# ME461_F28379D.net
KiCad netlist of a schematic drawn in EAGLE
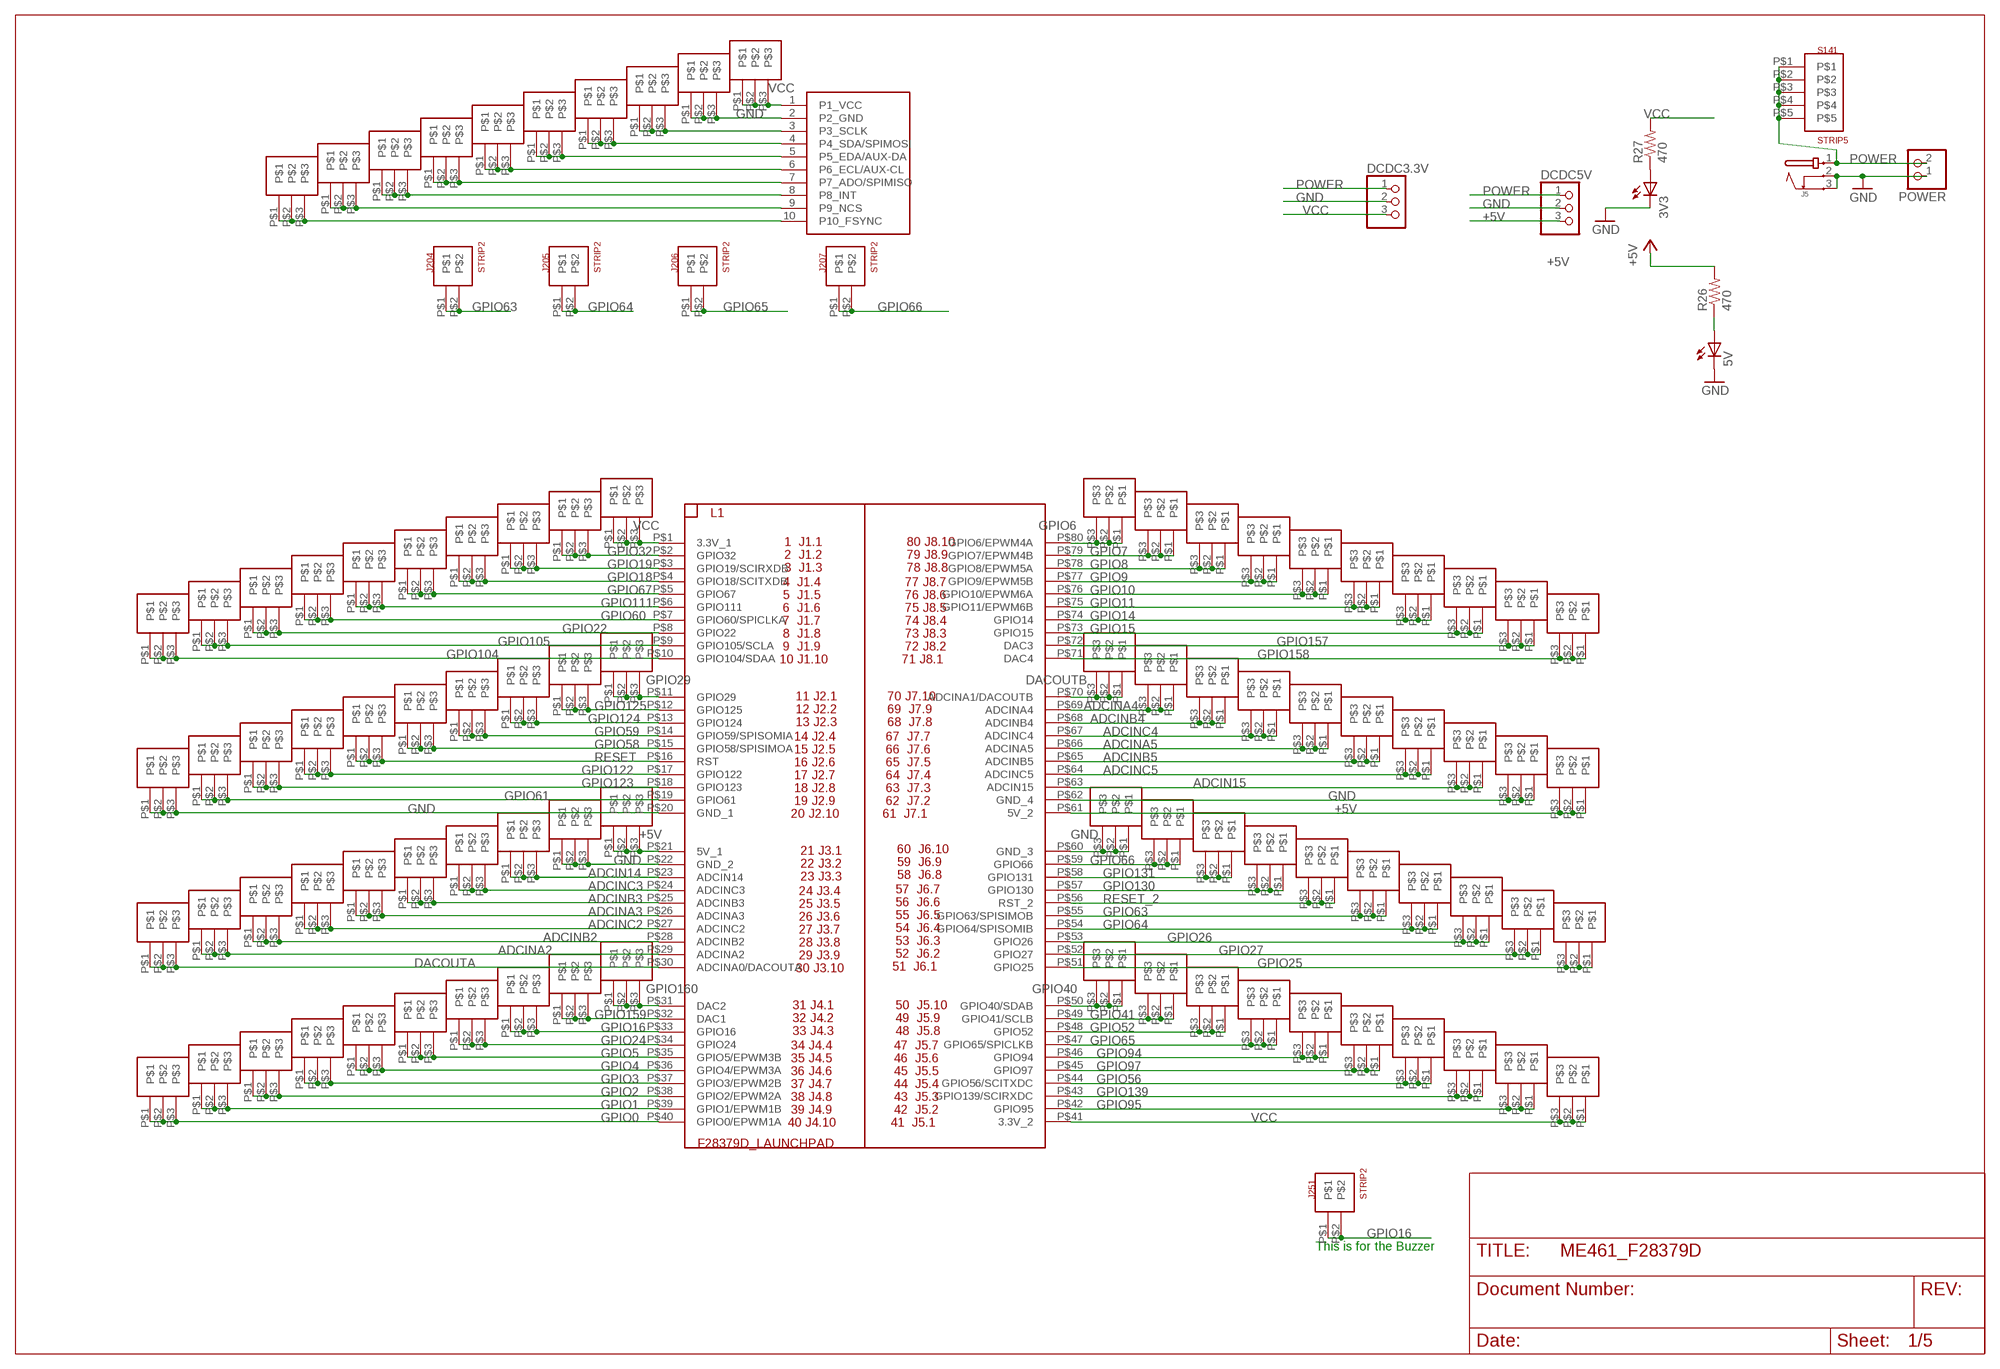
[diagram p0: schematic, sheet 1]
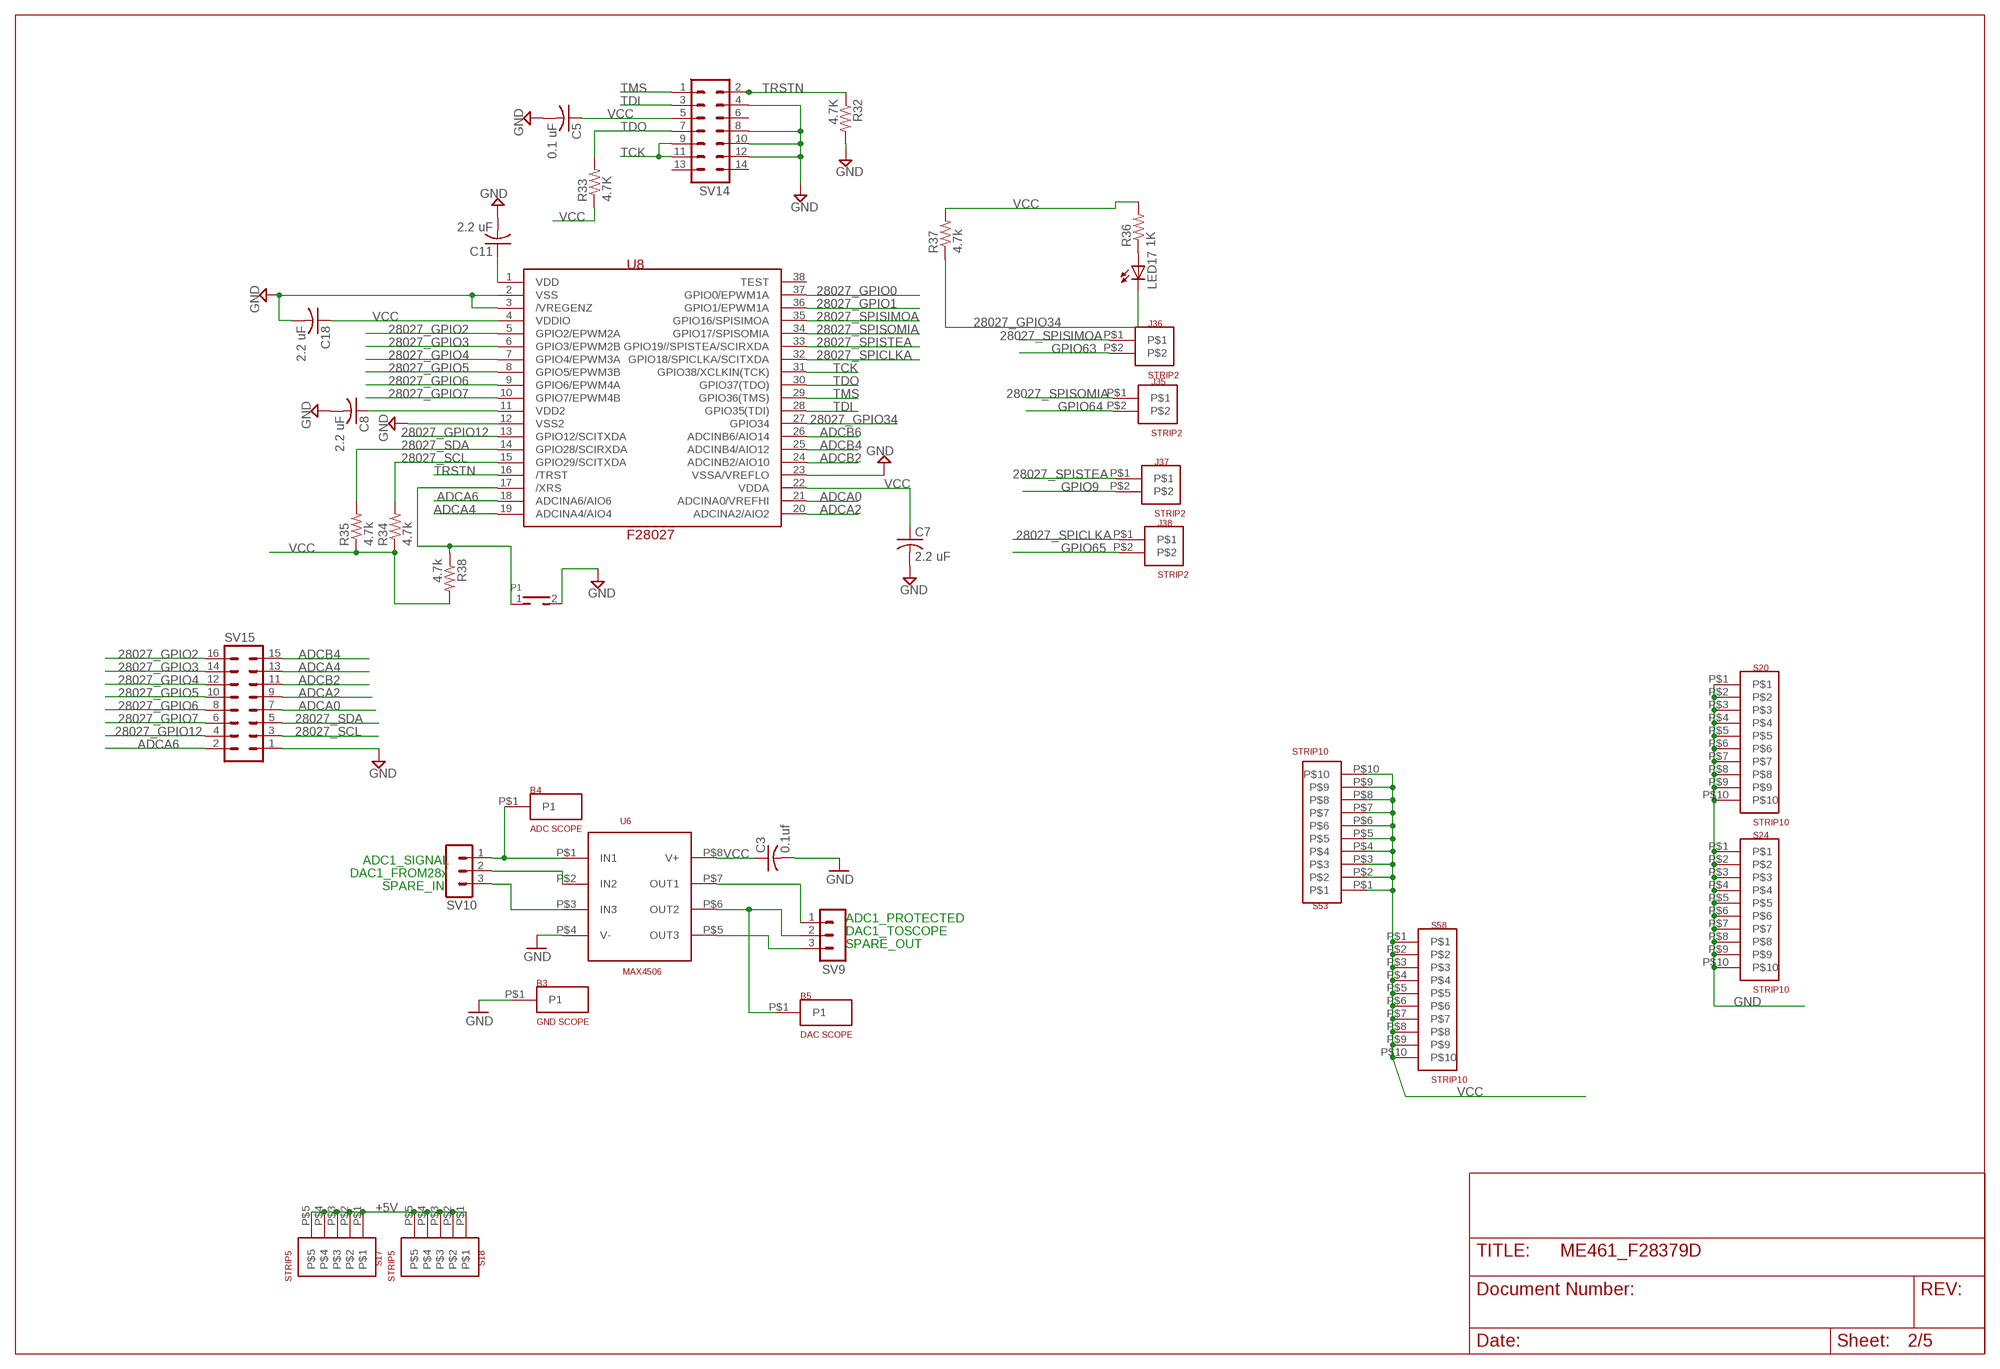
[diagram p1: schematic, sheet 2]
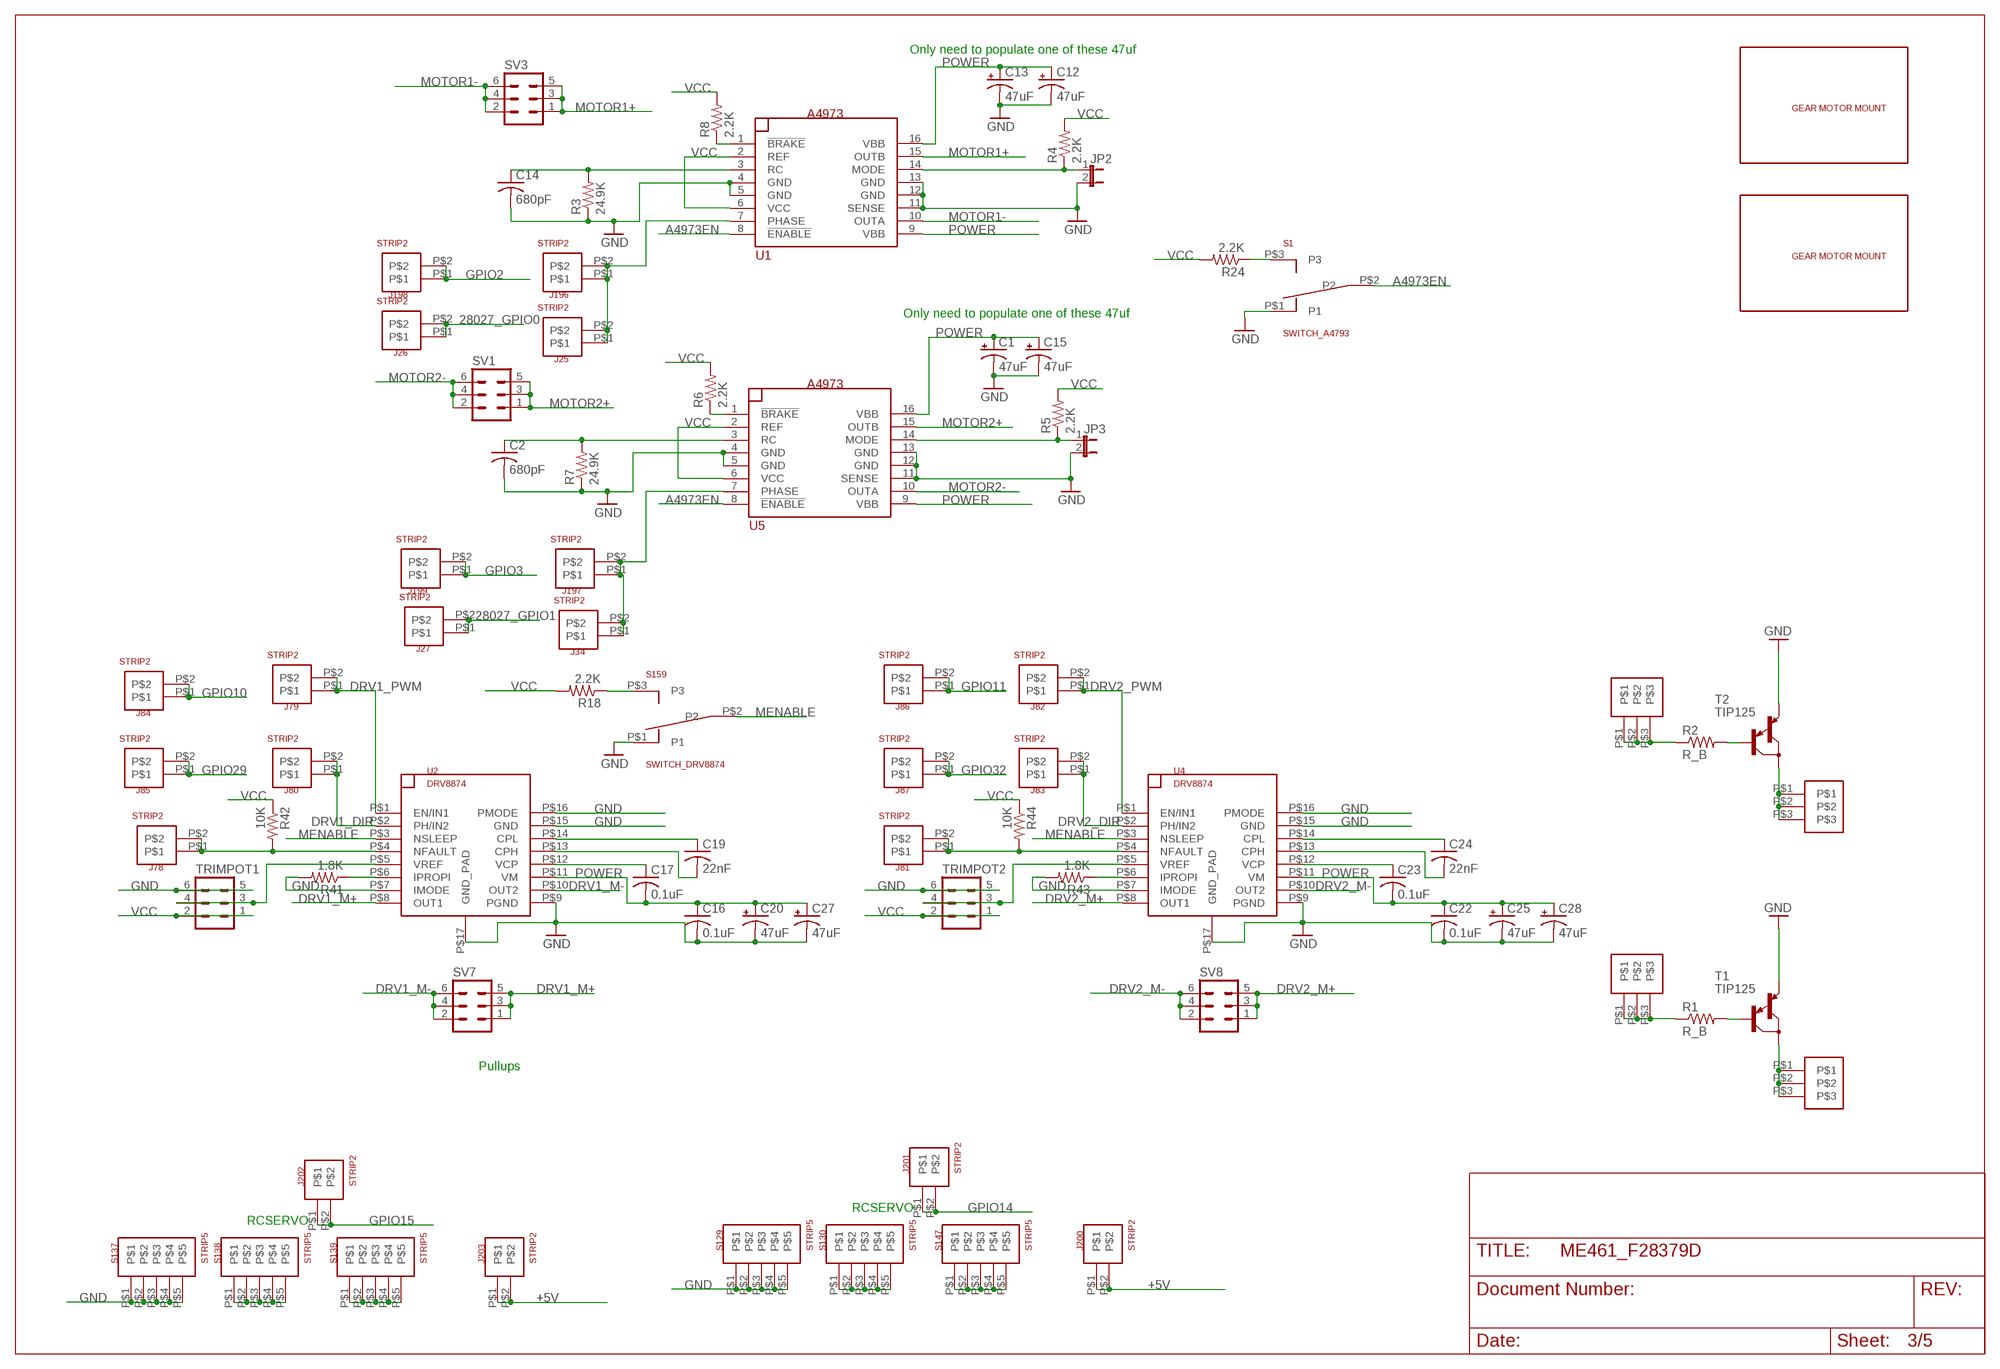
[diagram p2: schematic, sheet 3]
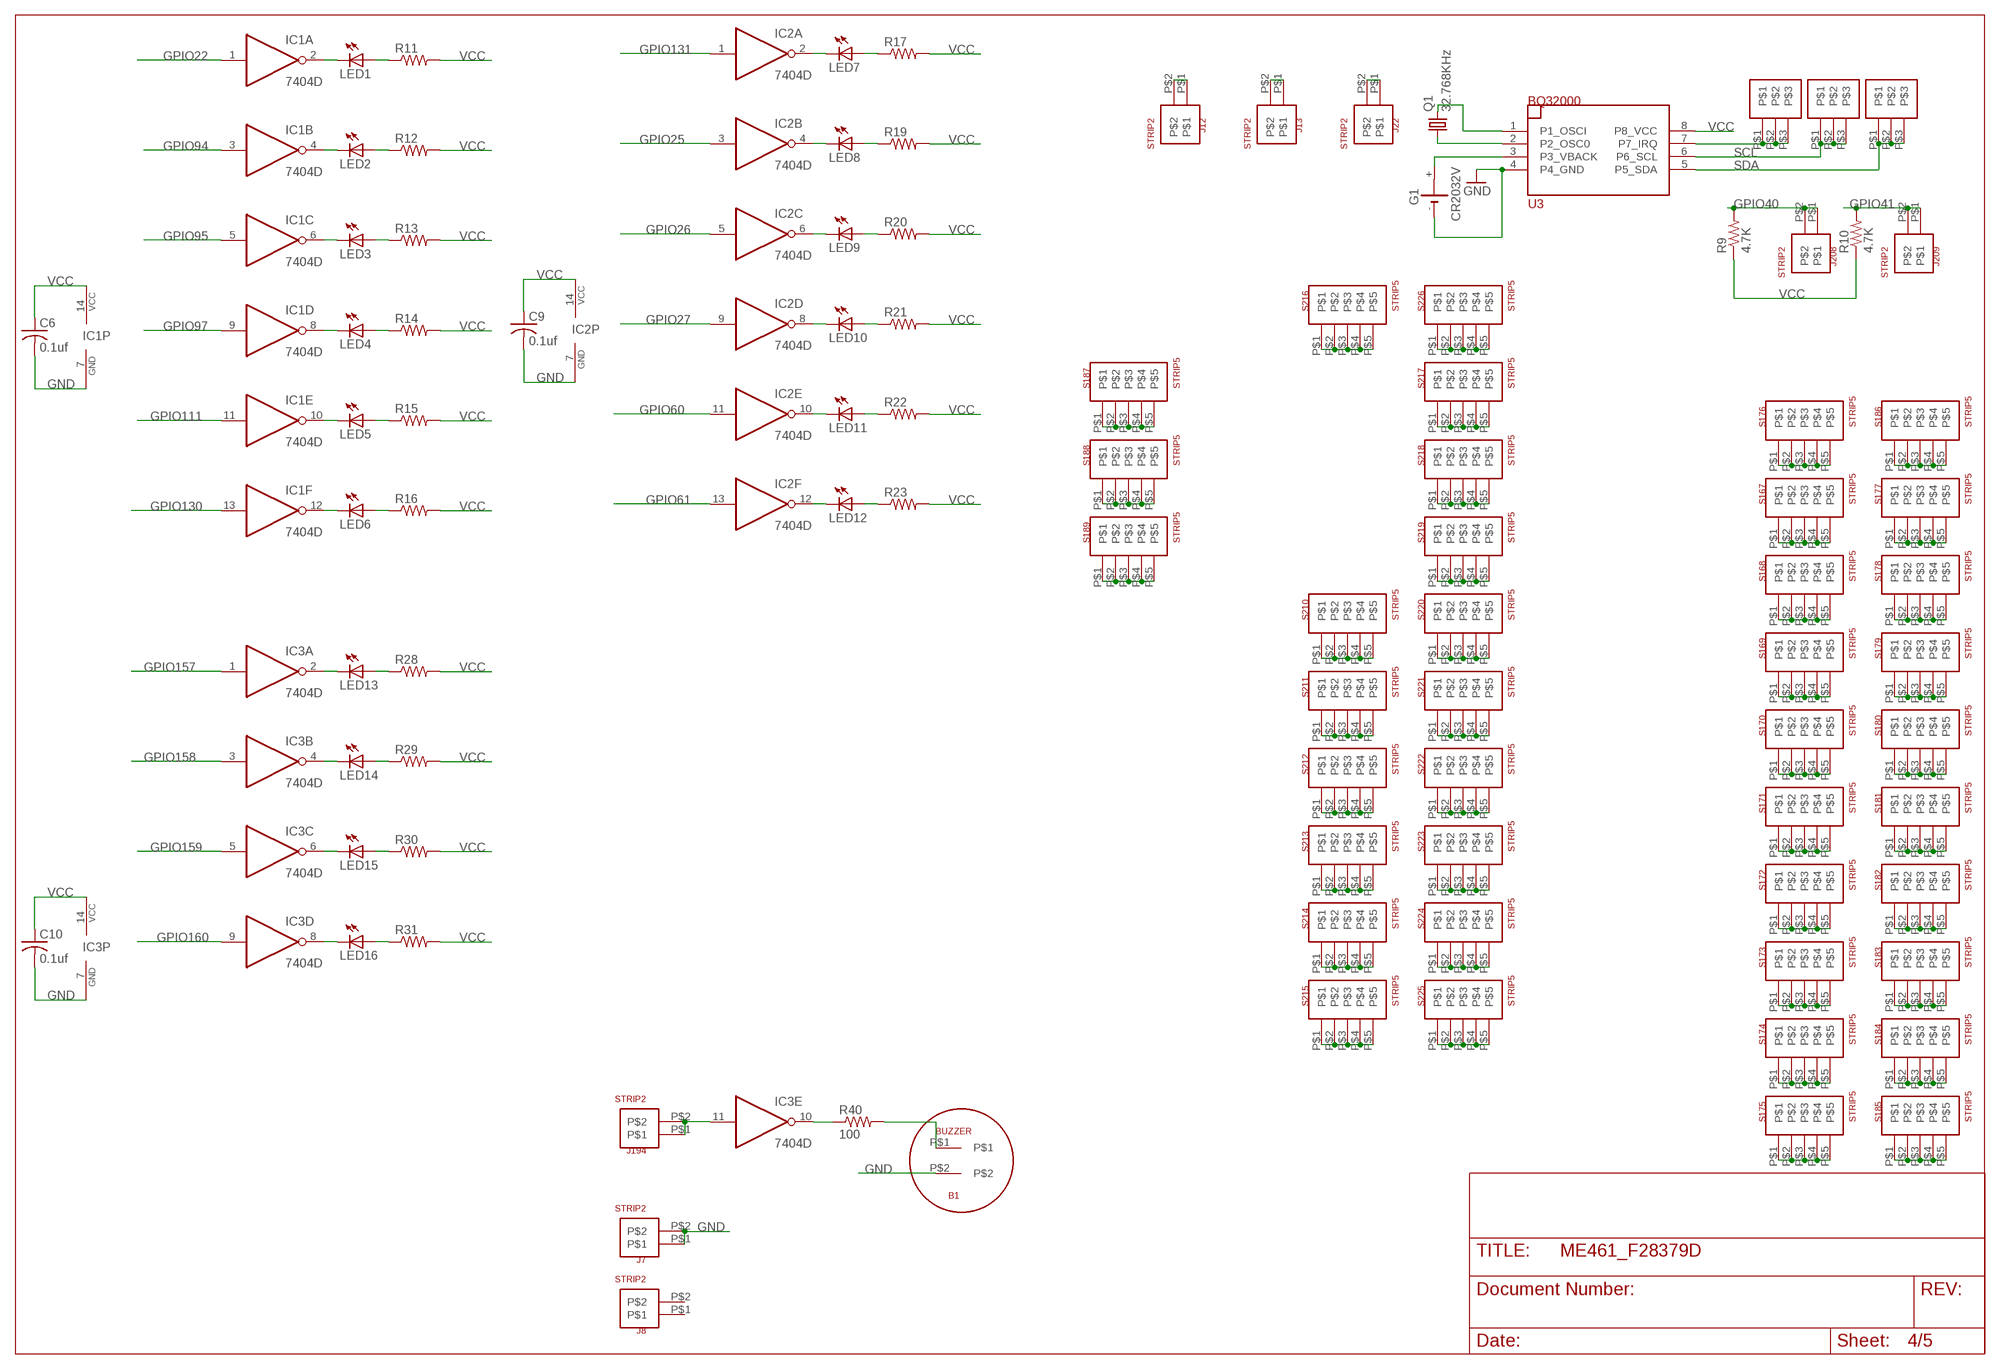
[diagram p3: schematic, sheet 4]
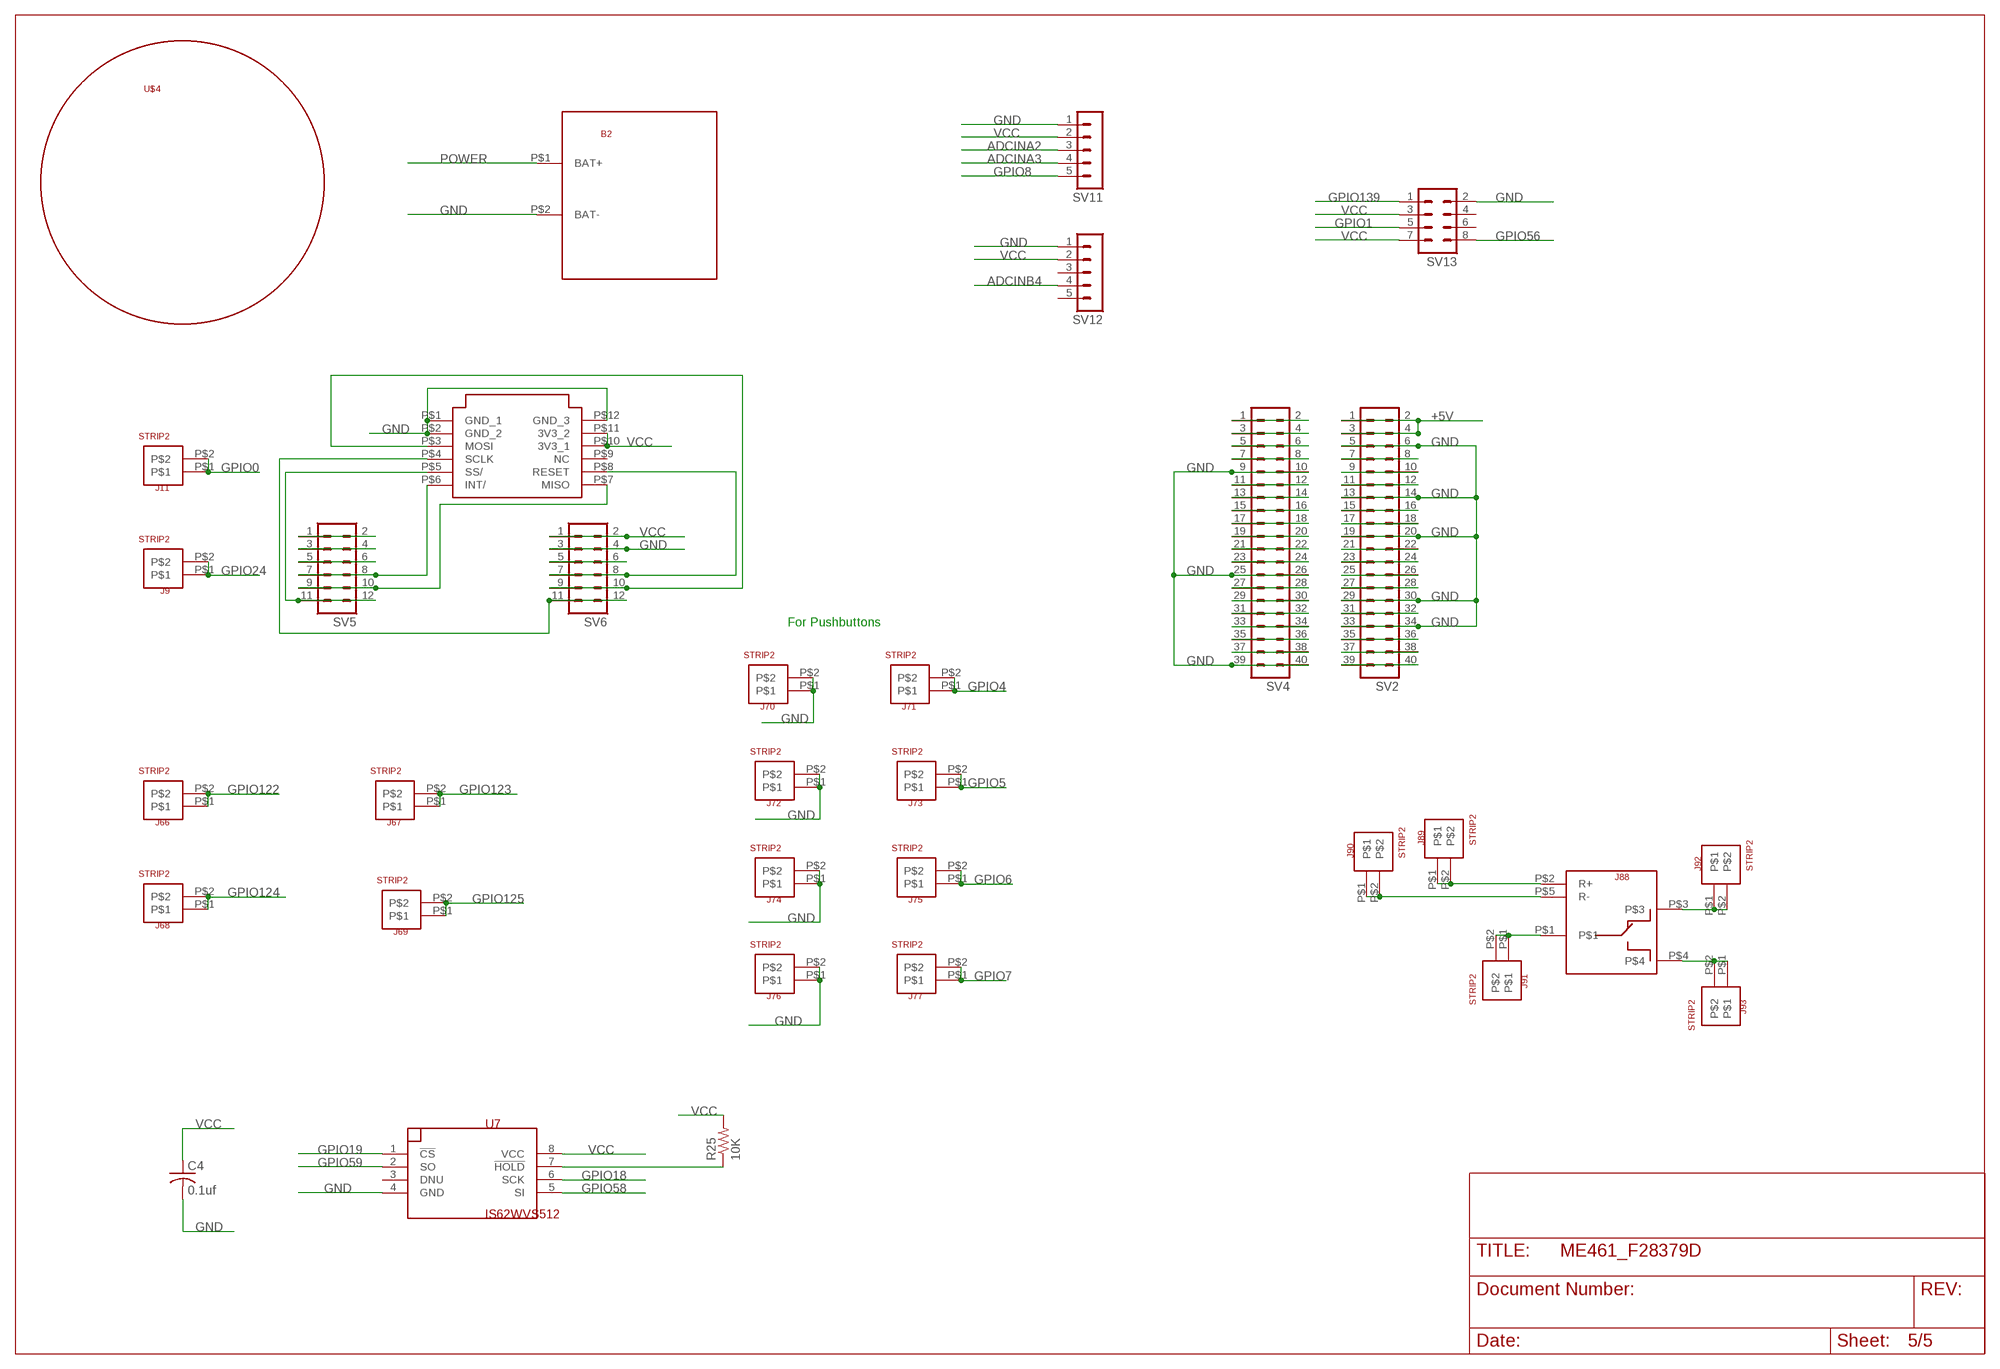
[diagram p4: schematic, sheet 5]

(export (version "E")
  (design (tool "Eeschema 10.0.6"))
  (components
    (comp (ref "B2")
      (value "BATTERY_4AA_HOLDER")
      (footprint "eagle-import:BATTERY_4AA_HOLDER")
      (libsource (lib "eagle-import") (part "BATTERY_4AA_HOLDER"))
    )
    (comp (ref "C4")
      (value "0.1uf")
      (footprint "eagle-import:C1206")
      (libsource (lib "eagle-import") (part "C-USC1206"))
    )
    (comp (ref "ETH1")
      (value "USR_ES1_W5500")
      (footprint "eagle-import:USR_ES1_W5500")
      (libsource (lib "eagle-import") (part "USR_ES1_W5500"))
    )
    (comp (ref "J9")
      (value "STRIP2")
      (footprint "eagle-import:STRIP2")
      (libsource (lib "eagle-import") (part "STRIP2"))
    )
    (comp (ref "J11")
      (value "STRIP2")
      (footprint "eagle-import:STRIP2")
      (libsource (lib "eagle-import") (part "STRIP2"))
    )
    (comp (ref "J66")
      (value "STRIP2")
      (footprint "eagle-import:STRIP2")
      (libsource (lib "eagle-import") (part "STRIP2"))
    )
    (comp (ref "J67")
      (value "STRIP2")
      (footprint "eagle-import:STRIP2")
      (libsource (lib "eagle-import") (part "STRIP2"))
    )
    (comp (ref "J68")
      (value "STRIP2")
      (footprint "eagle-import:STRIP2")
      (libsource (lib "eagle-import") (part "STRIP2"))
    )
    (comp (ref "J69")
      (value "STRIP2")
      (footprint "eagle-import:STRIP2")
      (libsource (lib "eagle-import") (part "STRIP2"))
    )
    (comp (ref "J70")
      (value "STRIP2")
      (footprint "eagle-import:STRIP2")
      (libsource (lib "eagle-import") (part "STRIP2"))
    )
    (comp (ref "J71")
      (value "STRIP2")
      (footprint "eagle-import:STRIP2")
      (libsource (lib "eagle-import") (part "STRIP2"))
    )
    (comp (ref "J72")
      (value "STRIP2")
      (footprint "eagle-import:STRIP2")
      (libsource (lib "eagle-import") (part "STRIP2"))
    )
    (comp (ref "J73")
      (value "STRIP2")
      (footprint "eagle-import:STRIP2")
      (libsource (lib "eagle-import") (part "STRIP2"))
    )
    (comp (ref "J74")
      (value "STRIP2")
      (footprint "eagle-import:STRIP2")
      (libsource (lib "eagle-import") (part "STRIP2"))
    )
    (comp (ref "J75")
      (value "STRIP2")
      (footprint "eagle-import:STRIP2")
      (libsource (lib "eagle-import") (part "STRIP2"))
    )
    (comp (ref "J76")
      (value "STRIP2")
      (footprint "eagle-import:STRIP2")
      (libsource (lib "eagle-import") (part "STRIP2"))
    )
    (comp (ref "J77")
      (value "STRIP2")
      (footprint "eagle-import:STRIP2")
      (libsource (lib "eagle-import") (part "STRIP2"))
    )
    (comp (ref "J88")
      (value "RELAY_JQC-3F_5V")
      (footprint "eagle-import:RELAY_JQC-3F_5V")
      (libsource (lib "eagle-import") (part "RELAY_JQC-3F_5V"))
    )
    (comp (ref "J89")
      (value "STRIP2")
      (footprint "eagle-import:STRIP2")
      (libsource (lib "eagle-import") (part "STRIP2"))
    )
    (comp (ref "J90")
      (value "STRIP2")
      (footprint "eagle-import:STRIP2")
      (libsource (lib "eagle-import") (part "STRIP2"))
    )
    (comp (ref "J91")
      (value "STRIP2")
      (footprint "eagle-import:STRIP2")
      (libsource (lib "eagle-import") (part "STRIP2"))
    )
    (comp (ref "J92")
      (value "STRIP2")
      (footprint "eagle-import:STRIP2")
      (libsource (lib "eagle-import") (part "STRIP2"))
    )
    (comp (ref "J93")
      (value "STRIP2")
      (footprint "eagle-import:STRIP2")
      (libsource (lib "eagle-import") (part "STRIP2"))
    )
    (comp (ref "R25")
      (value "10K")
      (footprint "eagle-import:M1206")
      (libsource (lib "eagle-import") (part "R-US_M1206"))
    )
    (comp (ref "SV2")
      (value "MA20-2")
      (footprint "eagle-import:MA20-2")
      (libsource (lib "eagle-import") (part "MA20-2"))
    )
    (comp (ref "SV4")
      (value "MA20-2")
      (footprint "eagle-import:MA20-2")
      (libsource (lib "eagle-import") (part "MA20-2"))
    )
    (comp (ref "SV5")
      (value "MA06-2")
      (footprint "eagle-import:MA06-2")
      (libsource (lib "eagle-import") (part "MA06-2"))
    )
    (comp (ref "SV6")
      (value "MA06-2")
      (footprint "eagle-import:MA06-2")
      (libsource (lib "eagle-import") (part "MA06-2"))
    )
    (comp (ref "SV11")
      (value "MA05-1")
      (footprint "eagle-import:MA05-1")
      (libsource (lib "eagle-import") (part "MA05-1"))
    )
    (comp (ref "SV12")
      (value "MA05-1")
      (footprint "eagle-import:MA05-1")
      (libsource (lib "eagle-import") (part "MA05-1"))
    )
    (comp (ref "SV13")
      (value "MA04-2")
      (footprint "eagle-import:MA04-2")
      (libsource (lib "eagle-import") (part "MA04-2"))
    )
    (comp (ref "U$4")
      (value "CASTERWHEEL")
      (footprint "eagle-import:CASTERWHEEL")
      (libsource (lib "eagle-import") (part "CASTERWHEEL"))
    )
    (comp (ref "U7")
      (value "IS62WVS512")
      (footprint "eagle-import:SO08")
      (libsource (lib "eagle-import") (part "IS62WVS512"))
    )
    (comp (ref "B1")
      (value "BUZZER")
      (footprint "eagle-import:BUZZER")
      (libsource (lib "eagle-import") (part "BUZZER"))
    )
    (comp (ref "C6")
      (value "0.1uf")
      (footprint "eagle-import:C1206")
      (libsource (lib "eagle-import") (part "C-USC1206"))
    )
    (comp (ref "C9")
      (value "0.1uf")
      (footprint "eagle-import:C1206")
      (libsource (lib "eagle-import") (part "C-USC1206"))
    )
    (comp (ref "C10")
      (value "0.1uf")
      (footprint "eagle-import:C1206")
      (libsource (lib "eagle-import") (part "C-USC1206"))
    )
    (comp (ref "G1")
      (value "CR2032V")
      (footprint "eagle-import:CR2032V")
      (libsource (lib "eagle-import") (part "CR2032V"))
    )
    (comp (ref "IC1")
      (value "7404D")
      (footprint "eagle-import:SO14")
      (libsource (lib "eagle-import") (part "7404D"))
    )
    (comp (ref "IC2")
      (value "7404D")
      (footprint "eagle-import:SO14")
      (libsource (lib "eagle-import") (part "7404D"))
    )
    (comp (ref "IC3")
      (value "7404D")
      (footprint "eagle-import:SO14")
      (libsource (lib "eagle-import") (part "7404D"))
    )
    (comp (ref "J1")
      (value "STRIP3")
      (footprint "eagle-import:STRIP3")
      (libsource (lib "eagle-import") (part "STRIP3"))
    )
    (comp (ref "J2")
      (value "STRIP3")
      (footprint "eagle-import:STRIP3")
      (libsource (lib "eagle-import") (part "STRIP3"))
    )
    (comp (ref "J3")
      (value "STRIP3")
      (footprint "eagle-import:STRIP3")
      (libsource (lib "eagle-import") (part "STRIP3"))
    )
    (comp (ref "J7")
      (value "STRIP2")
      (footprint "eagle-import:STRIP2")
      (libsource (lib "eagle-import") (part "STRIP2"))
    )
    (comp (ref "J8")
      (value "STRIP2")
      (footprint "eagle-import:STRIP2")
      (libsource (lib "eagle-import") (part "STRIP2"))
    )
    (comp (ref "J12")
      (value "STRIP2")
      (footprint "eagle-import:STRIP2")
      (libsource (lib "eagle-import") (part "STRIP2"))
    )
    (comp (ref "J13")
      (value "STRIP2")
      (footprint "eagle-import:STRIP2")
      (libsource (lib "eagle-import") (part "STRIP2"))
    )
    (comp (ref "J22")
      (value "STRIP2")
      (footprint "eagle-import:STRIP2")
      (libsource (lib "eagle-import") (part "STRIP2"))
    )
    (comp (ref "J194")
      (value "STRIP2")
      (footprint "eagle-import:STRIP2")
      (libsource (lib "eagle-import") (part "STRIP2"))
    )
    (comp (ref "J208")
      (value "STRIP2")
      (footprint "eagle-import:STRIP2")
      (libsource (lib "eagle-import") (part "STRIP2"))
    )
    (comp (ref "J209")
      (value "STRIP2")
      (footprint "eagle-import:STRIP2")
      (libsource (lib "eagle-import") (part "STRIP2"))
    )
    (comp (ref "LED1")
      (value "LEDCHIPLED_1206")
      (footprint "eagle-import:CHIPLED_1206")
      (libsource (lib "eagle-import") (part "LEDCHIPLED_1206"))
    )
    (comp (ref "LED2")
      (value "LEDCHIPLED_1206")
      (footprint "eagle-import:CHIPLED_1206")
      (libsource (lib "eagle-import") (part "LEDCHIPLED_1206"))
    )
    (comp (ref "LED3")
      (value "LEDCHIPLED_1206")
      (footprint "eagle-import:CHIPLED_1206")
      (libsource (lib "eagle-import") (part "LEDCHIPLED_1206"))
    )
    (comp (ref "LED4")
      (value "LEDCHIPLED_1206")
      (footprint "eagle-import:CHIPLED_1206")
      (libsource (lib "eagle-import") (part "LEDCHIPLED_1206"))
    )
    (comp (ref "LED5")
      (value "LEDCHIPLED_1206")
      (footprint "eagle-import:CHIPLED_1206")
      (libsource (lib "eagle-import") (part "LEDCHIPLED_1206"))
    )
    (comp (ref "LED6")
      (value "LEDCHIPLED_1206")
      (footprint "eagle-import:CHIPLED_1206")
      (libsource (lib "eagle-import") (part "LEDCHIPLED_1206"))
    )
    (comp (ref "LED7")
      (value "LEDCHIPLED_1206")
      (footprint "eagle-import:CHIPLED_1206")
      (libsource (lib "eagle-import") (part "LEDCHIPLED_1206"))
    )
    (comp (ref "LED8")
      (value "LEDCHIPLED_1206")
      (footprint "eagle-import:CHIPLED_1206")
      (libsource (lib "eagle-import") (part "LEDCHIPLED_1206"))
    )
    (comp (ref "LED9")
      (value "LEDCHIPLED_1206")
      (footprint "eagle-import:CHIPLED_1206")
      (libsource (lib "eagle-import") (part "LEDCHIPLED_1206"))
    )
    (comp (ref "LED10")
      (value "LEDCHIPLED_1206")
      (footprint "eagle-import:CHIPLED_1206")
      (libsource (lib "eagle-import") (part "LEDCHIPLED_1206"))
    )
    (comp (ref "LED11")
      (value "LEDCHIPLED_1206")
      (footprint "eagle-import:CHIPLED_1206")
      (libsource (lib "eagle-import") (part "LEDCHIPLED_1206"))
    )
    (comp (ref "LED12")
      (value "LEDCHIPLED_1206")
      (footprint "eagle-import:CHIPLED_1206")
      (libsource (lib "eagle-import") (part "LEDCHIPLED_1206"))
    )
    (comp (ref "LED13")
      (value "LEDCHIPLED_1206")
      (footprint "eagle-import:CHIPLED_1206")
      (libsource (lib "eagle-import") (part "LEDCHIPLED_1206"))
    )
    (comp (ref "LED14")
      (value "LEDCHIPLED_1206")
      (footprint "eagle-import:CHIPLED_1206")
      (libsource (lib "eagle-import") (part "LEDCHIPLED_1206"))
    )
    (comp (ref "LED15")
      (value "LEDCHIPLED_1206")
      (footprint "eagle-import:CHIPLED_1206")
      (libsource (lib "eagle-import") (part "LEDCHIPLED_1206"))
    )
    (comp (ref "LED16")
      (value "LEDCHIPLED_1206")
      (footprint "eagle-import:CHIPLED_1206")
      (libsource (lib "eagle-import") (part "LEDCHIPLED_1206"))
    )
    (comp (ref "Q1")
      (value "32.768KHz")
      (footprint "eagle-import:TC26H")
      (libsource (lib "eagle-import") (part "CRYTALTC26H"))
    )
    (comp (ref "R9")
      (value "4.7K")
      (footprint "eagle-import:R1206")
      (libsource (lib "eagle-import") (part "R-US_R1206"))
    )
    (comp (ref "R10")
      (value "4.7K")
      (footprint "eagle-import:R1206")
      (libsource (lib "eagle-import") (part "R-US_R1206"))
    )
    (comp (ref "R11")
      (value "R-US_R1206")
      (footprint "eagle-import:R1206")
      (libsource (lib "eagle-import") (part "R-US_R1206"))
    )
    (comp (ref "R12")
      (value "R-US_R1206")
      (footprint "eagle-import:R1206")
      (libsource (lib "eagle-import") (part "R-US_R1206"))
    )
    (comp (ref "R13")
      (value "R-US_R1206")
      (footprint "eagle-import:R1206")
      (libsource (lib "eagle-import") (part "R-US_R1206"))
    )
    (comp (ref "R14")
      (value "R-US_R1206")
      (footprint "eagle-import:R1206")
      (libsource (lib "eagle-import") (part "R-US_R1206"))
    )
    (comp (ref "R15")
      (value "R-US_R1206")
      (footprint "eagle-import:R1206")
      (libsource (lib "eagle-import") (part "R-US_R1206"))
    )
    (comp (ref "R16")
      (value "R-US_R1206")
      (footprint "eagle-import:R1206")
      (libsource (lib "eagle-import") (part "R-US_R1206"))
    )
    (comp (ref "R17")
      (value "R-US_R1206")
      (footprint "eagle-import:R1206")
      (libsource (lib "eagle-import") (part "R-US_R1206"))
    )
    (comp (ref "R19")
      (value "R-US_R1206")
      (footprint "eagle-import:R1206")
      (libsource (lib "eagle-import") (part "R-US_R1206"))
    )
    (comp (ref "R20")
      (value "R-US_R1206")
      (footprint "eagle-import:R1206")
      (libsource (lib "eagle-import") (part "R-US_R1206"))
    )
    (comp (ref "R21")
      (value "R-US_R1206")
      (footprint "eagle-import:R1206")
      (libsource (lib "eagle-import") (part "R-US_R1206"))
    )
    (comp (ref "R22")
      (value "R-US_R1206")
      (footprint "eagle-import:R1206")
      (libsource (lib "eagle-import") (part "R-US_R1206"))
    )
    (comp (ref "R23")
      (value "R-US_R1206")
      (footprint "eagle-import:R1206")
      (libsource (lib "eagle-import") (part "R-US_R1206"))
    )
    (comp (ref "R28")
      (value "R-US_R1206")
      (footprint "eagle-import:R1206")
      (libsource (lib "eagle-import") (part "R-US_R1206"))
    )
    (comp (ref "R29")
      (value "R-US_R1206")
      (footprint "eagle-import:R1206")
      (libsource (lib "eagle-import") (part "R-US_R1206"))
    )
    (comp (ref "R30")
      (value "R-US_R1206")
      (footprint "eagle-import:R1206")
      (libsource (lib "eagle-import") (part "R-US_R1206"))
    )
    (comp (ref "R31")
      (value "R-US_R1206")
      (footprint "eagle-import:R1206")
      (libsource (lib "eagle-import") (part "R-US_R1206"))
    )
    (comp (ref "R40")
      (value "100")
      (footprint "eagle-import:R1206")
      (libsource (lib "eagle-import") (part "R-US_R1206"))
    )
    (comp (ref "S167")
      (value "STRIP5")
      (footprint "eagle-import:STRIP5")
      (libsource (lib "eagle-import") (part "STRIP5"))
    )
    (comp (ref "S168")
      (value "STRIP5")
      (footprint "eagle-import:STRIP5")
      (libsource (lib "eagle-import") (part "STRIP5"))
    )
    (comp (ref "S169")
      (value "STRIP5")
      (footprint "eagle-import:STRIP5")
      (libsource (lib "eagle-import") (part "STRIP5"))
    )
    (comp (ref "S170")
      (value "STRIP5")
      (footprint "eagle-import:STRIP5")
      (libsource (lib "eagle-import") (part "STRIP5"))
    )
    (comp (ref "S171")
      (value "STRIP5")
      (footprint "eagle-import:STRIP5")
      (libsource (lib "eagle-import") (part "STRIP5"))
    )
    (comp (ref "S172")
      (value "STRIP5")
      (footprint "eagle-import:STRIP5")
      (libsource (lib "eagle-import") (part "STRIP5"))
    )
    (comp (ref "S173")
      (value "STRIP5")
      (footprint "eagle-import:STRIP5")
      (libsource (lib "eagle-import") (part "STRIP5"))
    )
    (comp (ref "S174")
      (value "STRIP5")
      (footprint "eagle-import:STRIP5")
      (libsource (lib "eagle-import") (part "STRIP5"))
    )
    (comp (ref "S175")
      (value "STRIP5")
      (footprint "eagle-import:STRIP5")
      (libsource (lib "eagle-import") (part "STRIP5"))
    )
    (comp (ref "S176")
      (value "STRIP5")
      (footprint "eagle-import:STRIP5")
      (libsource (lib "eagle-import") (part "STRIP5"))
    )
    (comp (ref "S177")
      (value "STRIP5")
      (footprint "eagle-import:STRIP5")
      (libsource (lib "eagle-import") (part "STRIP5"))
    )
    (comp (ref "S178")
      (value "STRIP5")
      (footprint "eagle-import:STRIP5")
      (libsource (lib "eagle-import") (part "STRIP5"))
    )
    (comp (ref "S179")
      (value "STRIP5")
      (footprint "eagle-import:STRIP5")
      (libsource (lib "eagle-import") (part "STRIP5"))
    )
    (comp (ref "S180")
      (value "STRIP5")
      (footprint "eagle-import:STRIP5")
      (libsource (lib "eagle-import") (part "STRIP5"))
    )
    (comp (ref "S181")
      (value "STRIP5")
      (footprint "eagle-import:STRIP5")
      (libsource (lib "eagle-import") (part "STRIP5"))
    )
    (comp (ref "S182")
      (value "STRIP5")
      (footprint "eagle-import:STRIP5")
      (libsource (lib "eagle-import") (part "STRIP5"))
    )
    (comp (ref "S183")
      (value "STRIP5")
      (footprint "eagle-import:STRIP5")
      (libsource (lib "eagle-import") (part "STRIP5"))
    )
    (comp (ref "S184")
      (value "STRIP5")
      (footprint "eagle-import:STRIP5")
      (libsource (lib "eagle-import") (part "STRIP5"))
    )
    (comp (ref "S185")
      (value "STRIP5")
      (footprint "eagle-import:STRIP5")
      (libsource (lib "eagle-import") (part "STRIP5"))
    )
    (comp (ref "S186")
      (value "STRIP5")
      (footprint "eagle-import:STRIP5")
      (libsource (lib "eagle-import") (part "STRIP5"))
    )
    (comp (ref "S187")
      (value "STRIP5")
      (footprint "eagle-import:STRIP5")
      (libsource (lib "eagle-import") (part "STRIP5"))
    )
    (comp (ref "S188")
      (value "STRIP5")
      (footprint "eagle-import:STRIP5")
      (libsource (lib "eagle-import") (part "STRIP5"))
    )
    (comp (ref "S189")
      (value "STRIP5")
      (footprint "eagle-import:STRIP5")
      (libsource (lib "eagle-import") (part "STRIP5"))
    )
    (comp (ref "S210")
      (value "STRIP5")
      (footprint "eagle-import:STRIP5")
      (libsource (lib "eagle-import") (part "STRIP5"))
    )
    (comp (ref "S211")
      (value "STRIP5")
      (footprint "eagle-import:STRIP5")
      (libsource (lib "eagle-import") (part "STRIP5"))
    )
    (comp (ref "S212")
      (value "STRIP5")
      (footprint "eagle-import:STRIP5")
      (libsource (lib "eagle-import") (part "STRIP5"))
    )
    (comp (ref "S213")
      (value "STRIP5")
      (footprint "eagle-import:STRIP5")
      (libsource (lib "eagle-import") (part "STRIP5"))
    )
    (comp (ref "S214")
      (value "STRIP5")
      (footprint "eagle-import:STRIP5")
      (libsource (lib "eagle-import") (part "STRIP5"))
    )
    (comp (ref "S215")
      (value "STRIP5")
      (footprint "eagle-import:STRIP5")
      (libsource (lib "eagle-import") (part "STRIP5"))
    )
    (comp (ref "S216")
      (value "STRIP5")
      (footprint "eagle-import:STRIP5")
      (libsource (lib "eagle-import") (part "STRIP5"))
    )
    (comp (ref "S217")
      (value "STRIP5")
      (footprint "eagle-import:STRIP5")
      (libsource (lib "eagle-import") (part "STRIP5"))
    )
    (comp (ref "S218")
      (value "STRIP5")
      (footprint "eagle-import:STRIP5")
      (libsource (lib "eagle-import") (part "STRIP5"))
    )
    (comp (ref "S219")
      (value "STRIP5")
      (footprint "eagle-import:STRIP5")
      (libsource (lib "eagle-import") (part "STRIP5"))
    )
    (comp (ref "S220")
      (value "STRIP5")
      (footprint "eagle-import:STRIP5")
      (libsource (lib "eagle-import") (part "STRIP5"))
    )
    (comp (ref "S221")
      (value "STRIP5")
      (footprint "eagle-import:STRIP5")
      (libsource (lib "eagle-import") (part "STRIP5"))
    )
    (comp (ref "S222")
      (value "STRIP5")
      (footprint "eagle-import:STRIP5")
      (libsource (lib "eagle-import") (part "STRIP5"))
    )
    (comp (ref "S223")
      (value "STRIP5")
      (footprint "eagle-import:STRIP5")
      (libsource (lib "eagle-import") (part "STRIP5"))
    )
    (comp (ref "S224")
      (value "STRIP5")
      (footprint "eagle-import:STRIP5")
      (libsource (lib "eagle-import") (part "STRIP5"))
    )
    (comp (ref "S225")
      (value "STRIP5")
      (footprint "eagle-import:STRIP5")
      (libsource (lib "eagle-import") (part "STRIP5"))
    )
    (comp (ref "S226")
      (value "STRIP5")
      (footprint "eagle-import:STRIP5")
      (libsource (lib "eagle-import") (part "STRIP5"))
    )
    (comp (ref "U3")
      (value "BQ32000")
      (footprint "eagle-import:SO08")
      (libsource (lib "eagle-import") (part "BQ32000"))
    )
    (comp (ref "3V3")
      (value "LEDCHIPLED_1206")
      (footprint "eagle-import:CHIPLED_1206")
      (libsource (lib "eagle-import") (part "LEDCHIPLED_1206"))
    )
    (comp (ref "5V")
      (value "LEDCHIPLED_1206")
      (footprint "eagle-import:CHIPLED_1206")
      (libsource (lib "eagle-import") (part "LEDCHIPLED_1206"))
    )
    (comp (ref "DCDC3.3V")
      (value "PINHD-1X3")
      (footprint "eagle-import:1X03")
      (libsource (lib "eagle-import") (part "PINHD-1X3"))
    )
    (comp (ref "DCDC5V")
      (value "PINHD-1X3")
      (footprint "eagle-import:1X03")
      (libsource (lib "eagle-import") (part "PINHD-1X3"))
    )
    (comp (ref "J5")
      (value "JACK-PMS")
      (footprint "eagle-import:JACK-PMS")
      (libsource (lib "eagle-import") (part "JACK-PMS"))
    )
    (comp (ref "J10")
      (value "STRIP3")
      (footprint "eagle-import:STRIP3")
      (libsource (lib "eagle-import") (part "STRIP3"))
    )
    (comp (ref "J14")
      (value "STRIP3")
      (footprint "eagle-import:STRIP3")
      (libsource (lib "eagle-import") (part "STRIP3"))
    )
    (comp (ref "J15")
      (value "STRIP3")
      (footprint "eagle-import:STRIP3")
      (libsource (lib "eagle-import") (part "STRIP3"))
    )
    (comp (ref "J16")
      (value "STRIP3")
      (footprint "eagle-import:STRIP3")
      (libsource (lib "eagle-import") (part "STRIP3"))
    )
    (comp (ref "J17")
      (value "STRIP3")
      (footprint "eagle-import:STRIP3")
      (libsource (lib "eagle-import") (part "STRIP3"))
    )
    (comp (ref "J18")
      (value "STRIP3")
      (footprint "eagle-import:STRIP3")
      (libsource (lib "eagle-import") (part "STRIP3"))
    )
    (comp (ref "J19")
      (value "STRIP3")
      (footprint "eagle-import:STRIP3")
      (libsource (lib "eagle-import") (part "STRIP3"))
    )
    (comp (ref "J20")
      (value "STRIP3")
      (footprint "eagle-import:STRIP3")
      (libsource (lib "eagle-import") (part "STRIP3"))
    )
    (comp (ref "J21")
      (value "STRIP3")
      (footprint "eagle-import:STRIP3")
      (libsource (lib "eagle-import") (part "STRIP3"))
    )
    (comp (ref "J28")
      (value "STRIP3")
      (footprint "eagle-import:STRIP3")
      (libsource (lib "eagle-import") (part "STRIP3"))
    )
    (comp (ref "J29")
      (value "STRIP3")
      (footprint "eagle-import:STRIP3")
      (libsource (lib "eagle-import") (part "STRIP3"))
    )
    (comp (ref "J30")
      (value "STRIP3")
      (footprint "eagle-import:STRIP3")
      (libsource (lib "eagle-import") (part "STRIP3"))
    )
    (comp (ref "J31")
      (value "STRIP3")
      (footprint "eagle-import:STRIP3")
      (libsource (lib "eagle-import") (part "STRIP3"))
    )
    (comp (ref "J32")
      (value "STRIP3")
      (footprint "eagle-import:STRIP3")
      (libsource (lib "eagle-import") (part "STRIP3"))
    )
    (comp (ref "J33")
      (value "STRIP3")
      (footprint "eagle-import:STRIP3")
      (libsource (lib "eagle-import") (part "STRIP3"))
    )
    (comp (ref "J98")
      (value "STRIP3")
      (footprint "eagle-import:STRIP3")
      (libsource (lib "eagle-import") (part "STRIP3"))
    )
    (comp (ref "J99")
      (value "STRIP3")
      (footprint "eagle-import:STRIP3")
      (libsource (lib "eagle-import") (part "STRIP3"))
    )
    (comp (ref "J100")
      (value "STRIP3")
      (footprint "eagle-import:STRIP3")
      (libsource (lib "eagle-import") (part "STRIP3"))
    )
    (comp (ref "J101")
      (value "STRIP3")
      (footprint "eagle-import:STRIP3")
      (libsource (lib "eagle-import") (part "STRIP3"))
    )
    (comp (ref "J102")
      (value "STRIP3")
      (footprint "eagle-import:STRIP3")
      (libsource (lib "eagle-import") (part "STRIP3"))
    )
    (comp (ref "J103")
      (value "STRIP3")
      (footprint "eagle-import:STRIP3")
      (libsource (lib "eagle-import") (part "STRIP3"))
    )
    (comp (ref "J104")
      (value "STRIP3")
      (footprint "eagle-import:STRIP3")
      (libsource (lib "eagle-import") (part "STRIP3"))
    )
    (comp (ref "J105")
      (value "STRIP3")
      (footprint "eagle-import:STRIP3")
      (libsource (lib "eagle-import") (part "STRIP3"))
    )
    (comp (ref "J106")
      (value "STRIP3")
      (footprint "eagle-import:STRIP3")
      (libsource (lib "eagle-import") (part "STRIP3"))
    )
    (comp (ref "J107")
      (value "STRIP3")
      (footprint "eagle-import:STRIP3")
      (libsource (lib "eagle-import") (part "STRIP3"))
    )
    (comp (ref "J108")
      (value "STRIP3")
      (footprint "eagle-import:STRIP3")
      (libsource (lib "eagle-import") (part "STRIP3"))
    )
    (comp (ref "J109")
      (value "STRIP3")
      (footprint "eagle-import:STRIP3")
      (libsource (lib "eagle-import") (part "STRIP3"))
    )
    (comp (ref "J110")
      (value "STRIP3")
      (footprint "eagle-import:STRIP3")
      (libsource (lib "eagle-import") (part "STRIP3"))
    )
    (comp (ref "J111")
      (value "STRIP3")
      (footprint "eagle-import:STRIP3")
      (libsource (lib "eagle-import") (part "STRIP3"))
    )
    (comp (ref "J112")
      (value "STRIP3")
      (footprint "eagle-import:STRIP3")
      (libsource (lib "eagle-import") (part "STRIP3"))
    )
    (comp (ref "J113")
      (value "STRIP3")
      (footprint "eagle-import:STRIP3")
      (libsource (lib "eagle-import") (part "STRIP3"))
    )
    (comp (ref "J114")
      (value "STRIP3")
      (footprint "eagle-import:STRIP3")
      (libsource (lib "eagle-import") (part "STRIP3"))
    )
    (comp (ref "J115")
      (value "STRIP3")
      (footprint "eagle-import:STRIP3")
      (libsource (lib "eagle-import") (part "STRIP3"))
    )
    (comp (ref "J116")
      (value "STRIP3")
      (footprint "eagle-import:STRIP3")
      (libsource (lib "eagle-import") (part "STRIP3"))
    )
    (comp (ref "J117")
      (value "STRIP3")
      (footprint "eagle-import:STRIP3")
      (libsource (lib "eagle-import") (part "STRIP3"))
    )
    (comp (ref "J118")
      (value "STRIP3")
      (footprint "eagle-import:STRIP3")
      (libsource (lib "eagle-import") (part "STRIP3"))
    )
    (comp (ref "J119")
      (value "STRIP3")
      (footprint "eagle-import:STRIP3")
      (libsource (lib "eagle-import") (part "STRIP3"))
    )
    (comp (ref "J120")
      (value "STRIP3")
      (footprint "eagle-import:STRIP3")
      (libsource (lib "eagle-import") (part "STRIP3"))
    )
    (comp (ref "J121")
      (value "STRIP3")
      (footprint "eagle-import:STRIP3")
      (libsource (lib "eagle-import") (part "STRIP3"))
    )
    (comp (ref "J122")
      (value "STRIP3")
      (footprint "eagle-import:STRIP3")
      (libsource (lib "eagle-import") (part "STRIP3"))
    )
    (comp (ref "J123")
      (value "STRIP3")
      (footprint "eagle-import:STRIP3")
      (libsource (lib "eagle-import") (part "STRIP3"))
    )
    (comp (ref "J124")
      (value "STRIP3")
      (footprint "eagle-import:STRIP3")
      (libsource (lib "eagle-import") (part "STRIP3"))
    )
    (comp (ref "J125")
      (value "STRIP3")
      (footprint "eagle-import:STRIP3")
      (libsource (lib "eagle-import") (part "STRIP3"))
    )
    (comp (ref "J126")
      (value "STRIP3")
      (footprint "eagle-import:STRIP3")
      (libsource (lib "eagle-import") (part "STRIP3"))
    )
    (comp (ref "J127")
      (value "STRIP3")
      (footprint "eagle-import:STRIP3")
      (libsource (lib "eagle-import") (part "STRIP3"))
    )
    (comp (ref "J128")
      (value "STRIP3")
      (footprint "eagle-import:STRIP3")
      (libsource (lib "eagle-import") (part "STRIP3"))
    )
    (comp (ref "J129")
      (value "STRIP3")
      (footprint "eagle-import:STRIP3")
      (libsource (lib "eagle-import") (part "STRIP3"))
    )
    (comp (ref "J130")
      (value "STRIP3")
      (footprint "eagle-import:STRIP3")
      (libsource (lib "eagle-import") (part "STRIP3"))
    )
    (comp (ref "J131")
      (value "STRIP3")
      (footprint "eagle-import:STRIP3")
      (libsource (lib "eagle-import") (part "STRIP3"))
    )
    (comp (ref "J132")
      (value "STRIP3")
      (footprint "eagle-import:STRIP3")
      (libsource (lib "eagle-import") (part "STRIP3"))
    )
    (comp (ref "J133")
      (value "STRIP3")
      (footprint "eagle-import:STRIP3")
      (libsource (lib "eagle-import") (part "STRIP3"))
    )
    (comp (ref "J134")
      (value "STRIP3")
      (footprint "eagle-import:STRIP3")
      (libsource (lib "eagle-import") (part "STRIP3"))
    )
    (comp (ref "J135")
      (value "STRIP3")
      (footprint "eagle-import:STRIP3")
      (libsource (lib "eagle-import") (part "STRIP3"))
    )
    (comp (ref "J136")
      (value "STRIP3")
      (footprint "eagle-import:STRIP3")
      (libsource (lib "eagle-import") (part "STRIP3"))
    )
    (comp (ref "J137")
      (value "STRIP3")
      (footprint "eagle-import:STRIP3")
      (libsource (lib "eagle-import") (part "STRIP3"))
    )
    (comp (ref "J138")
      (value "STRIP3")
      (footprint "eagle-import:STRIP3")
      (libsource (lib "eagle-import") (part "STRIP3"))
    )
    (comp (ref "J139")
      (value "STRIP3")
      (footprint "eagle-import:STRIP3")
      (libsource (lib "eagle-import") (part "STRIP3"))
    )
    (comp (ref "J140")
      (value "STRIP3")
      (footprint "eagle-import:STRIP3")
      (libsource (lib "eagle-import") (part "STRIP3"))
    )
    (comp (ref "J141")
      (value "STRIP3")
      (footprint "eagle-import:STRIP3")
      (libsource (lib "eagle-import") (part "STRIP3"))
    )
    (comp (ref "J142")
      (value "STRIP3")
      (footprint "eagle-import:STRIP3")
      (libsource (lib "eagle-import") (part "STRIP3"))
    )
    (comp (ref "J143")
      (value "STRIP3")
      (footprint "eagle-import:STRIP3")
      (libsource (lib "eagle-import") (part "STRIP3"))
    )
    (comp (ref "J144")
      (value "STRIP3")
      (footprint "eagle-import:STRIP3")
      (libsource (lib "eagle-import") (part "STRIP3"))
    )
    (comp (ref "J145")
      (value "STRIP3")
      (footprint "eagle-import:STRIP3")
      (libsource (lib "eagle-import") (part "STRIP3"))
    )
    (comp (ref "J146")
      (value "STRIP3")
      (footprint "eagle-import:STRIP3")
      (libsource (lib "eagle-import") (part "STRIP3"))
    )
    (comp (ref "J147")
      (value "STRIP3")
      (footprint "eagle-import:STRIP3")
      (libsource (lib "eagle-import") (part "STRIP3"))
    )
    (comp (ref "J148")
      (value "STRIP3")
      (footprint "eagle-import:STRIP3")
      (libsource (lib "eagle-import") (part "STRIP3"))
    )
    (comp (ref "J149")
      (value "STRIP3")
      (footprint "eagle-import:STRIP3")
      (libsource (lib "eagle-import") (part "STRIP3"))
    )
    (comp (ref "J150")
      (value "STRIP3")
      (footprint "eagle-import:STRIP3")
      (libsource (lib "eagle-import") (part "STRIP3"))
    )
    (comp (ref "J151")
      (value "STRIP3")
      (footprint "eagle-import:STRIP3")
      (libsource (lib "eagle-import") (part "STRIP3"))
    )
    (comp (ref "J152")
      (value "STRIP3")
      (footprint "eagle-import:STRIP3")
      (libsource (lib "eagle-import") (part "STRIP3"))
    )
    (comp (ref "J153")
      (value "STRIP3")
      (footprint "eagle-import:STRIP3")
      (libsource (lib "eagle-import") (part "STRIP3"))
    )
    (comp (ref "J154")
      (value "STRIP3")
      (footprint "eagle-import:STRIP3")
      (libsource (lib "eagle-import") (part "STRIP3"))
    )
    (comp (ref "J155")
      (value "STRIP3")
      (footprint "eagle-import:STRIP3")
      (libsource (lib "eagle-import") (part "STRIP3"))
    )
    (comp (ref "J156")
      (value "STRIP3")
      (footprint "eagle-import:STRIP3")
      (libsource (lib "eagle-import") (part "STRIP3"))
    )
    (comp (ref "J157")
      (value "STRIP3")
      (footprint "eagle-import:STRIP3")
      (libsource (lib "eagle-import") (part "STRIP3"))
    )
    (comp (ref "J158")
      (value "STRIP3")
      (footprint "eagle-import:STRIP3")
      (libsource (lib "eagle-import") (part "STRIP3"))
    )
    (comp (ref "J159")
      (value "STRIP3")
      (footprint "eagle-import:STRIP3")
      (libsource (lib "eagle-import") (part "STRIP3"))
    )
    (comp (ref "J160")
      (value "STRIP3")
      (footprint "eagle-import:STRIP3")
      (libsource (lib "eagle-import") (part "STRIP3"))
    )
    (comp (ref "J161")
      (value "STRIP3")
      (footprint "eagle-import:STRIP3")
      (libsource (lib "eagle-import") (part "STRIP3"))
    )
    (comp (ref "J162")
      (value "STRIP3")
      (footprint "eagle-import:STRIP3")
      (libsource (lib "eagle-import") (part "STRIP3"))
    )
    (comp (ref "J163")
      (value "STRIP3")
      (footprint "eagle-import:STRIP3")
      (libsource (lib "eagle-import") (part "STRIP3"))
    )
    (comp (ref "J164")
      (value "STRIP3")
      (footprint "eagle-import:STRIP3")
      (libsource (lib "eagle-import") (part "STRIP3"))
    )
    (comp (ref "J165")
      (value "STRIP3")
      (footprint "eagle-import:STRIP3")
      (libsource (lib "eagle-import") (part "STRIP3"))
    )
    (comp (ref "J166")
      (value "STRIP3")
      (footprint "eagle-import:STRIP3")
      (libsource (lib "eagle-import") (part "STRIP3"))
    )
    (comp (ref "J167")
      (value "STRIP3")
      (footprint "eagle-import:STRIP3")
      (libsource (lib "eagle-import") (part "STRIP3"))
    )
    (comp (ref "J168")
      (value "STRIP3")
      (footprint "eagle-import:STRIP3")
      (libsource (lib "eagle-import") (part "STRIP3"))
    )
    (comp (ref "J169")
      (value "STRIP3")
      (footprint "eagle-import:STRIP3")
      (libsource (lib "eagle-import") (part "STRIP3"))
    )
    (comp (ref "J170")
      (value "STRIP3")
      (footprint "eagle-import:STRIP3")
      (libsource (lib "eagle-import") (part "STRIP3"))
    )
    (comp (ref "J176")
      (value "STRIP3")
      (footprint "eagle-import:STRIP3")
      (libsource (lib "eagle-import") (part "STRIP3"))
    )
    (comp (ref "J177")
      (value "STRIP3")
      (footprint "eagle-import:STRIP3")
      (libsource (lib "eagle-import") (part "STRIP3"))
    )
    (comp (ref "J204")
      (value "STRIP2")
      (footprint "eagle-import:STRIP2")
      (libsource (lib "eagle-import") (part "STRIP2"))
    )
    (comp (ref "J205")
      (value "STRIP2")
      (footprint "eagle-import:STRIP2")
      (libsource (lib "eagle-import") (part "STRIP2"))
    )
    (comp (ref "J206")
      (value "STRIP2")
      (footprint "eagle-import:STRIP2")
      (libsource (lib "eagle-import") (part "STRIP2"))
    )
    (comp (ref "J207")
      (value "STRIP2")
      (footprint "eagle-import:STRIP2")
      (libsource (lib "eagle-import") (part "STRIP2"))
    )
    (comp (ref "J251")
      (value "STRIP2")
      (footprint "eagle-import:STRIP2")
      (libsource (lib "eagle-import") (part "STRIP2"))
    )
    (comp (ref "L1")
      (value "F28379D_LAUNCHPAD")
      (footprint "eagle-import:F28379D_LAUNCHPAD")
      (libsource (lib "eagle-import") (part "F28379D_LAUNCHPAD"))
    )
    (comp (ref "POWER")
      (value "PINHD-1X2")
      (footprint "eagle-import:1X02")
      (libsource (lib "eagle-import") (part "PINHD-1X2"))
    )
    (comp (ref "R26")
      (value "470")
      (footprint "eagle-import:M1206")
      (libsource (lib "eagle-import") (part "R-US_M1206"))
    )
    (comp (ref "R27")
      (value "470")
      (footprint "eagle-import:M1206")
      (libsource (lib "eagle-import") (part "R-US_M1206"))
    )
    (comp (ref "S141")
      (value "STRIP5")
      (footprint "eagle-import:STRIP5")
      (libsource (lib "eagle-import") (part "STRIP5"))
    )
    (comp (ref "U$1")
      (value "MPU-9250-BB")
      (footprint "eagle-import:MPU-9250-BB")
      (libsource (lib "eagle-import") (part "MPU-9250-BB"))
    )
    (comp (ref "C1")
      (value "47uF")
      (footprint "eagle-import:153CLV-0810")
      (libsource (lib "eagle-import") (part "CPOL-US153CLV-0810"))
    )
    (comp (ref "C2")
      (value "680pF")
      (footprint "eagle-import:C1206")
      (libsource (lib "eagle-import") (part "C-USC1206"))
    )
    (comp (ref "C12")
      (value "47uF")
      (footprint "eagle-import:153CLV-0810")
      (libsource (lib "eagle-import") (part "CPOL-US153CLV-0810"))
    )
    (comp (ref "C13")
      (value "47uF")
      (footprint "eagle-import:153CLV-0810")
      (libsource (lib "eagle-import") (part "CPOL-US153CLV-0810"))
    )
    (comp (ref "C14")
      (value "680pF")
      (footprint "eagle-import:C1206")
      (libsource (lib "eagle-import") (part "C-USC1206"))
    )
    (comp (ref "C15")
      (value "47uF")
      (footprint "eagle-import:153CLV-0810")
      (libsource (lib "eagle-import") (part "CPOL-US153CLV-0810"))
    )
    (comp (ref "C16")
      (value "0.1uF")
      (footprint "eagle-import:C1206")
      (libsource (lib "eagle-import") (part "C-USC1206"))
    )
    (comp (ref "C17")
      (value "0.1uF")
      (footprint "eagle-import:C1206")
      (libsource (lib "eagle-import") (part "C-USC1206"))
    )
    (comp (ref "C19")
      (value "22nF")
      (footprint "eagle-import:C1206")
      (libsource (lib "eagle-import") (part "C-USC1206"))
    )
    (comp (ref "C20")
      (value "47uF")
      (footprint "eagle-import:153CLV-0810")
      (libsource (lib "eagle-import") (part "CPOL-US153CLV-0810"))
    )
    (comp (ref "C22")
      (value "0.1uF")
      (footprint "eagle-import:C1206")
      (libsource (lib "eagle-import") (part "C-USC1206"))
    )
    (comp (ref "C23")
      (value "0.1uF")
      (footprint "eagle-import:C1206")
      (libsource (lib "eagle-import") (part "C-USC1206"))
    )
    (comp (ref "C24")
      (value "22nF")
      (footprint "eagle-import:C1206")
      (libsource (lib "eagle-import") (part "C-USC1206"))
    )
    (comp (ref "C25")
      (value "47uF")
      (footprint "eagle-import:153CLV-0810")
      (libsource (lib "eagle-import") (part "CPOL-US153CLV-0810"))
    )
    (comp (ref "C27")
      (value "47uF")
      (footprint "eagle-import:153CLV-0810")
      (libsource (lib "eagle-import") (part "CPOL-US153CLV-0810"))
    )
    (comp (ref "C28")
      (value "47uF")
      (footprint "eagle-import:153CLV-0810")
      (libsource (lib "eagle-import") (part "CPOL-US153CLV-0810"))
    )
    (comp (ref "J4")
      (value "STRIP3")
      (footprint "eagle-import:STRIP3")
      (libsource (lib "eagle-import") (part "STRIP3"))
    )
    (comp (ref "J6")
      (value "STRIP3")
      (footprint "eagle-import:STRIP3")
      (libsource (lib "eagle-import") (part "STRIP3"))
    )
    (comp (ref "J23")
      (value "STRIP3")
      (footprint "eagle-import:STRIP3")
      (libsource (lib "eagle-import") (part "STRIP3"))
    )
    (comp (ref "J24")
      (value "STRIP3")
      (footprint "eagle-import:STRIP3")
      (libsource (lib "eagle-import") (part "STRIP3"))
    )
    (comp (ref "J25")
      (value "STRIP2")
      (footprint "eagle-import:STRIP2")
      (libsource (lib "eagle-import") (part "STRIP2"))
    )
    (comp (ref "J26")
      (value "STRIP2")
      (footprint "eagle-import:STRIP2")
      (libsource (lib "eagle-import") (part "STRIP2"))
    )
    (comp (ref "J27")
      (value "STRIP2")
      (footprint "eagle-import:STRIP2")
      (libsource (lib "eagle-import") (part "STRIP2"))
    )
    (comp (ref "J34")
      (value "STRIP2")
      (footprint "eagle-import:STRIP2")
      (libsource (lib "eagle-import") (part "STRIP2"))
    )
    (comp (ref "J78")
      (value "STRIP2")
      (footprint "eagle-import:STRIP2")
      (libsource (lib "eagle-import") (part "STRIP2"))
    )
    (comp (ref "J79")
      (value "STRIP2")
      (footprint "eagle-import:STRIP2")
      (libsource (lib "eagle-import") (part "STRIP2"))
    )
    (comp (ref "J80")
      (value "STRIP2")
      (footprint "eagle-import:STRIP2")
      (libsource (lib "eagle-import") (part "STRIP2"))
    )
    (comp (ref "J81")
      (value "STRIP2")
      (footprint "eagle-import:STRIP2")
      (libsource (lib "eagle-import") (part "STRIP2"))
    )
    (comp (ref "J82")
      (value "STRIP2")
      (footprint "eagle-import:STRIP2")
      (libsource (lib "eagle-import") (part "STRIP2"))
    )
    (comp (ref "J83")
      (value "STRIP2")
      (footprint "eagle-import:STRIP2")
      (libsource (lib "eagle-import") (part "STRIP2"))
    )
    (comp (ref "J84")
      (value "STRIP2")
      (footprint "eagle-import:STRIP2")
      (libsource (lib "eagle-import") (part "STRIP2"))
    )
    (comp (ref "J85")
      (value "STRIP2")
      (footprint "eagle-import:STRIP2")
      (libsource (lib "eagle-import") (part "STRIP2"))
    )
    (comp (ref "J86")
      (value "STRIP2")
      (footprint "eagle-import:STRIP2")
      (libsource (lib "eagle-import") (part "STRIP2"))
    )
    (comp (ref "J87")
      (value "STRIP2")
      (footprint "eagle-import:STRIP2")
      (libsource (lib "eagle-import") (part "STRIP2"))
    )
    (comp (ref "J196")
      (value "STRIP2")
      (footprint "eagle-import:STRIP2")
      (libsource (lib "eagle-import") (part "STRIP2"))
    )
    (comp (ref "J197")
      (value "STRIP2")
      (footprint "eagle-import:STRIP2")
      (libsource (lib "eagle-import") (part "STRIP2"))
    )
    (comp (ref "J198")
      (value "STRIP2")
      (footprint "eagle-import:STRIP2")
      (libsource (lib "eagle-import") (part "STRIP2"))
    )
    (comp (ref "J199")
      (value "STRIP2")
      (footprint "eagle-import:STRIP2")
      (libsource (lib "eagle-import") (part "STRIP2"))
    )
    (comp (ref "J200")
      (value "STRIP2")
      (footprint "eagle-import:STRIP2")
      (libsource (lib "eagle-import") (part "STRIP2"))
    )
    (comp (ref "J201")
      (value "STRIP2")
      (footprint "eagle-import:STRIP2")
      (libsource (lib "eagle-import") (part "STRIP2"))
    )
    (comp (ref "J202")
      (value "STRIP2")
      (footprint "eagle-import:STRIP2")
      (libsource (lib "eagle-import") (part "STRIP2"))
    )
    (comp (ref "J203")
      (value "STRIP2")
      (footprint "eagle-import:STRIP2")
      (libsource (lib "eagle-import") (part "STRIP2"))
    )
    (comp (ref "JP2")
      (value "JP1E")
      (footprint "eagle-import:JP1")
      (libsource (lib "eagle-import") (part "JP1E"))
    )
    (comp (ref "JP3")
      (value "JP1E")
      (footprint "eagle-import:JP1")
      (libsource (lib "eagle-import") (part "JP1E"))
    )
    (comp (ref "R1")
      (value "R_B")
      (footprint "eagle-import:0207_10")
      (libsource (lib "eagle-import") (part "R-US_0207/10"))
    )
    (comp (ref "R2")
      (value "R_B")
      (footprint "eagle-import:0207_10")
      (libsource (lib "eagle-import") (part "R-US_0207/10"))
    )
    (comp (ref "R3")
      (value "24.9K")
      (footprint "eagle-import:M1206")
      (libsource (lib "eagle-import") (part "R-US_M1206"))
    )
    (comp (ref "R4")
      (value "2.2K")
      (footprint "eagle-import:M1206")
      (libsource (lib "eagle-import") (part "R-US_M1206"))
    )
    (comp (ref "R5")
      (value "2.2K")
      (footprint "eagle-import:M1206")
      (libsource (lib "eagle-import") (part "R-US_M1206"))
    )
    (comp (ref "R6")
      (value "2.2K")
      (footprint "eagle-import:M1206")
      (libsource (lib "eagle-import") (part "R-US_M1206"))
    )
    (comp (ref "R7")
      (value "24.9K")
      (footprint "eagle-import:M1206")
      (libsource (lib "eagle-import") (part "R-US_M1206"))
    )
    (comp (ref "R8")
      (value "2.2K")
      (footprint "eagle-import:M1206")
      (libsource (lib "eagle-import") (part "R-US_M1206"))
    )
    (comp (ref "R18")
      (value "2.2K")
      (footprint "eagle-import:M1206")
      (libsource (lib "eagle-import") (part "R-US_M1206"))
    )
    (comp (ref "R24")
      (value "2.2K")
      (footprint "eagle-import:M1206")
      (libsource (lib "eagle-import") (part "R-US_M1206"))
    )
    (comp (ref "R41")
      (value "1.8K")
      (footprint "eagle-import:M1206")
      (libsource (lib "eagle-import") (part "R-US_M1206"))
    )
    (comp (ref "R42")
      (value "10K")
      (footprint "eagle-import:M1206")
      (libsource (lib "eagle-import") (part "R-US_M1206"))
    )
    (comp (ref "R43")
      (value "1.8K")
      (footprint "eagle-import:M1206")
      (libsource (lib "eagle-import") (part "R-US_M1206"))
    )
    (comp (ref "R44")
      (value "10K")
      (footprint "eagle-import:M1206")
      (libsource (lib "eagle-import") (part "R-US_M1206"))
    )
    (comp (ref "S1")
      (value "SWITCH_A4793")
      (footprint "eagle-import:SWITCH_SLIDE")
      (libsource (lib "eagle-import") (part "SWITCH_SLIDE"))
    )
    (comp (ref "S129")
      (value "STRIP5")
      (footprint "eagle-import:STRIP5")
      (libsource (lib "eagle-import") (part "STRIP5"))
    )
    (comp (ref "S130")
      (value "STRIP5")
      (footprint "eagle-import:STRIP5")
      (libsource (lib "eagle-import") (part "STRIP5"))
    )
    (comp (ref "S137")
      (value "STRIP5")
      (footprint "eagle-import:STRIP5")
      (libsource (lib "eagle-import") (part "STRIP5"))
    )
    (comp (ref "S138")
      (value "STRIP5")
      (footprint "eagle-import:STRIP5")
      (libsource (lib "eagle-import") (part "STRIP5"))
    )
    (comp (ref "S139")
      (value "STRIP5")
      (footprint "eagle-import:STRIP5")
      (libsource (lib "eagle-import") (part "STRIP5"))
    )
    (comp (ref "S147")
      (value "STRIP5")
      (footprint "eagle-import:STRIP5")
      (libsource (lib "eagle-import") (part "STRIP5"))
    )
    (comp (ref "S159")
      (value "SWITCH_DRV8874")
      (footprint "eagle-import:SWITCH_SLIDE")
      (libsource (lib "eagle-import") (part "SWITCH_SLIDE"))
    )
    (comp (ref "SV1")
      (value "MA03-2")
      (footprint "eagle-import:MA03-2")
      (libsource (lib "eagle-import") (part "MA03-2"))
    )
    (comp (ref "SV3")
      (value "MA03-2")
      (footprint "eagle-import:MA03-2")
      (libsource (lib "eagle-import") (part "MA03-2"))
    )
    (comp (ref "SV7")
      (value "MA03-2")
      (footprint "eagle-import:MA03-2")
      (libsource (lib "eagle-import") (part "MA03-2"))
    )
    (comp (ref "SV8")
      (value "MA03-2")
      (footprint "eagle-import:MA03-2")
      (libsource (lib "eagle-import") (part "MA03-2"))
    )
    (comp (ref "T1")
      (value "TIP125")
      (footprint "eagle-import:TO220")
      (libsource (lib "eagle-import") (part "TIP125"))
    )
    (comp (ref "T2")
      (value "TIP125")
      (footprint "eagle-import:TO220")
      (libsource (lib "eagle-import") (part "TIP125"))
    )
    (comp (ref "TRIMPOT1")
      (value "MA03-2")
      (footprint "eagle-import:MA03-2")
      (libsource (lib "eagle-import") (part "MA03-2"))
    )
    (comp (ref "TRIMPOT2")
      (value "MA03-2")
      (footprint "eagle-import:MA03-2")
      (libsource (lib "eagle-import") (part "MA03-2"))
    )
    (comp (ref "U$2")
      (value "GEARMOTOR_MOUNT")
      (footprint "eagle-import:GEARMOTOR_MOUNT")
      (libsource (lib "eagle-import") (part "GEARMOTOR_MOUNT"))
    )
    (comp (ref "U$3")
      (value "GEARMOTOR_MOUNT")
      (footprint "eagle-import:GEARMOTOR_MOUNT")
      (libsource (lib "eagle-import") (part "GEARMOTOR_MOUNT"))
    )
    (comp (ref "U1")
      (value "A4973")
      (footprint "eagle-import:SO16W")
      (libsource (lib "eagle-import") (part "A3953"))
    )
    (comp (ref "U2")
      (value "DRV8874")
      (footprint "eagle-import:HTSSOP16")
      (libsource (lib "eagle-import") (part "DRV8874"))
    )
    (comp (ref "U4")
      (value "DRV8874")
      (footprint "eagle-import:HTSSOP16")
      (libsource (lib "eagle-import") (part "DRV8874"))
    )
    (comp (ref "U5")
      (value "A4973")
      (footprint "eagle-import:SO16W")
      (libsource (lib "eagle-import") (part "A3953"))
    )
    (comp (ref "B3")
      (value "GND SCOPE")
      (footprint "eagle-import:BANANA_MALE")
      (libsource (lib "eagle-import") (part "BANANA_MALE"))
    )
    (comp (ref "B4")
      (value "ADC SCOPE")
      (footprint "eagle-import:BANANA_MALE")
      (libsource (lib "eagle-import") (part "BANANA_MALE"))
    )
    (comp (ref "B5")
      (value "DAC SCOPE")
      (footprint "eagle-import:BANANA_MALE")
      (libsource (lib "eagle-import") (part "BANANA_MALE"))
    )
    (comp (ref "C3")
      (value "0.1uf")
      (footprint "eagle-import:C1206")
      (libsource (lib "eagle-import") (part "C-USC1206"))
    )
    (comp (ref "C5")
      (value "0.1 uF")
      (footprint "eagle-import:C1206")
      (libsource (lib "eagle-import") (part "C-USC1206"))
    )
    (comp (ref "C7")
      (value "2.2 uF")
      (footprint "eagle-import:C1206")
      (libsource (lib "eagle-import") (part "C-USC1206"))
    )
    (comp (ref "C8")
      (value "2.2 uF")
      (footprint "eagle-import:C1206")
      (libsource (lib "eagle-import") (part "C-USC1206"))
    )
    (comp (ref "C11")
      (value "2.2 uF")
      (footprint "eagle-import:C1206")
      (libsource (lib "eagle-import") (part "C-USC1206"))
    )
    (comp (ref "C18")
      (value "2.2 uF")
      (footprint "eagle-import:C1206")
      (libsource (lib "eagle-import") (part "C-USC1206"))
    )
    (comp (ref "J35")
      (value "STRIP2")
      (footprint "eagle-import:STRIP2")
      (libsource (lib "eagle-import") (part "STRIP2"))
    )
    (comp (ref "J36")
      (value "STRIP2")
      (footprint "eagle-import:STRIP2")
      (libsource (lib "eagle-import") (part "STRIP2"))
    )
    (comp (ref "J37")
      (value "STRIP2")
      (footprint "eagle-import:STRIP2")
      (libsource (lib "eagle-import") (part "STRIP2"))
    )
    (comp (ref "J38")
      (value "STRIP2")
      (footprint "eagle-import:STRIP2")
      (libsource (lib "eagle-import") (part "STRIP2"))
    )
    (comp (ref "LED17")
      (value "LEDCHIPLED_1206")
      (footprint "eagle-import:CHIPLED_1206")
      (libsource (lib "eagle-import") (part "LEDCHIPLED_1206"))
    )
    (comp (ref "P1")
      (value "TH_PUSHBOTTON")
      (footprint "eagle-import:TH_PUSHBUTTON")
      (libsource (lib "eagle-import") (part "TH_PUSHBOTTON"))
    )
    (comp (ref "R32")
      (value "4.7K")
      (footprint "eagle-import:M1206")
      (libsource (lib "eagle-import") (part "R-US_M1206"))
    )
    (comp (ref "R33")
      (value "4.7K")
      (footprint "eagle-import:M1206")
      (libsource (lib "eagle-import") (part "R-US_M1206"))
    )
    (comp (ref "R34")
      (value "4.7k")
      (footprint "eagle-import:M1206")
      (libsource (lib "eagle-import") (part "R-US_M1206"))
    )
    (comp (ref "R35")
      (value "4.7k")
      (footprint "eagle-import:M1206")
      (libsource (lib "eagle-import") (part "R-US_M1206"))
    )
    (comp (ref "R36")
      (value "1K")
      (footprint "eagle-import:M1206")
      (libsource (lib "eagle-import") (part "R-US_M1206"))
    )
    (comp (ref "R37")
      (value "4.7k")
      (footprint "eagle-import:M1206")
      (libsource (lib "eagle-import") (part "R-US_M1206"))
    )
    (comp (ref "R38")
      (value "4.7k")
      (footprint "eagle-import:M1206")
      (libsource (lib "eagle-import") (part "R-US_M1206"))
    )
    (comp (ref "S17")
      (value "STRIP5")
      (footprint "eagle-import:STRIP5")
      (libsource (lib "eagle-import") (part "STRIP5"))
    )
    (comp (ref "S18")
      (value "STRIP5")
      (footprint "eagle-import:STRIP5")
      (libsource (lib "eagle-import") (part "STRIP5"))
    )
    (comp (ref "S20")
      (value "STRIP10")
      (footprint "eagle-import:STRIP10")
      (libsource (lib "eagle-import") (part "STRIP10"))
    )
    (comp (ref "S24")
      (value "STRIP10")
      (footprint "eagle-import:STRIP10")
      (libsource (lib "eagle-import") (part "STRIP10"))
    )
    (comp (ref "S53")
      (value "STRIP10")
      (footprint "eagle-import:STRIP10")
      (libsource (lib "eagle-import") (part "STRIP10"))
    )
    (comp (ref "S58")
      (value "STRIP10")
      (footprint "eagle-import:STRIP10")
      (libsource (lib "eagle-import") (part "STRIP10"))
    )
    (comp (ref "SV9")
      (value "MA03-1")
      (footprint "eagle-import:MA03-1")
      (libsource (lib "eagle-import") (part "MA03-1"))
    )
    (comp (ref "SV10")
      (value "MA03-1")
      (footprint "eagle-import:MA03-1")
      (libsource (lib "eagle-import") (part "MA03-1"))
    )
    (comp (ref "SV14")
      (value "MA07-2")
      (footprint "eagle-import:MA07-2")
      (libsource (lib "eagle-import") (part "MA07-2"))
    )
    (comp (ref "SV15")
      (value "MA08-2")
      (footprint "eagle-import:MA08-2")
      (libsource (lib "eagle-import") (part "MA08-2"))
    )
    (comp (ref "U6")
      (value "MAX4506")
      (footprint "eagle-import:SOIC-8")
      (libsource (lib "eagle-import") (part "MAX4506-SOIC8"))
    )
    (comp (ref "U8")
      (value "F28027")
      (footprint "eagle-import:DA38")
      (libsource (lib "eagle-import") (part "TMS320F28027DAS"))
    )
  )
  (nets
    (net (code "1") (name "+5V") (class "Default")
      (node (ref "DCDC5V") (pin "3") (pinfunction "3_3") (pintype "passive"))
      (node (ref "J103") (pin "P$1") (pinfunction "P$1_P$1") (pintype "bidirectional"))
      (node (ref "J103") (pin "P$2") (pinfunction "P$2_P$2") (pintype "bidirectional"))
      (node (ref "J103") (pin "P$3") (pinfunction "P$3_P$3") (pintype "bidirectional"))
      (node (ref "J152") (pin "P$1") (pinfunction "P$1_P$1") (pintype "bidirectional"))
      (node (ref "J152") (pin "P$2") (pinfunction "P$2_P$2") (pintype "bidirectional"))
      (node (ref "J152") (pin "P$3") (pinfunction "P$3_P$3") (pintype "bidirectional"))
      (node (ref "J200") (pin "P$1") (pinfunction "P$1_P$1") (pintype "bidirectional"))
      (node (ref "J200") (pin "P$2") (pinfunction "P$2_P$2") (pintype "bidirectional"))
      (node (ref "J203") (pin "P$1") (pinfunction "P$1_P$1") (pintype "bidirectional"))
      (node (ref "J203") (pin "P$2") (pinfunction "P$2_P$2") (pintype "bidirectional"))
      (node (ref "L1") (pin "P$21") (pinfunction "5V_1_P$21") (pintype "bidirectional"))
      (node (ref "L1") (pin "P$61") (pinfunction "5V_2_P$61") (pintype "bidirectional"))
      (node (ref "R26") (pin "2") (pinfunction "2_2") (pintype "passive"))
      (node (ref "S17") (pin "P$1") (pinfunction "P$1_P$1") (pintype "bidirectional"))
      (node (ref "S17") (pin "P$2") (pinfunction "P$2_P$2") (pintype "bidirectional"))
      (node (ref "S17") (pin "P$3") (pinfunction "P$3_P$3") (pintype "bidirectional"))
      (node (ref "S17") (pin "P$4") (pinfunction "P$4_P$4") (pintype "bidirectional"))
      (node (ref "S17") (pin "P$5") (pinfunction "P$5_P$5") (pintype "bidirectional"))
      (node (ref "S18") (pin "P$1") (pinfunction "P$1_P$1") (pintype "bidirectional"))
      (node (ref "S18") (pin "P$2") (pinfunction "P$2_P$2") (pintype "bidirectional"))
      (node (ref "S18") (pin "P$3") (pinfunction "P$3_P$3") (pintype "bidirectional"))
      (node (ref "S18") (pin "P$4") (pinfunction "P$4_P$4") (pintype "bidirectional"))
      (node (ref "S18") (pin "P$5") (pinfunction "P$5_P$5") (pintype "bidirectional"))
      (node (ref "SV2") (pin "1") (pinfunction "1_1") (pintype "passive"))
      (node (ref "SV2") (pin "2") (pinfunction "2_2") (pintype "passive"))
      (node (ref "SV2") (pin "3") (pinfunction "3_3") (pintype "passive"))
      (node (ref "SV2") (pin "4") (pinfunction "4_4") (pintype "passive"))
    )
    (net (code "2") (name "28027_GPIO0") (class "Default")
      (node (ref "J26") (pin "P$1") (pinfunction "P$1_P$1") (pintype "bidirectional"))
      (node (ref "J26") (pin "P$2") (pinfunction "P$2_P$2") (pintype "bidirectional"))
      (node (ref "U8") (pin "37") (pinfunction "GPIO0/EPWM1A_37") (pintype "bidirectional"))
    )
    (net (code "3") (name "28027_GPIO1") (class "Default")
      (node (ref "J27") (pin "P$1") (pinfunction "P$1_P$1") (pintype "bidirectional"))
      (node (ref "J27") (pin "P$2") (pinfunction "P$2_P$2") (pintype "bidirectional"))
      (node (ref "U8") (pin "36") (pinfunction "GPIO1/EPWM1A_36") (pintype "bidirectional"))
    )
    (net (code "4") (name "28027_GPIO2") (class "Default")
      (node (ref "SV15") (pin "16") (pinfunction "16_16") (pintype "passive"))
      (node (ref "U8") (pin "5") (pinfunction "GPIO2/EPWM2A_5") (pintype "bidirectional"))
    )
    (net (code "5") (name "28027_GPIO3") (class "Default")
      (node (ref "SV15") (pin "14") (pinfunction "14_14") (pintype "passive"))
      (node (ref "U8") (pin "6") (pinfunction "GPIO3/EPWM2B_6") (pintype "bidirectional"))
    )
    (net (code "6") (name "28027_GPIO4") (class "Default")
      (node (ref "SV15") (pin "12") (pinfunction "12_12") (pintype "passive"))
      (node (ref "U8") (pin "7") (pinfunction "GPIO4/EPWM3A_7") (pintype "bidirectional"))
    )
    (net (code "7") (name "28027_GPIO5") (class "Default")
      (node (ref "SV15") (pin "10") (pinfunction "10_10") (pintype "passive"))
      (node (ref "U8") (pin "8") (pinfunction "GPIO5/EPWM3B_8") (pintype "bidirectional"))
    )
    (net (code "8") (name "28027_GPIO6") (class "Default")
      (node (ref "SV15") (pin "8") (pinfunction "8_8") (pintype "passive"))
      (node (ref "U8") (pin "9") (pinfunction "GPIO6/EPWM4A_9") (pintype "bidirectional"))
    )
    (net (code "9") (name "28027_GPIO7") (class "Default")
      (node (ref "SV15") (pin "6") (pinfunction "6_6") (pintype "passive"))
      (node (ref "U8") (pin "10") (pinfunction "GPIO7/EPWM4B_10") (pintype "bidirectional"))
    )
    (net (code "10") (name "28027_GPIO12") (class "Default")
      (node (ref "SV15") (pin "4") (pinfunction "4_4") (pintype "passive"))
      (node (ref "U8") (pin "13") (pinfunction "GPIO12/SCITXDA_13") (pintype "bidirectional"))
    )
    (net (code "11") (name "28027_GPIO34") (class "Default")
      (node (ref "LED17") (pin "C") (pinfunction "C_C") (pintype "passive"))
      (node (ref "R37") (pin "1") (pinfunction "1_1") (pintype "passive"))
      (node (ref "U8") (pin "27") (pinfunction "GPIO34_27") (pintype "bidirectional"))
    )
    (net (code "12") (name "28027_SCL") (class "Default")
      (node (ref "R34") (pin "2") (pinfunction "2_2") (pintype "passive"))
      (node (ref "SV15") (pin "3") (pinfunction "3_3") (pintype "passive"))
      (node (ref "U8") (pin "15") (pinfunction "GPIO29/SCITXDA_15") (pintype "bidirectional"))
    )
    (net (code "13") (name "28027_SDA") (class "Default")
      (node (ref "R35") (pin "2") (pinfunction "2_2") (pintype "passive"))
      (node (ref "SV15") (pin "5") (pinfunction "5_5") (pintype "passive"))
      (node (ref "U8") (pin "14") (pinfunction "GPIO28/SCIRXDA_14") (pintype "bidirectional"))
    )
    (net (code "14") (name "28027_SPICLKA") (class "Default")
      (node (ref "J38") (pin "P$1") (pinfunction "P$1_P$1") (pintype "bidirectional"))
      (node (ref "U8") (pin "32") (pinfunction "GPIO18/SPICLKA/SCITXDA_32") (pintype "bidirectional"))
    )
    (net (code "15") (name "28027_SPISIMOA") (class "Default")
      (node (ref "J36") (pin "P$1") (pinfunction "P$1_P$1") (pintype "bidirectional"))
      (node (ref "U8") (pin "35") (pinfunction "GPIO16/SPISIMOA_35") (pintype "bidirectional"))
    )
    (net (code "16") (name "28027_SPISOMIA") (class "Default")
      (node (ref "J35") (pin "P$1") (pinfunction "P$1_P$1") (pintype "bidirectional"))
      (node (ref "U8") (pin "34") (pinfunction "GPIO17/SPISOMIA_34") (pintype "bidirectional"))
    )
    (net (code "17") (name "28027_SPISTEA") (class "Default")
      (node (ref "J37") (pin "P$1") (pinfunction "P$1_P$1") (pintype "bidirectional"))
      (node (ref "U8") (pin "33") (pinfunction "GPIO19//SPISTEA/SCIRXDA_33") (pintype "bidirectional"))
    )
    (net (code "18") (name "A4973EN") (class "Default")
      (node (ref "S1") (pin "P$2") (pinfunction "P2_P$2") (pintype "bidirectional"))
      (node (ref "U1") (pin "8") (pinfunction "~{ENABLE}_8") (pintype "bidirectional"))
      (node (ref "U5") (pin "8") (pinfunction "~{ENABLE}_8") (pintype "bidirectional"))
    )
    (net (code "19") (name "ADCA0") (class "Default")
      (node (ref "SV15") (pin "7") (pinfunction "7_7") (pintype "passive"))
      (node (ref "U8") (pin "21") (pinfunction "ADCINA0/VREFHI_21") (pintype "bidirectional"))
    )
    (net (code "20") (name "ADCA2") (class "Default")
      (node (ref "SV15") (pin "9") (pinfunction "9_9") (pintype "passive"))
      (node (ref "U8") (pin "20") (pinfunction "ADCINA2/AIO2_20") (pintype "bidirectional"))
    )
    (net (code "21") (name "ADCA4") (class "Default")
      (node (ref "SV15") (pin "13") (pinfunction "13_13") (pintype "passive"))
      (node (ref "U8") (pin "19") (pinfunction "ADCINA4/AIO4_19") (pintype "bidirectional"))
    )
    (net (code "22") (name "ADCA6") (class "Default")
      (node (ref "SV15") (pin "2") (pinfunction "2_2") (pintype "passive"))
      (node (ref "U8") (pin "18") (pinfunction "ADCINA6/AIO6_18") (pintype "bidirectional"))
    )
    (net (code "23") (name "ADCB2") (class "Default")
      (node (ref "SV15") (pin "11") (pinfunction "11_11") (pintype "passive"))
      (node (ref "U8") (pin "24") (pinfunction "ADCINB2/AIO10_24") (pintype "bidirectional"))
    )
    (net (code "24") (name "ADCB4") (class "Default")
      (node (ref "SV15") (pin "15") (pinfunction "15_15") (pintype "passive"))
      (node (ref "U8") (pin "25") (pinfunction "ADCINB4/AIO12_25") (pintype "bidirectional"))
    )
    (net (code "25") (name "ADCB6") (class "Default")
      (node (ref "U8") (pin "26") (pinfunction "ADCINB6/AIO14_26") (pintype "bidirectional"))
    )
    (net (code "26") (name "ADCIN14") (class "Default")
      (node (ref "J105") (pin "P$1") (pinfunction "P$1_P$1") (pintype "bidirectional"))
      (node (ref "J105") (pin "P$2") (pinfunction "P$2_P$2") (pintype "bidirectional"))
      (node (ref "J105") (pin "P$3") (pinfunction "P$3_P$3") (pintype "bidirectional"))
      (node (ref "L1") (pin "P$23") (pinfunction "ADCIN14_P$23") (pintype "bidirectional"))
    )
    (net (code "27") (name "ADCIN15") (class "Default")
      (node (ref "J150") (pin "P$1") (pinfunction "P$1_P$1") (pintype "bidirectional"))
      (node (ref "J150") (pin "P$2") (pinfunction "P$2_P$2") (pintype "bidirectional"))
      (node (ref "J150") (pin "P$3") (pinfunction "P$3_P$3") (pintype "bidirectional"))
      (node (ref "L1") (pin "P$63") (pinfunction "ADCIN15_P$63") (pintype "bidirectional"))
    )
    (net (code "28") (name "ADCINA2") (class "Default")
      (node (ref "J111") (pin "P$1") (pinfunction "P$1_P$1") (pintype "bidirectional"))
      (node (ref "J111") (pin "P$2") (pinfunction "P$2_P$2") (pintype "bidirectional"))
      (node (ref "J111") (pin "P$3") (pinfunction "P$3_P$3") (pintype "bidirectional"))
      (node (ref "L1") (pin "P$29") (pinfunction "ADCINA2_P$29") (pintype "bidirectional"))
      (node (ref "SV11") (pin "3") (pinfunction "3_3") (pintype "passive"))
    )
    (net (code "29") (name "ADCINA3") (class "Default")
      (node (ref "J108") (pin "P$1") (pinfunction "P$1_P$1") (pintype "bidirectional"))
      (node (ref "J108") (pin "P$2") (pinfunction "P$2_P$2") (pintype "bidirectional"))
      (node (ref "J108") (pin "P$3") (pinfunction "P$3_P$3") (pintype "bidirectional"))
      (node (ref "L1") (pin "P$26") (pinfunction "ADCINA3_P$26") (pintype "bidirectional"))
      (node (ref "SV11") (pin "4") (pinfunction "4_4") (pintype "passive"))
    )
    (net (code "30") (name "ADCINA4") (class "Default")
      (node (ref "J144") (pin "P$1") (pinfunction "P$1_P$1") (pintype "bidirectional"))
      (node (ref "J144") (pin "P$2") (pinfunction "P$2_P$2") (pintype "bidirectional"))
      (node (ref "J144") (pin "P$3") (pinfunction "P$3_P$3") (pintype "bidirectional"))
      (node (ref "L1") (pin "P$69") (pinfunction "ADCINA4_P$69") (pintype "bidirectional"))
    )
    (net (code "31") (name "ADCINA5") (class "Default")
      (node (ref "J147") (pin "P$1") (pinfunction "P$1_P$1") (pintype "bidirectional"))
      (node (ref "J147") (pin "P$2") (pinfunction "P$2_P$2") (pintype "bidirectional"))
      (node (ref "J147") (pin "P$3") (pinfunction "P$3_P$3") (pintype "bidirectional"))
      (node (ref "L1") (pin "P$66") (pinfunction "ADCINA5_P$66") (pintype "bidirectional"))
    )
    (net (code "32") (name "ADCINB2") (class "Default")
      (node (ref "J110") (pin "P$1") (pinfunction "P$1_P$1") (pintype "bidirectional"))
      (node (ref "J110") (pin "P$2") (pinfunction "P$2_P$2") (pintype "bidirectional"))
      (node (ref "J110") (pin "P$3") (pinfunction "P$3_P$3") (pintype "bidirectional"))
      (node (ref "L1") (pin "P$28") (pinfunction "ADCINB2_P$28") (pintype "bidirectional"))
    )
    (net (code "33") (name "ADCINB3") (class "Default")
      (node (ref "J107") (pin "P$1") (pinfunction "P$1_P$1") (pintype "bidirectional"))
      (node (ref "J107") (pin "P$2") (pinfunction "P$2_P$2") (pintype "bidirectional"))
      (node (ref "J107") (pin "P$3") (pinfunction "P$3_P$3") (pintype "bidirectional"))
      (node (ref "L1") (pin "P$25") (pinfunction "ADCINB3_P$25") (pintype "bidirectional"))
    )
    (net (code "34") (name "ADCINB4") (class "Default")
      (node (ref "J145") (pin "P$1") (pinfunction "P$1_P$1") (pintype "bidirectional"))
      (node (ref "J145") (pin "P$2") (pinfunction "P$2_P$2") (pintype "bidirectional"))
      (node (ref "J145") (pin "P$3") (pinfunction "P$3_P$3") (pintype "bidirectional"))
      (node (ref "L1") (pin "P$68") (pinfunction "ADCINB4_P$68") (pintype "bidirectional"))
      (node (ref "SV12") (pin "4") (pinfunction "4_4") (pintype "passive"))
    )
    (net (code "35") (name "ADCINB5") (class "Default")
      (node (ref "J148") (pin "P$1") (pinfunction "P$1_P$1") (pintype "bidirectional"))
      (node (ref "J148") (pin "P$2") (pinfunction "P$2_P$2") (pintype "bidirectional"))
      (node (ref "J148") (pin "P$3") (pinfunction "P$3_P$3") (pintype "bidirectional"))
      (node (ref "L1") (pin "P$65") (pinfunction "ADCINB5_P$65") (pintype "bidirectional"))
    )
    (net (code "36") (name "ADCINC2") (class "Default")
      (node (ref "J109") (pin "P$1") (pinfunction "P$1_P$1") (pintype "bidirectional"))
      (node (ref "J109") (pin "P$2") (pinfunction "P$2_P$2") (pintype "bidirectional"))
      (node (ref "J109") (pin "P$3") (pinfunction "P$3_P$3") (pintype "bidirectional"))
      (node (ref "L1") (pin "P$27") (pinfunction "ADCINC2_P$27") (pintype "bidirectional"))
    )
    (net (code "37") (name "ADCINC3") (class "Default")
      (node (ref "J106") (pin "P$1") (pinfunction "P$1_P$1") (pintype "bidirectional"))
      (node (ref "J106") (pin "P$2") (pinfunction "P$2_P$2") (pintype "bidirectional"))
      (node (ref "J106") (pin "P$3") (pinfunction "P$3_P$3") (pintype "bidirectional"))
      (node (ref "L1") (pin "P$24") (pinfunction "ADCINC3_P$24") (pintype "bidirectional"))
    )
    (net (code "38") (name "ADCINC4") (class "Default")
      (node (ref "J146") (pin "P$1") (pinfunction "P$1_P$1") (pintype "bidirectional"))
      (node (ref "J146") (pin "P$2") (pinfunction "P$2_P$2") (pintype "bidirectional"))
      (node (ref "J146") (pin "P$3") (pinfunction "P$3_P$3") (pintype "bidirectional"))
      (node (ref "L1") (pin "P$67") (pinfunction "ADCINC4_P$67") (pintype "bidirectional"))
    )
    (net (code "39") (name "ADCINC5") (class "Default")
      (node (ref "J149") (pin "P$1") (pinfunction "P$1_P$1") (pintype "bidirectional"))
      (node (ref "J149") (pin "P$2") (pinfunction "P$2_P$2") (pintype "bidirectional"))
      (node (ref "J149") (pin "P$3") (pinfunction "P$3_P$3") (pintype "bidirectional"))
      (node (ref "L1") (pin "P$64") (pinfunction "ADCINC5_P$64") (pintype "bidirectional"))
    )
    (net (code "40") (name "DACOUTA") (class "Default")
      (node (ref "J112") (pin "P$1") (pinfunction "P$1_P$1") (pintype "bidirectional"))
      (node (ref "J112") (pin "P$2") (pinfunction "P$2_P$2") (pintype "bidirectional"))
      (node (ref "J112") (pin "P$3") (pinfunction "P$3_P$3") (pintype "bidirectional"))
      (node (ref "L1") (pin "P$30") (pinfunction "ADCINA0/DACOUTA_P$30") (pintype "bidirectional"))
    )
    (net (code "41") (name "DACOUTB") (class "Default")
      (node (ref "J143") (pin "P$1") (pinfunction "P$1_P$1") (pintype "bidirectional"))
      (node (ref "J143") (pin "P$2") (pinfunction "P$2_P$2") (pintype "bidirectional"))
      (node (ref "J143") (pin "P$3") (pinfunction "P$3_P$3") (pintype "bidirectional"))
      (node (ref "L1") (pin "P$70") (pinfunction "ADCINA1/DACOUTB_P$70") (pintype "bidirectional"))
    )
    (net (code "42") (name "DRV1_DIR") (class "Default")
      (node (ref "J80") (pin "P$1") (pinfunction "P$1_P$1") (pintype "bidirectional"))
      (node (ref "J80") (pin "P$2") (pinfunction "P$2_P$2") (pintype "bidirectional"))
      (node (ref "U2") (pin "P$2") (pinfunction "PH/IN2_P$2") (pintype "bidirectional"))
    )
    (net (code "43") (name "DRV1_M+") (class "Default")
      (node (ref "SV7") (pin "1") (pinfunction "1_1") (pintype "passive"))
      (node (ref "SV7") (pin "3") (pinfunction "3_3") (pintype "passive"))
      (node (ref "SV7") (pin "5") (pinfunction "5_5") (pintype "passive"))
      (node (ref "U2") (pin "P$8") (pinfunction "OUT1_P$8") (pintype "bidirectional"))
    )
    (net (code "44") (name "DRV1_M-") (class "Default")
      (node (ref "SV7") (pin "2") (pinfunction "2_2") (pintype "passive"))
      (node (ref "SV7") (pin "4") (pinfunction "4_4") (pintype "passive"))
      (node (ref "SV7") (pin "6") (pinfunction "6_6") (pintype "passive"))
      (node (ref "U2") (pin "P$10") (pinfunction "OUT2_P$10") (pintype "bidirectional"))
    )
    (net (code "45") (name "DRV1_PWM") (class "Default")
      (node (ref "J79") (pin "P$1") (pinfunction "P$1_P$1") (pintype "bidirectional"))
      (node (ref "J79") (pin "P$2") (pinfunction "P$2_P$2") (pintype "bidirectional"))
      (node (ref "U2") (pin "P$1") (pinfunction "EN/IN1_P$1") (pintype "bidirectional"))
    )
    (net (code "46") (name "DRV2_DIR") (class "Default")
      (node (ref "J83") (pin "P$1") (pinfunction "P$1_P$1") (pintype "bidirectional"))
      (node (ref "J83") (pin "P$2") (pinfunction "P$2_P$2") (pintype "bidirectional"))
      (node (ref "U4") (pin "P$2") (pinfunction "PH/IN2_P$2") (pintype "bidirectional"))
    )
    (net (code "47") (name "DRV2_M+") (class "Default")
      (node (ref "SV8") (pin "1") (pinfunction "1_1") (pintype "passive"))
      (node (ref "SV8") (pin "3") (pinfunction "3_3") (pintype "passive"))
      (node (ref "SV8") (pin "5") (pinfunction "5_5") (pintype "passive"))
      (node (ref "U4") (pin "P$8") (pinfunction "OUT1_P$8") (pintype "bidirectional"))
    )
    (net (code "48") (name "DRV2_M-") (class "Default")
      (node (ref "SV8") (pin "2") (pinfunction "2_2") (pintype "passive"))
      (node (ref "SV8") (pin "4") (pinfunction "4_4") (pintype "passive"))
      (node (ref "SV8") (pin "6") (pinfunction "6_6") (pintype "passive"))
      (node (ref "U4") (pin "P$10") (pinfunction "OUT2_P$10") (pintype "bidirectional"))
    )
    (net (code "49") (name "DRV2_PWM") (class "Default")
      (node (ref "J82") (pin "P$1") (pinfunction "P$1_P$1") (pintype "bidirectional"))
      (node (ref "J82") (pin "P$2") (pinfunction "P$2_P$2") (pintype "bidirectional"))
      (node (ref "U4") (pin "P$1") (pinfunction "EN/IN1_P$1") (pintype "bidirectional"))
    )
    (net (code "50") (name "GND") (class "Default")
      (node (ref "3V3") (pin "C") (pinfunction "C_C") (pintype "passive"))
      (node (ref "5V") (pin "C") (pinfunction "C_C") (pintype "passive"))
      (node (ref "B1") (pin "P$2") (pinfunction "P$2_P$2") (pintype "bidirectional"))
      (node (ref "B2") (pin "P$2") (pinfunction "BAT-_P$2") (pintype "bidirectional"))
      (node (ref "B3") (pin "P$1") (pinfunction "P1_P$1") (pintype "bidirectional"))
      (node (ref "C1") (pin "-") (pinfunction "-_-") (pintype "passive"))
      (node (ref "C10") (pin "2") (pinfunction "2_2") (pintype "passive"))
      (node (ref "C11") (pin "2") (pinfunction "2_2") (pintype "passive"))
      (node (ref "C12") (pin "-") (pinfunction "-_-") (pintype "passive"))
      (node (ref "C13") (pin "-") (pinfunction "-_-") (pintype "passive"))
      (node (ref "C14") (pin "2") (pinfunction "2_2") (pintype "passive"))
      (node (ref "C15") (pin "-") (pinfunction "-_-") (pintype "passive"))
      (node (ref "C16") (pin "2") (pinfunction "2_2") (pintype "passive"))
      (node (ref "C18") (pin "2") (pinfunction "2_2") (pintype "passive"))
      (node (ref "C2") (pin "2") (pinfunction "2_2") (pintype "passive"))
      (node (ref "C20") (pin "-") (pinfunction "-_-") (pintype "passive"))
      (node (ref "C22") (pin "2") (pinfunction "2_2") (pintype "passive"))
      (node (ref "C25") (pin "-") (pinfunction "-_-") (pintype "passive"))
      (node (ref "C27") (pin "-") (pinfunction "-_-") (pintype "passive"))
      (node (ref "C28") (pin "-") (pinfunction "-_-") (pintype "passive"))
      (node (ref "C3") (pin "2") (pinfunction "2_2") (pintype "passive"))
      (node (ref "C4") (pin "2") (pinfunction "2_2") (pintype "passive"))
      (node (ref "C5") (pin "2") (pinfunction "2_2") (pintype "passive"))
      (node (ref "C6") (pin "2") (pinfunction "2_2") (pintype "passive"))
      (node (ref "C7") (pin "2") (pinfunction "2_2") (pintype "passive"))
      (node (ref "C8") (pin "2") (pinfunction "2_2") (pintype "passive"))
      (node (ref "C9") (pin "2") (pinfunction "2_2") (pintype "passive"))
      (node (ref "DCDC3.3V") (pin "2") (pinfunction "2_2") (pintype "passive"))
      (node (ref "DCDC5V") (pin "2") (pinfunction "2_2") (pintype "passive"))
      (node (ref "ETH1") (pin "P$1") (pinfunction "GND_1_P$1") (pintype "bidirectional"))
      (node (ref "ETH1") (pin "P$12") (pinfunction "GND_3_P$12") (pintype "bidirectional"))
      (node (ref "ETH1") (pin "P$2") (pinfunction "GND_2_P$2") (pintype "bidirectional"))
      (node (ref "G1") (pin "-") (pinfunction "-_-") (pintype "passive"))
      (node (ref "IC1") (pin "7") (pinfunction "GND_7") (pintype "power_in"))
      (node (ref "IC2") (pin "7") (pinfunction "GND_7") (pintype "power_in"))
      (node (ref "IC3") (pin "7") (pinfunction "GND_7") (pintype "power_in"))
      (node (ref "J102") (pin "P$1") (pinfunction "P$1_P$1") (pintype "bidirectional"))
      (node (ref "J102") (pin "P$2") (pinfunction "P$2_P$2") (pintype "bidirectional"))
      (node (ref "J102") (pin "P$3") (pinfunction "P$3_P$3") (pintype "bidirectional"))
      (node (ref "J104") (pin "P$1") (pinfunction "P$1_P$1") (pintype "bidirectional"))
      (node (ref "J104") (pin "P$2") (pinfunction "P$2_P$2") (pintype "bidirectional"))
      (node (ref "J104") (pin "P$3") (pinfunction "P$3_P$3") (pintype "bidirectional"))
      (node (ref "J124") (pin "P$1") (pinfunction "P$1_P$1") (pintype "bidirectional"))
      (node (ref "J124") (pin "P$2") (pinfunction "P$2_P$2") (pintype "bidirectional"))
      (node (ref "J124") (pin "P$3") (pinfunction "P$3_P$3") (pintype "bidirectional"))
      (node (ref "J151") (pin "P$1") (pinfunction "P$1_P$1") (pintype "bidirectional"))
      (node (ref "J151") (pin "P$2") (pinfunction "P$2_P$2") (pintype "bidirectional"))
      (node (ref "J151") (pin "P$3") (pinfunction "P$3_P$3") (pintype "bidirectional"))
      (node (ref "J153") (pin "P$1") (pinfunction "P$1_P$1") (pintype "bidirectional"))
      (node (ref "J153") (pin "P$2") (pinfunction "P$2_P$2") (pintype "bidirectional"))
      (node (ref "J153") (pin "P$3") (pinfunction "P$3_P$3") (pintype "bidirectional"))
      (node (ref "J5") (pin "2") (pinfunction "2_2") (pintype "passive"))
      (node (ref "J5") (pin "3") (pinfunction "3_3") (pintype "passive"))
      (node (ref "J7") (pin "P$1") (pinfunction "P$1_P$1") (pintype "bidirectional"))
      (node (ref "J7") (pin "P$2") (pinfunction "P$2_P$2") (pintype "bidirectional"))
      (node (ref "J70") (pin "P$1") (pinfunction "P$1_P$1") (pintype "bidirectional"))
      (node (ref "J70") (pin "P$2") (pinfunction "P$2_P$2") (pintype "bidirectional"))
      (node (ref "J72") (pin "P$1") (pinfunction "P$1_P$1") (pintype "bidirectional"))
      (node (ref "J72") (pin "P$2") (pinfunction "P$2_P$2") (pintype "bidirectional"))
      (node (ref "J74") (pin "P$1") (pinfunction "P$1_P$1") (pintype "bidirectional"))
      (node (ref "J74") (pin "P$2") (pinfunction "P$2_P$2") (pintype "bidirectional"))
      (node (ref "J76") (pin "P$1") (pinfunction "P$1_P$1") (pintype "bidirectional"))
      (node (ref "J76") (pin "P$2") (pinfunction "P$2_P$2") (pintype "bidirectional"))
      (node (ref "JP2") (pin "2") (pinfunction "2_2") (pintype "passive"))
      (node (ref "JP3") (pin "2") (pinfunction "2_2") (pintype "passive"))
      (node (ref "L1") (pin "P$20") (pinfunction "GND_1_P$20") (pintype "bidirectional"))
      (node (ref "L1") (pin "P$22") (pinfunction "GND_2_P$22") (pintype "bidirectional"))
      (node (ref "L1") (pin "P$60") (pinfunction "GND_3_P$60") (pintype "bidirectional"))
      (node (ref "L1") (pin "P$62") (pinfunction "GND_4_P$62") (pintype "bidirectional"))
      (node (ref "P1") (pin "2") (pinfunction "2_2") (pintype "bidirectional"))
      (node (ref "POWER") (pin "1") (pinfunction "1_1") (pintype "passive"))
      (node (ref "R3") (pin "1") (pinfunction "1_1") (pintype "passive"))
      (node (ref "R32") (pin "2") (pinfunction "2_2") (pintype "passive"))
      (node (ref "R41") (pin "2") (pinfunction "2_2") (pintype "passive"))
      (node (ref "R43") (pin "2") (pinfunction "2_2") (pintype "passive"))
      (node (ref "R7") (pin "1") (pinfunction "1_1") (pintype "passive"))
      (node (ref "S1") (pin "P$1") (pinfunction "P1_P$1") (pintype "bidirectional"))
      (node (ref "S129") (pin "P$1") (pinfunction "P$1_P$1") (pintype "bidirectional"))
      (node (ref "S129") (pin "P$2") (pinfunction "P$2_P$2") (pintype "bidirectional"))
      (node (ref "S129") (pin "P$3") (pinfunction "P$3_P$3") (pintype "bidirectional"))
      (node (ref "S129") (pin "P$4") (pinfunction "P$4_P$4") (pintype "bidirectional"))
      (node (ref "S129") (pin "P$5") (pinfunction "P$5_P$5") (pintype "bidirectional"))
      (node (ref "S137") (pin "P$1") (pinfunction "P$1_P$1") (pintype "bidirectional"))
      (node (ref "S137") (pin "P$2") (pinfunction "P$2_P$2") (pintype "bidirectional"))
      (node (ref "S137") (pin "P$3") (pinfunction "P$3_P$3") (pintype "bidirectional"))
      (node (ref "S137") (pin "P$4") (pinfunction "P$4_P$4") (pintype "bidirectional"))
      (node (ref "S137") (pin "P$5") (pinfunction "P$5_P$5") (pintype "bidirectional"))
      (node (ref "S159") (pin "P$1") (pinfunction "P1_P$1") (pintype "bidirectional"))
      (node (ref "S20") (pin "P$1") (pinfunction "P$1_P$1") (pintype "bidirectional"))
      (node (ref "S20") (pin "P$10") (pinfunction "P$10_P$10") (pintype "bidirectional"))
      (node (ref "S20") (pin "P$2") (pinfunction "P$2_P$2") (pintype "bidirectional"))
      (node (ref "S20") (pin "P$3") (pinfunction "P$3_P$3") (pintype "bidirectional"))
      (node (ref "S20") (pin "P$4") (pinfunction "P$4_P$4") (pintype "bidirectional"))
      (node (ref "S20") (pin "P$5") (pinfunction "P$5_P$5") (pintype "bidirectional"))
      (node (ref "S20") (pin "P$6") (pinfunction "P$6_P$6") (pintype "bidirectional"))
      (node (ref "S20") (pin "P$7") (pinfunction "P$7_P$7") (pintype "bidirectional"))
      (node (ref "S20") (pin "P$8") (pinfunction "P$8_P$8") (pintype "bidirectional"))
      (node (ref "S20") (pin "P$9") (pinfunction "P$9_P$9") (pintype "bidirectional"))
      (node (ref "S24") (pin "P$1") (pinfunction "P$1_P$1") (pintype "bidirectional"))
      (node (ref "S24") (pin "P$10") (pinfunction "P$10_P$10") (pintype "bidirectional"))
      (node (ref "S24") (pin "P$2") (pinfunction "P$2_P$2") (pintype "bidirectional"))
      (node (ref "S24") (pin "P$3") (pinfunction "P$3_P$3") (pintype "bidirectional"))
      (node (ref "S24") (pin "P$4") (pinfunction "P$4_P$4") (pintype "bidirectional"))
      (node (ref "S24") (pin "P$5") (pinfunction "P$5_P$5") (pintype "bidirectional"))
      (node (ref "S24") (pin "P$6") (pinfunction "P$6_P$6") (pintype "bidirectional"))
      (node (ref "S24") (pin "P$7") (pinfunction "P$7_P$7") (pintype "bidirectional"))
      (node (ref "S24") (pin "P$8") (pinfunction "P$8_P$8") (pintype "bidirectional"))
      (node (ref "S24") (pin "P$9") (pinfunction "P$9_P$9") (pintype "bidirectional"))
      (node (ref "SV11") (pin "1") (pinfunction "1_1") (pintype "passive"))
      (node (ref "SV12") (pin "1") (pinfunction "1_1") (pintype "passive"))
      (node (ref "SV13") (pin "2") (pinfunction "2_2") (pintype "passive"))
      (node (ref "SV14") (pin "10") (pinfunction "10_10") (pintype "passive"))
      (node (ref "SV14") (pin "12") (pinfunction "12_12") (pintype "passive"))
      (node (ref "SV14") (pin "4") (pinfunction "4_4") (pintype "passive"))
      (node (ref "SV14") (pin "8") (pinfunction "8_8") (pintype "passive"))
      (node (ref "SV15") (pin "1") (pinfunction "1_1") (pintype "passive"))
      (node (ref "SV2") (pin "13") (pinfunction "13_13") (pintype "passive"))
      (node (ref "SV2") (pin "14") (pinfunction "14_14") (pintype "passive"))
      (node (ref "SV2") (pin "19") (pinfunction "19_19") (pintype "passive"))
      (node (ref "SV2") (pin "20") (pinfunction "20_20") (pintype "passive"))
      (node (ref "SV2") (pin "29") (pinfunction "29_29") (pintype "passive"))
      (node (ref "SV2") (pin "30") (pinfunction "30_30") (pintype "passive"))
      (node (ref "SV2") (pin "33") (pinfunction "33_33") (pintype "passive"))
      (node (ref "SV2") (pin "34") (pinfunction "34_34") (pintype "passive"))
      (node (ref "SV2") (pin "5") (pinfunction "5_5") (pintype "passive"))
      (node (ref "SV2") (pin "6") (pinfunction "6_6") (pintype "passive"))
      (node (ref "SV4") (pin "10") (pinfunction "10_10") (pintype "passive"))
      (node (ref "SV4") (pin "25") (pinfunction "25_25") (pintype "passive"))
      (node (ref "SV4") (pin "26") (pinfunction "26_26") (pintype "passive"))
      (node (ref "SV4") (pin "39") (pinfunction "39_39") (pintype "passive"))
      (node (ref "SV4") (pin "40") (pinfunction "40_40") (pintype "passive"))
      (node (ref "SV4") (pin "9") (pinfunction "9_9") (pintype "passive"))
      (node (ref "SV6") (pin "3") (pinfunction "3_3") (pintype "passive"))
      (node (ref "SV6") (pin "4") (pinfunction "4_4") (pintype "passive"))
      (node (ref "T1") (pin "3") (pinfunction "E_3") (pintype "passive"))
      (node (ref "T2") (pin "3") (pinfunction "E_3") (pintype "passive"))
      (node (ref "TRIMPOT1") (pin "5") (pinfunction "5_5") (pintype "passive"))
      (node (ref "TRIMPOT1") (pin "6") (pinfunction "6_6") (pintype "passive"))
      (node (ref "TRIMPOT2") (pin "5") (pinfunction "5_5") (pintype "passive"))
      (node (ref "TRIMPOT2") (pin "6") (pinfunction "6_6") (pintype "passive"))
      (node (ref "U$1") (pin "2") (pinfunction "P2_GND_2") (pintype "bidirectional"))
      (node (ref "U1") (pin "11") (pinfunction "SENSE_11") (pintype "bidirectional"))
      (node (ref "U1") (pin "12") (pinfunction "GND_12") (pintype "bidirectional"))
      (node (ref "U1") (pin "13") (pinfunction "GND_13") (pintype "bidirectional"))
      (node (ref "U1") (pin "4") (pinfunction "GND_4") (pintype "bidirectional"))
      (node (ref "U1") (pin "5") (pinfunction "GND_5") (pintype "bidirectional"))
      (node (ref "U2") (pin "P$15") (pinfunction "GND_P$15") (pintype "bidirectional"))
      (node (ref "U2") (pin "P$16") (pinfunction "PMODE_P$16") (pintype "bidirectional"))
      (node (ref "U2") (pin "P$17") (pinfunction "GND_PAD_P$17") (pintype "bidirectional"))
      (node (ref "U2") (pin "P$7") (pinfunction "IMODE_P$7") (pintype "bidirectional"))
      (node (ref "U2") (pin "P$9") (pinfunction "PGND_P$9") (pintype "bidirectional"))
      (node (ref "U3") (pin "4") (pinfunction "P4_GND_4") (pintype "bidirectional"))
      (node (ref "U4") (pin "P$15") (pinfunction "GND_P$15") (pintype "bidirectional"))
      (node (ref "U4") (pin "P$16") (pinfunction "PMODE_P$16") (pintype "bidirectional"))
      (node (ref "U4") (pin "P$17") (pinfunction "GND_PAD_P$17") (pintype "bidirectional"))
      (node (ref "U4") (pin "P$7") (pinfunction "IMODE_P$7") (pintype "bidirectional"))
      (node (ref "U4") (pin "P$9") (pinfunction "PGND_P$9") (pintype "bidirectional"))
      (node (ref "U5") (pin "11") (pinfunction "SENSE_11") (pintype "bidirectional"))
      (node (ref "U5") (pin "12") (pinfunction "GND_12") (pintype "bidirectional"))
      (node (ref "U5") (pin "13") (pinfunction "GND_13") (pintype "bidirectional"))
      (node (ref "U5") (pin "4") (pinfunction "GND_4") (pintype "bidirectional"))
      (node (ref "U5") (pin "5") (pinfunction "GND_5") (pintype "bidirectional"))
      (node (ref "U6") (pin "P$4") (pinfunction "V-_P$4") (pintype "bidirectional"))
      (node (ref "U7") (pin "4") (pinfunction "GND_4") (pintype "bidirectional"))
      (node (ref "U8") (pin "12") (pinfunction "VSS2_12") (pintype "bidirectional"))
      (node (ref "U8") (pin "2") (pinfunction "VSS_2") (pintype "bidirectional"))
      (node (ref "U8") (pin "23") (pinfunction "VSSA/VREFLO_23") (pintype "bidirectional"))
      (node (ref "U8") (pin "3") (pinfunction "/VREGENZ_3") (pintype "bidirectional"))
    )
    (net (code "51") (name "GPIO0") (class "Default")
      (node (ref "J11") (pin "P$1") (pinfunction "P$1_P$1") (pintype "bidirectional"))
      (node (ref "J11") (pin "P$2") (pinfunction "P$2_P$2") (pintype "bidirectional"))
      (node (ref "J122") (pin "P$1") (pinfunction "P$1_P$1") (pintype "bidirectional"))
      (node (ref "J122") (pin "P$2") (pinfunction "P$2_P$2") (pintype "bidirectional"))
      (node (ref "J122") (pin "P$3") (pinfunction "P$3_P$3") (pintype "bidirectional"))
      (node (ref "L1") (pin "P$40") (pinfunction "GPIO0/EPWM1A_P$40") (pintype "bidirectional"))
    )
    (net (code "52") (name "GPIO1") (class "Default")
      (node (ref "J121") (pin "P$1") (pinfunction "P$1_P$1") (pintype "bidirectional"))
      (node (ref "J121") (pin "P$2") (pinfunction "P$2_P$2") (pintype "bidirectional"))
      (node (ref "J121") (pin "P$3") (pinfunction "P$3_P$3") (pintype "bidirectional"))
      (node (ref "L1") (pin "P$39") (pinfunction "GPIO1/EPWM1B_P$39") (pintype "bidirectional"))
      (node (ref "SV13") (pin "5") (pinfunction "5_5") (pintype "passive"))
    )
    (net (code "53") (name "GPIO2") (class "Default")
      (node (ref "J120") (pin "P$1") (pinfunction "P$1_P$1") (pintype "bidirectional"))
      (node (ref "J120") (pin "P$2") (pinfunction "P$2_P$2") (pintype "bidirectional"))
      (node (ref "J120") (pin "P$3") (pinfunction "P$3_P$3") (pintype "bidirectional"))
      (node (ref "J198") (pin "P$1") (pinfunction "P$1_P$1") (pintype "bidirectional"))
      (node (ref "J198") (pin "P$2") (pinfunction "P$2_P$2") (pintype "bidirectional"))
      (node (ref "L1") (pin "P$38") (pinfunction "GPIO2/EPWM2A_P$38") (pintype "bidirectional"))
    )
    (net (code "54") (name "GPIO3") (class "Default")
      (node (ref "J119") (pin "P$1") (pinfunction "P$1_P$1") (pintype "bidirectional"))
      (node (ref "J119") (pin "P$2") (pinfunction "P$2_P$2") (pintype "bidirectional"))
      (node (ref "J119") (pin "P$3") (pinfunction "P$3_P$3") (pintype "bidirectional"))
      (node (ref "J199") (pin "P$1") (pinfunction "P$1_P$1") (pintype "bidirectional"))
      (node (ref "J199") (pin "P$2") (pinfunction "P$2_P$2") (pintype "bidirectional"))
      (node (ref "L1") (pin "P$37") (pinfunction "GPIO3/EPWM2B_P$37") (pintype "bidirectional"))
    )
    (net (code "55") (name "GPIO4") (class "Default")
      (node (ref "J118") (pin "P$1") (pinfunction "P$1_P$1") (pintype "bidirectional"))
      (node (ref "J118") (pin "P$2") (pinfunction "P$2_P$2") (pintype "bidirectional"))
      (node (ref "J118") (pin "P$3") (pinfunction "P$3_P$3") (pintype "bidirectional"))
      (node (ref "J71") (pin "P$1") (pinfunction "P$1_P$1") (pintype "bidirectional"))
      (node (ref "J71") (pin "P$2") (pinfunction "P$2_P$2") (pintype "bidirectional"))
      (node (ref "L1") (pin "P$36") (pinfunction "GPIO4/EPWM3A_P$36") (pintype "bidirectional"))
    )
    (net (code "56") (name "GPIO5") (class "Default")
      (node (ref "J117") (pin "P$1") (pinfunction "P$1_P$1") (pintype "bidirectional"))
      (node (ref "J117") (pin "P$2") (pinfunction "P$2_P$2") (pintype "bidirectional"))
      (node (ref "J117") (pin "P$3") (pinfunction "P$3_P$3") (pintype "bidirectional"))
      (node (ref "J73") (pin "P$1") (pinfunction "P$1_P$1") (pintype "bidirectional"))
      (node (ref "J73") (pin "P$2") (pinfunction "P$2_P$2") (pintype "bidirectional"))
      (node (ref "L1") (pin "P$35") (pinfunction "GPIO5/EPWM3B_P$35") (pintype "bidirectional"))
    )
    (net (code "57") (name "GPIO6") (class "Default")
      (node (ref "J133") (pin "P$1") (pinfunction "P$1_P$1") (pintype "bidirectional"))
      (node (ref "J133") (pin "P$2") (pinfunction "P$2_P$2") (pintype "bidirectional"))
      (node (ref "J133") (pin "P$3") (pinfunction "P$3_P$3") (pintype "bidirectional"))
      (node (ref "J75") (pin "P$1") (pinfunction "P$1_P$1") (pintype "bidirectional"))
      (node (ref "J75") (pin "P$2") (pinfunction "P$2_P$2") (pintype "bidirectional"))
      (node (ref "L1") (pin "P$80") (pinfunction "GPIO6/EPWM4A_P$80") (pintype "bidirectional"))
    )
    (net (code "58") (name "GPIO7") (class "Default")
      (node (ref "J134") (pin "P$1") (pinfunction "P$1_P$1") (pintype "bidirectional"))
      (node (ref "J134") (pin "P$2") (pinfunction "P$2_P$2") (pintype "bidirectional"))
      (node (ref "J134") (pin "P$3") (pinfunction "P$3_P$3") (pintype "bidirectional"))
      (node (ref "J77") (pin "P$1") (pinfunction "P$1_P$1") (pintype "bidirectional"))
      (node (ref "J77") (pin "P$2") (pinfunction "P$2_P$2") (pintype "bidirectional"))
      (node (ref "L1") (pin "P$79") (pinfunction "GPIO7/EPWM4B_P$79") (pintype "bidirectional"))
    )
    (net (code "59") (name "GPIO8") (class "Default")
      (node (ref "J135") (pin "P$1") (pinfunction "P$1_P$1") (pintype "bidirectional"))
      (node (ref "J135") (pin "P$2") (pinfunction "P$2_P$2") (pintype "bidirectional"))
      (node (ref "J135") (pin "P$3") (pinfunction "P$3_P$3") (pintype "bidirectional"))
      (node (ref "L1") (pin "P$78") (pinfunction "GPIO8/EPWM5A_P$78") (pintype "bidirectional"))
      (node (ref "SV11") (pin "5") (pinfunction "5_5") (pintype "passive"))
    )
    (net (code "60") (name "GPIO9") (class "Default")
      (node (ref "J136") (pin "P$1") (pinfunction "P$1_P$1") (pintype "bidirectional"))
      (node (ref "J136") (pin "P$2") (pinfunction "P$2_P$2") (pintype "bidirectional"))
      (node (ref "J136") (pin "P$3") (pinfunction "P$3_P$3") (pintype "bidirectional"))
      (node (ref "J37") (pin "P$2") (pinfunction "P$2_P$2") (pintype "bidirectional"))
      (node (ref "L1") (pin "P$77") (pinfunction "GPIO9/EPWM5B_P$77") (pintype "bidirectional"))
    )
    (net (code "61") (name "GPIO10") (class "Default")
      (node (ref "J137") (pin "P$1") (pinfunction "P$1_P$1") (pintype "bidirectional"))
      (node (ref "J137") (pin "P$2") (pinfunction "P$2_P$2") (pintype "bidirectional"))
      (node (ref "J137") (pin "P$3") (pinfunction "P$3_P$3") (pintype "bidirectional"))
      (node (ref "J84") (pin "P$1") (pinfunction "P$1_P$1") (pintype "bidirectional"))
      (node (ref "J84") (pin "P$2") (pinfunction "P$2_P$2") (pintype "bidirectional"))
      (node (ref "L1") (pin "P$76") (pinfunction "GPIO10/EPWM6A_P$76") (pintype "bidirectional"))
    )
    (net (code "62") (name "GPIO11") (class "Default")
      (node (ref "J138") (pin "P$1") (pinfunction "P$1_P$1") (pintype "bidirectional"))
      (node (ref "J138") (pin "P$2") (pinfunction "P$2_P$2") (pintype "bidirectional"))
      (node (ref "J138") (pin "P$3") (pinfunction "P$3_P$3") (pintype "bidirectional"))
      (node (ref "J86") (pin "P$1") (pinfunction "P$1_P$1") (pintype "bidirectional"))
      (node (ref "J86") (pin "P$2") (pinfunction "P$2_P$2") (pintype "bidirectional"))
      (node (ref "L1") (pin "P$75") (pinfunction "GPIO11/EPWM6B_P$75") (pintype "bidirectional"))
    )
    (net (code "63") (name "GPIO14") (class "Default")
      (node (ref "J139") (pin "P$1") (pinfunction "P$1_P$1") (pintype "bidirectional"))
      (node (ref "J139") (pin "P$2") (pinfunction "P$2_P$2") (pintype "bidirectional"))
      (node (ref "J139") (pin "P$3") (pinfunction "P$3_P$3") (pintype "bidirectional"))
      (node (ref "J201") (pin "P$1") (pinfunction "P$1_P$1") (pintype "bidirectional"))
      (node (ref "J201") (pin "P$2") (pinfunction "P$2_P$2") (pintype "bidirectional"))
      (node (ref "L1") (pin "P$74") (pinfunction "GPIO14_P$74") (pintype "bidirectional"))
    )
    (net (code "64") (name "GPIO15") (class "Default")
      (node (ref "J140") (pin "P$1") (pinfunction "P$1_P$1") (pintype "bidirectional"))
      (node (ref "J140") (pin "P$2") (pinfunction "P$2_P$2") (pintype "bidirectional"))
      (node (ref "J140") (pin "P$3") (pinfunction "P$3_P$3") (pintype "bidirectional"))
      (node (ref "J202") (pin "P$1") (pinfunction "P$1_P$1") (pintype "bidirectional"))
      (node (ref "J202") (pin "P$2") (pinfunction "P$2_P$2") (pintype "bidirectional"))
      (node (ref "L1") (pin "P$73") (pinfunction "GPIO15_P$73") (pintype "bidirectional"))
    )
    (net (code "65") (name "GPIO16") (class "Default")
      (node (ref "J115") (pin "P$1") (pinfunction "P$1_P$1") (pintype "bidirectional"))
      (node (ref "J115") (pin "P$2") (pinfunction "P$2_P$2") (pintype "bidirectional"))
      (node (ref "J115") (pin "P$3") (pinfunction "P$3_P$3") (pintype "bidirectional"))
      (node (ref "J251") (pin "P$1") (pinfunction "P$1_P$1") (pintype "bidirectional"))
      (node (ref "J251") (pin "P$2") (pinfunction "P$2_P$2") (pintype "bidirectional"))
      (node (ref "L1") (pin "P$33") (pinfunction "GPIO16_P$33") (pintype "bidirectional"))
    )
    (net (code "66") (name "GPIO18") (class "Default")
      (node (ref "J16") (pin "P$1") (pinfunction "P$1_P$1") (pintype "bidirectional"))
      (node (ref "J16") (pin "P$2") (pinfunction "P$2_P$2") (pintype "bidirectional"))
      (node (ref "J16") (pin "P$3") (pinfunction "P$3_P$3") (pintype "bidirectional"))
      (node (ref "L1") (pin "P$4") (pinfunction "GPIO18/SCITXDB_P$4") (pintype "bidirectional"))
      (node (ref "U7") (pin "6") (pinfunction "SCK_6") (pintype "bidirectional"))
    )
    (net (code "67") (name "GPIO19") (class "Default")
      (node (ref "J15") (pin "P$1") (pinfunction "P$1_P$1") (pintype "bidirectional"))
      (node (ref "J15") (pin "P$2") (pinfunction "P$2_P$2") (pintype "bidirectional"))
      (node (ref "J15") (pin "P$3") (pinfunction "P$3_P$3") (pintype "bidirectional"))
      (node (ref "L1") (pin "P$3") (pinfunction "GPIO19/SCIRXDB_P$3") (pintype "bidirectional"))
      (node (ref "U7") (pin "1") (pinfunction "~{CS}_1") (pintype "bidirectional"))
    )
    (net (code "68") (name "GPIO22") (class "Default")
      (node (ref "IC1") (pin "1") (pinfunction "I_1") (pintype "input"))
      (node (ref "J20") (pin "P$1") (pinfunction "P$1_P$1") (pintype "bidirectional"))
      (node (ref "J20") (pin "P$2") (pinfunction "P$2_P$2") (pintype "bidirectional"))
      (node (ref "J20") (pin "P$3") (pinfunction "P$3_P$3") (pintype "bidirectional"))
      (node (ref "L1") (pin "P$8") (pinfunction "GPIO22_P$8") (pintype "bidirectional"))
    )
    (net (code "69") (name "GPIO24") (class "Default")
      (node (ref "J116") (pin "P$1") (pinfunction "P$1_P$1") (pintype "bidirectional"))
      (node (ref "J116") (pin "P$2") (pinfunction "P$2_P$2") (pintype "bidirectional"))
      (node (ref "J116") (pin "P$3") (pinfunction "P$3_P$3") (pintype "bidirectional"))
      (node (ref "J9") (pin "P$1") (pinfunction "P$1_P$1") (pintype "bidirectional"))
      (node (ref "J9") (pin "P$2") (pinfunction "P$2_P$2") (pintype "bidirectional"))
      (node (ref "L1") (pin "P$34") (pinfunction "GPIO24_P$34") (pintype "bidirectional"))
    )
    (net (code "70") (name "GPIO25") (class "Default")
      (node (ref "IC2") (pin "3") (pinfunction "I_3") (pintype "input"))
      (node (ref "J162") (pin "P$1") (pinfunction "P$1_P$1") (pintype "bidirectional"))
      (node (ref "J162") (pin "P$2") (pinfunction "P$2_P$2") (pintype "bidirectional"))
      (node (ref "J162") (pin "P$3") (pinfunction "P$3_P$3") (pintype "bidirectional"))
      (node (ref "L1") (pin "P$51") (pinfunction "GPIO25_P$51") (pintype "bidirectional"))
    )
    (net (code "71") (name "GPIO26") (class "Default")
      (node (ref "IC2") (pin "5") (pinfunction "I_5") (pintype "input"))
      (node (ref "J160") (pin "P$1") (pinfunction "P$1_P$1") (pintype "bidirectional"))
      (node (ref "J160") (pin "P$2") (pinfunction "P$2_P$2") (pintype "bidirectional"))
      (node (ref "J160") (pin "P$3") (pinfunction "P$3_P$3") (pintype "bidirectional"))
      (node (ref "L1") (pin "P$53") (pinfunction "GPIO26_P$53") (pintype "bidirectional"))
    )
    (net (code "72") (name "GPIO27") (class "Default")
      (node (ref "IC2") (pin "9") (pinfunction "I_9") (pintype "input"))
      (node (ref "J161") (pin "P$1") (pinfunction "P$1_P$1") (pintype "bidirectional"))
      (node (ref "J161") (pin "P$2") (pinfunction "P$2_P$2") (pintype "bidirectional"))
      (node (ref "J161") (pin "P$3") (pinfunction "P$3_P$3") (pintype "bidirectional"))
      (node (ref "L1") (pin "P$52") (pinfunction "GPIO27_P$52") (pintype "bidirectional"))
    )
    (net (code "73") (name "GPIO29") (class "Default")
      (node (ref "J29") (pin "P$1") (pinfunction "P$1_P$1") (pintype "bidirectional"))
      (node (ref "J29") (pin "P$2") (pinfunction "P$2_P$2") (pintype "bidirectional"))
      (node (ref "J29") (pin "P$3") (pinfunction "P$3_P$3") (pintype "bidirectional"))
      (node (ref "J85") (pin "P$1") (pinfunction "P$1_P$1") (pintype "bidirectional"))
      (node (ref "J85") (pin "P$2") (pinfunction "P$2_P$2") (pintype "bidirectional"))
      (node (ref "L1") (pin "P$11") (pinfunction "GPIO29_P$11") (pintype "bidirectional"))
    )
    (net (code "74") (name "GPIO32") (class "Default")
      (node (ref "J14") (pin "P$1") (pinfunction "P$1_P$1") (pintype "bidirectional"))
      (node (ref "J14") (pin "P$2") (pinfunction "P$2_P$2") (pintype "bidirectional"))
      (node (ref "J14") (pin "P$3") (pinfunction "P$3_P$3") (pintype "bidirectional"))
      (node (ref "J87") (pin "P$1") (pinfunction "P$1_P$1") (pintype "bidirectional"))
      (node (ref "J87") (pin "P$2") (pinfunction "P$2_P$2") (pintype "bidirectional"))
      (node (ref "L1") (pin "P$2") (pinfunction "GPIO32_P$2") (pintype "bidirectional"))
    )
    (net (code "75") (name "GPIO40") (class "Default")
      (node (ref "J163") (pin "P$1") (pinfunction "P$1_P$1") (pintype "bidirectional"))
      (node (ref "J163") (pin "P$2") (pinfunction "P$2_P$2") (pintype "bidirectional"))
      (node (ref "J163") (pin "P$3") (pinfunction "P$3_P$3") (pintype "bidirectional"))
      (node (ref "J208") (pin "P$1") (pinfunction "P$1_P$1") (pintype "bidirectional"))
      (node (ref "J208") (pin "P$2") (pinfunction "P$2_P$2") (pintype "bidirectional"))
      (node (ref "L1") (pin "P$50") (pinfunction "GPIO40/SDAB_P$50") (pintype "bidirectional"))
      (node (ref "R9") (pin "2") (pinfunction "2_2") (pintype "passive"))
    )
    (net (code "76") (name "GPIO41") (class "Default")
      (node (ref "J164") (pin "P$1") (pinfunction "P$1_P$1") (pintype "bidirectional"))
      (node (ref "J164") (pin "P$2") (pinfunction "P$2_P$2") (pintype "bidirectional"))
      (node (ref "J164") (pin "P$3") (pinfunction "P$3_P$3") (pintype "bidirectional"))
      (node (ref "J209") (pin "P$1") (pinfunction "P$1_P$1") (pintype "bidirectional"))
      (node (ref "J209") (pin "P$2") (pinfunction "P$2_P$2") (pintype "bidirectional"))
      (node (ref "L1") (pin "P$49") (pinfunction "GPIO41/SCLB_P$49") (pintype "bidirectional"))
      (node (ref "R10") (pin "2") (pinfunction "2_2") (pintype "passive"))
    )
    (net (code "77") (name "GPIO52") (class "Default")
      (node (ref "J165") (pin "P$1") (pinfunction "P$1_P$1") (pintype "bidirectional"))
      (node (ref "J165") (pin "P$2") (pinfunction "P$2_P$2") (pintype "bidirectional"))
      (node (ref "J165") (pin "P$3") (pinfunction "P$3_P$3") (pintype "bidirectional"))
      (node (ref "L1") (pin "P$48") (pinfunction "GPIO52_P$48") (pintype "bidirectional"))
    )
    (net (code "78") (name "GPIO56") (class "Default")
      (node (ref "J169") (pin "P$1") (pinfunction "P$1_P$1") (pintype "bidirectional"))
      (node (ref "J169") (pin "P$2") (pinfunction "P$2_P$2") (pintype "bidirectional"))
      (node (ref "J169") (pin "P$3") (pinfunction "P$3_P$3") (pintype "bidirectional"))
      (node (ref "L1") (pin "P$44") (pinfunction "GPIO56/SCITXDC_P$44") (pintype "bidirectional"))
      (node (ref "SV13") (pin "8") (pinfunction "8_8") (pintype "passive"))
    )
    (net (code "79") (name "GPIO58") (class "Default")
      (node (ref "J33") (pin "P$1") (pinfunction "P$1_P$1") (pintype "bidirectional"))
      (node (ref "J33") (pin "P$2") (pinfunction "P$2_P$2") (pintype "bidirectional"))
      (node (ref "J33") (pin "P$3") (pinfunction "P$3_P$3") (pintype "bidirectional"))
      (node (ref "L1") (pin "P$15") (pinfunction "GPIO58/SPISIMOA_P$15") (pintype "bidirectional"))
      (node (ref "U7") (pin "5") (pinfunction "SI_5") (pintype "bidirectional"))
    )
    (net (code "80") (name "GPIO59") (class "Default")
      (node (ref "J32") (pin "P$1") (pinfunction "P$1_P$1") (pintype "bidirectional"))
      (node (ref "J32") (pin "P$2") (pinfunction "P$2_P$2") (pintype "bidirectional"))
      (node (ref "J32") (pin "P$3") (pinfunction "P$3_P$3") (pintype "bidirectional"))
      (node (ref "L1") (pin "P$14") (pinfunction "GPIO59/SPISOMIA_P$14") (pintype "bidirectional"))
      (node (ref "U7") (pin "2") (pinfunction "SO_2") (pintype "bidirectional"))
    )
    (net (code "81") (name "GPIO60") (class "Default")
      (node (ref "IC2") (pin "11") (pinfunction "I_11") (pintype "input"))
      (node (ref "J19") (pin "P$1") (pinfunction "P$1_P$1") (pintype "bidirectional"))
      (node (ref "J19") (pin "P$2") (pinfunction "P$2_P$2") (pintype "bidirectional"))
      (node (ref "J19") (pin "P$3") (pinfunction "P$3_P$3") (pintype "bidirectional"))
      (node (ref "L1") (pin "P$7") (pinfunction "GPIO60/SPICLKA_P$7") (pintype "bidirectional"))
    )
    (net (code "82") (name "GPIO61") (class "Default")
      (node (ref "IC2") (pin "13") (pinfunction "I_13") (pintype "input"))
      (node (ref "J101") (pin "P$1") (pinfunction "P$1_P$1") (pintype "bidirectional"))
      (node (ref "J101") (pin "P$2") (pinfunction "P$2_P$2") (pintype "bidirectional"))
      (node (ref "J101") (pin "P$3") (pinfunction "P$3_P$3") (pintype "bidirectional"))
      (node (ref "L1") (pin "P$19") (pinfunction "GPIO61_P$19") (pintype "bidirectional"))
    )
    (net (code "83") (name "GPIO63") (class "Default")
      (node (ref "J158") (pin "P$1") (pinfunction "P$1_P$1") (pintype "bidirectional"))
      (node (ref "J158") (pin "P$2") (pinfunction "P$2_P$2") (pintype "bidirectional"))
      (node (ref "J158") (pin "P$3") (pinfunction "P$3_P$3") (pintype "bidirectional"))
      (node (ref "J204") (pin "P$1") (pinfunction "P$1_P$1") (pintype "bidirectional"))
      (node (ref "J204") (pin "P$2") (pinfunction "P$2_P$2") (pintype "bidirectional"))
      (node (ref "J36") (pin "P$2") (pinfunction "P$2_P$2") (pintype "bidirectional"))
      (node (ref "L1") (pin "P$55") (pinfunction "GPIO63/SPISIMOB_P$55") (pintype "bidirectional"))
    )
    (net (code "84") (name "GPIO64") (class "Default")
      (node (ref "J159") (pin "P$1") (pinfunction "P$1_P$1") (pintype "bidirectional"))
      (node (ref "J159") (pin "P$2") (pinfunction "P$2_P$2") (pintype "bidirectional"))
      (node (ref "J159") (pin "P$3") (pinfunction "P$3_P$3") (pintype "bidirectional"))
      (node (ref "J205") (pin "P$1") (pinfunction "P$1_P$1") (pintype "bidirectional"))
      (node (ref "J205") (pin "P$2") (pinfunction "P$2_P$2") (pintype "bidirectional"))
      (node (ref "J35") (pin "P$2") (pinfunction "P$2_P$2") (pintype "bidirectional"))
      (node (ref "L1") (pin "P$54") (pinfunction "GPIO64/SPISOMIB_P$54") (pintype "bidirectional"))
    )
    (net (code "85") (name "GPIO65") (class "Default")
      (node (ref "J166") (pin "P$1") (pinfunction "P$1_P$1") (pintype "bidirectional"))
      (node (ref "J166") (pin "P$2") (pinfunction "P$2_P$2") (pintype "bidirectional"))
      (node (ref "J166") (pin "P$3") (pinfunction "P$3_P$3") (pintype "bidirectional"))
      (node (ref "J206") (pin "P$1") (pinfunction "P$1_P$1") (pintype "bidirectional"))
      (node (ref "J206") (pin "P$2") (pinfunction "P$2_P$2") (pintype "bidirectional"))
      (node (ref "J38") (pin "P$2") (pinfunction "P$2_P$2") (pintype "bidirectional"))
      (node (ref "L1") (pin "P$47") (pinfunction "GPIO65/SPICLKB_P$47") (pintype "bidirectional"))
    )
    (net (code "86") (name "GPIO66") (class "Default")
      (node (ref "J154") (pin "P$1") (pinfunction "P$1_P$1") (pintype "bidirectional"))
      (node (ref "J154") (pin "P$2") (pinfunction "P$2_P$2") (pintype "bidirectional"))
      (node (ref "J154") (pin "P$3") (pinfunction "P$3_P$3") (pintype "bidirectional"))
      (node (ref "J207") (pin "P$1") (pinfunction "P$1_P$1") (pintype "bidirectional"))
      (node (ref "J207") (pin "P$2") (pinfunction "P$2_P$2") (pintype "bidirectional"))
      (node (ref "L1") (pin "P$59") (pinfunction "GPIO66_P$59") (pintype "bidirectional"))
    )
    (net (code "87") (name "GPIO67") (class "Default")
      (node (ref "J17") (pin "P$1") (pinfunction "P$1_P$1") (pintype "bidirectional"))
      (node (ref "J17") (pin "P$2") (pinfunction "P$2_P$2") (pintype "bidirectional"))
      (node (ref "J17") (pin "P$3") (pinfunction "P$3_P$3") (pintype "bidirectional"))
      (node (ref "L1") (pin "P$5") (pinfunction "GPIO67_P$5") (pintype "bidirectional"))
    )
    (net (code "88") (name "GPIO94") (class "Default")
      (node (ref "IC1") (pin "3") (pinfunction "I_3") (pintype "input"))
      (node (ref "J167") (pin "P$1") (pinfunction "P$1_P$1") (pintype "bidirectional"))
      (node (ref "J167") (pin "P$2") (pinfunction "P$2_P$2") (pintype "bidirectional"))
      (node (ref "J167") (pin "P$3") (pinfunction "P$3_P$3") (pintype "bidirectional"))
      (node (ref "L1") (pin "P$46") (pinfunction "GPIO94_P$46") (pintype "bidirectional"))
    )
    (net (code "89") (name "GPIO95") (class "Default")
      (node (ref "IC1") (pin "5") (pinfunction "I_5") (pintype "input"))
      (node (ref "J176") (pin "P$1") (pinfunction "P$1_P$1") (pintype "bidirectional"))
      (node (ref "J176") (pin "P$2") (pinfunction "P$2_P$2") (pintype "bidirectional"))
      (node (ref "J176") (pin "P$3") (pinfunction "P$3_P$3") (pintype "bidirectional"))
      (node (ref "L1") (pin "P$42") (pinfunction "GPIO95_P$42") (pintype "bidirectional"))
    )
    (net (code "90") (name "GPIO97") (class "Default")
      (node (ref "IC1") (pin "9") (pinfunction "I_9") (pintype "input"))
      (node (ref "J168") (pin "P$1") (pinfunction "P$1_P$1") (pintype "bidirectional"))
      (node (ref "J168") (pin "P$2") (pinfunction "P$2_P$2") (pintype "bidirectional"))
      (node (ref "J168") (pin "P$3") (pinfunction "P$3_P$3") (pintype "bidirectional"))
      (node (ref "L1") (pin "P$45") (pinfunction "GPIO97_P$45") (pintype "bidirectional"))
    )
    (net (code "91") (name "GPIO104") (class "Default")
      (node (ref "J28") (pin "P$1") (pinfunction "P$1_P$1") (pintype "bidirectional"))
      (node (ref "J28") (pin "P$2") (pinfunction "P$2_P$2") (pintype "bidirectional"))
      (node (ref "J28") (pin "P$3") (pinfunction "P$3_P$3") (pintype "bidirectional"))
      (node (ref "L1") (pin "P$10") (pinfunction "GPIO104/SDAA_P$10") (pintype "bidirectional"))
    )
    (net (code "92") (name "GPIO105") (class "Default")
      (node (ref "J21") (pin "P$1") (pinfunction "P$1_P$1") (pintype "bidirectional"))
      (node (ref "J21") (pin "P$2") (pinfunction "P$2_P$2") (pintype "bidirectional"))
      (node (ref "J21") (pin "P$3") (pinfunction "P$3_P$3") (pintype "bidirectional"))
      (node (ref "L1") (pin "P$9") (pinfunction "GPIO105/SCLA_P$9") (pintype "bidirectional"))
    )
    (net (code "93") (name "GPIO111") (class "Default")
      (node (ref "IC1") (pin "11") (pinfunction "I_11") (pintype "input"))
      (node (ref "J18") (pin "P$1") (pinfunction "P$1_P$1") (pintype "bidirectional"))
      (node (ref "J18") (pin "P$2") (pinfunction "P$2_P$2") (pintype "bidirectional"))
      (node (ref "J18") (pin "P$3") (pinfunction "P$3_P$3") (pintype "bidirectional"))
      (node (ref "L1") (pin "P$6") (pinfunction "GPIO111_P$6") (pintype "bidirectional"))
    )
    (net (code "94") (name "GPIO122") (class "Default")
      (node (ref "J66") (pin "P$1") (pinfunction "P$1_P$1") (pintype "bidirectional"))
      (node (ref "J66") (pin "P$2") (pinfunction "P$2_P$2") (pintype "bidirectional"))
      (node (ref "J99") (pin "P$1") (pinfunction "P$1_P$1") (pintype "bidirectional"))
      (node (ref "J99") (pin "P$2") (pinfunction "P$2_P$2") (pintype "bidirectional"))
      (node (ref "J99") (pin "P$3") (pinfunction "P$3_P$3") (pintype "bidirectional"))
      (node (ref "L1") (pin "P$17") (pinfunction "GPIO122_P$17") (pintype "bidirectional"))
    )
    (net (code "95") (name "GPIO123") (class "Default")
      (node (ref "J100") (pin "P$1") (pinfunction "P$1_P$1") (pintype "bidirectional"))
      (node (ref "J100") (pin "P$2") (pinfunction "P$2_P$2") (pintype "bidirectional"))
      (node (ref "J100") (pin "P$3") (pinfunction "P$3_P$3") (pintype "bidirectional"))
      (node (ref "J67") (pin "P$1") (pinfunction "P$1_P$1") (pintype "bidirectional"))
      (node (ref "J67") (pin "P$2") (pinfunction "P$2_P$2") (pintype "bidirectional"))
      (node (ref "L1") (pin "P$18") (pinfunction "GPIO123_P$18") (pintype "bidirectional"))
    )
    (net (code "96") (name "GPIO124") (class "Default")
      (node (ref "J31") (pin "P$1") (pinfunction "P$1_P$1") (pintype "bidirectional"))
      (node (ref "J31") (pin "P$2") (pinfunction "P$2_P$2") (pintype "bidirectional"))
      (node (ref "J31") (pin "P$3") (pinfunction "P$3_P$3") (pintype "bidirectional"))
      (node (ref "J68") (pin "P$1") (pinfunction "P$1_P$1") (pintype "bidirectional"))
      (node (ref "J68") (pin "P$2") (pinfunction "P$2_P$2") (pintype "bidirectional"))
      (node (ref "L1") (pin "P$13") (pinfunction "GPIO124_P$13") (pintype "bidirectional"))
    )
    (net (code "97") (name "GPIO125") (class "Default")
      (node (ref "J30") (pin "P$1") (pinfunction "P$1_P$1") (pintype "bidirectional"))
      (node (ref "J30") (pin "P$2") (pinfunction "P$2_P$2") (pintype "bidirectional"))
      (node (ref "J30") (pin "P$3") (pinfunction "P$3_P$3") (pintype "bidirectional"))
      (node (ref "J69") (pin "P$1") (pinfunction "P$1_P$1") (pintype "bidirectional"))
      (node (ref "J69") (pin "P$2") (pinfunction "P$2_P$2") (pintype "bidirectional"))
      (node (ref "L1") (pin "P$12") (pinfunction "GPIO125_P$12") (pintype "bidirectional"))
    )
    (net (code "98") (name "GPIO130") (class "Default")
      (node (ref "IC1") (pin "13") (pinfunction "I_13") (pintype "input"))
      (node (ref "J156") (pin "P$1") (pinfunction "P$1_P$1") (pintype "bidirectional"))
      (node (ref "J156") (pin "P$2") (pinfunction "P$2_P$2") (pintype "bidirectional"))
      (node (ref "J156") (pin "P$3") (pinfunction "P$3_P$3") (pintype "bidirectional"))
      (node (ref "L1") (pin "P$57") (pinfunction "GPIO130_P$57") (pintype "bidirectional"))
    )
    (net (code "99") (name "GPIO131") (class "Default")
      (node (ref "IC2") (pin "1") (pinfunction "I_1") (pintype "input"))
      (node (ref "J155") (pin "P$1") (pinfunction "P$1_P$1") (pintype "bidirectional"))
      (node (ref "J155") (pin "P$2") (pinfunction "P$2_P$2") (pintype "bidirectional"))
      (node (ref "J155") (pin "P$3") (pinfunction "P$3_P$3") (pintype "bidirectional"))
      (node (ref "L1") (pin "P$58") (pinfunction "GPIO131_P$58") (pintype "bidirectional"))
    )
    (net (code "100") (name "GPIO139") (class "Default")
      (node (ref "J170") (pin "P$1") (pinfunction "P$1_P$1") (pintype "bidirectional"))
      (node (ref "J170") (pin "P$2") (pinfunction "P$2_P$2") (pintype "bidirectional"))
      (node (ref "J170") (pin "P$3") (pinfunction "P$3_P$3") (pintype "bidirectional"))
      (node (ref "L1") (pin "P$43") (pinfunction "GPIO139/SCIRXDC_P$43") (pintype "bidirectional"))
      (node (ref "SV13") (pin "1") (pinfunction "1_1") (pintype "passive"))
    )
    (net (code "101") (name "GPIO157") (class "Default")
      (node (ref "IC3") (pin "1") (pinfunction "I_1") (pintype "input"))
      (node (ref "J141") (pin "P$1") (pinfunction "P$1_P$1") (pintype "bidirectional"))
      (node (ref "J141") (pin "P$2") (pinfunction "P$2_P$2") (pintype "bidirectional"))
      (node (ref "J141") (pin "P$3") (pinfunction "P$3_P$3") (pintype "bidirectional"))
      (node (ref "L1") (pin "P$72") (pinfunction "DAC3_P$72") (pintype "bidirectional"))
    )
    (net (code "102") (name "GPIO158") (class "Default")
      (node (ref "IC3") (pin "3") (pinfunction "I_3") (pintype "input"))
      (node (ref "J142") (pin "P$1") (pinfunction "P$1_P$1") (pintype "bidirectional"))
      (node (ref "J142") (pin "P$2") (pinfunction "P$2_P$2") (pintype "bidirectional"))
      (node (ref "J142") (pin "P$3") (pinfunction "P$3_P$3") (pintype "bidirectional"))
      (node (ref "L1") (pin "P$71") (pinfunction "DAC4_P$71") (pintype "bidirectional"))
    )
    (net (code "103") (name "GPIO159") (class "Default")
      (node (ref "IC3") (pin "5") (pinfunction "I_5") (pintype "input"))
      (node (ref "J114") (pin "P$1") (pinfunction "P$1_P$1") (pintype "bidirectional"))
      (node (ref "J114") (pin "P$2") (pinfunction "P$2_P$2") (pintype "bidirectional"))
      (node (ref "J114") (pin "P$3") (pinfunction "P$3_P$3") (pintype "bidirectional"))
      (node (ref "L1") (pin "P$32") (pinfunction "DAC1_P$32") (pintype "bidirectional"))
    )
    (net (code "104") (name "GPIO160") (class "Default")
      (node (ref "IC3") (pin "9") (pinfunction "I_9") (pintype "input"))
      (node (ref "J113") (pin "P$1") (pinfunction "P$1_P$1") (pintype "bidirectional"))
      (node (ref "J113") (pin "P$2") (pinfunction "P$2_P$2") (pintype "bidirectional"))
      (node (ref "J113") (pin "P$3") (pinfunction "P$3_P$3") (pintype "bidirectional"))
      (node (ref "L1") (pin "P$31") (pinfunction "DAC2_P$31") (pintype "bidirectional"))
    )
    (net (code "105") (name "MENABLE") (class "Default")
      (node (ref "S159") (pin "P$2") (pinfunction "P2_P$2") (pintype "bidirectional"))
      (node (ref "U2") (pin "P$3") (pinfunction "NSLEEP_P$3") (pintype "bidirectional"))
      (node (ref "U4") (pin "P$3") (pinfunction "NSLEEP_P$3") (pintype "bidirectional"))
    )
    (net (code "106") (name "MOTOR1+") (class "Default")
      (node (ref "SV3") (pin "1") (pinfunction "1_1") (pintype "passive"))
      (node (ref "SV3") (pin "3") (pinfunction "3_3") (pintype "passive"))
      (node (ref "SV3") (pin "5") (pinfunction "5_5") (pintype "passive"))
      (node (ref "U1") (pin "15") (pinfunction "OUTB_15") (pintype "bidirectional"))
    )
    (net (code "107") (name "MOTOR1-") (class "Default")
      (node (ref "SV3") (pin "2") (pinfunction "2_2") (pintype "passive"))
      (node (ref "SV3") (pin "4") (pinfunction "4_4") (pintype "passive"))
      (node (ref "SV3") (pin "6") (pinfunction "6_6") (pintype "passive"))
      (node (ref "U1") (pin "10") (pinfunction "OUTA_10") (pintype "bidirectional"))
    )
    (net (code "108") (name "MOTOR2+") (class "Default")
      (node (ref "SV1") (pin "1") (pinfunction "1_1") (pintype "passive"))
      (node (ref "SV1") (pin "3") (pinfunction "3_3") (pintype "passive"))
      (node (ref "SV1") (pin "5") (pinfunction "5_5") (pintype "passive"))
      (node (ref "U5") (pin "15") (pinfunction "OUTB_15") (pintype "bidirectional"))
    )
    (net (code "109") (name "MOTOR2-") (class "Default")
      (node (ref "SV1") (pin "2") (pinfunction "2_2") (pintype "passive"))
      (node (ref "SV1") (pin "4") (pinfunction "4_4") (pintype "passive"))
      (node (ref "SV1") (pin "6") (pinfunction "6_6") (pintype "passive"))
      (node (ref "U5") (pin "10") (pinfunction "OUTA_10") (pintype "bidirectional"))
    )
    (net (code "110") (name "Net-(3V3-PadA)") (class "Default")
      (node (ref "3V3") (pin "A") (pinfunction "A_A") (pintype "passive"))
      (node (ref "R27") (pin "1") (pinfunction "1_1") (pintype "passive"))
    )
    (net (code "111") (name "Net-(5V-PadA)") (class "Default")
      (node (ref "5V") (pin "A") (pinfunction "A_A") (pintype "passive"))
      (node (ref "R26") (pin "1") (pinfunction "1_1") (pintype "passive"))
    )
    (net (code "112") (name "Net-(B1-PadP$1)") (class "Default")
      (node (ref "B1") (pin "P$1") (pinfunction "P$1_P$1") (pintype "bidirectional"))
      (node (ref "R40") (pin "2") (pinfunction "2_2") (pintype "passive"))
    )
    (net (code "113") (name "Net-(B4-P1)") (class "Default")
      (node (ref "B4") (pin "P$1") (pinfunction "P1_P$1") (pintype "bidirectional"))
      (node (ref "SV10") (pin "1") (pinfunction "1_1") (pintype "passive"))
      (node (ref "U6") (pin "P$1") (pinfunction "IN1_P$1") (pintype "bidirectional"))
    )
    (net (code "114") (name "Net-(B5-P1)") (class "Default")
      (node (ref "B5") (pin "P$1") (pinfunction "P1_P$1") (pintype "bidirectional"))
      (node (ref "SV9") (pin "2") (pinfunction "2_2") (pintype "passive"))
      (node (ref "U6") (pin "P$6") (pinfunction "OUT2_P$6") (pintype "bidirectional"))
    )
    (net (code "115") (name "Net-(ETH1-INT{slash})") (class "Default")
      (node (ref "ETH1") (pin "P$6") (pinfunction "INT/_P$6") (pintype "bidirectional"))
      (node (ref "SV5") (pin "7") (pinfunction "7_7") (pintype "passive"))
      (node (ref "SV5") (pin "8") (pinfunction "8_8") (pintype "passive"))
    )
    (net (code "116") (name "Net-(ETH1-MISO)") (class "Default")
      (node (ref "ETH1") (pin "P$7") (pinfunction "MISO_P$7") (pintype "bidirectional"))
      (node (ref "SV5") (pin "10") (pinfunction "10_10") (pintype "passive"))
      (node (ref "SV5") (pin "9") (pinfunction "9_9") (pintype "passive"))
    )
    (net (code "117") (name "Net-(ETH1-MOSI)") (class "Default")
      (node (ref "ETH1") (pin "P$3") (pinfunction "MOSI_P$3") (pintype "bidirectional"))
      (node (ref "SV6") (pin "10") (pinfunction "10_10") (pintype "passive"))
      (node (ref "SV6") (pin "9") (pinfunction "9_9") (pintype "passive"))
    )
    (net (code "118") (name "Net-(ETH1-RESET)") (class "Default")
      (node (ref "ETH1") (pin "P$8") (pinfunction "RESET_P$8") (pintype "bidirectional"))
      (node (ref "SV6") (pin "7") (pinfunction "7_7") (pintype "passive"))
      (node (ref "SV6") (pin "8") (pinfunction "8_8") (pintype "passive"))
    )
    (net (code "119") (name "Net-(ETH1-SCLK)") (class "Default")
      (node (ref "ETH1") (pin "P$4") (pinfunction "SCLK_P$4") (pintype "bidirectional"))
      (node (ref "SV6") (pin "11") (pinfunction "11_11") (pintype "passive"))
      (node (ref "SV6") (pin "12") (pinfunction "12_12") (pintype "passive"))
    )
    (net (code "120") (name "Net-(ETH1-SS{slash})") (class "Default")
      (node (ref "ETH1") (pin "P$5") (pinfunction "SS/_P$5") (pintype "bidirectional"))
      (node (ref "SV5") (pin "11") (pinfunction "11_11") (pintype "passive"))
      (node (ref "SV5") (pin "12") (pinfunction "12_12") (pintype "passive"))
    )
    (net (code "121") (name "Net-(IC1A-O)") (class "Default")
      (node (ref "IC1") (pin "2") (pinfunction "O_2") (pintype "output"))
      (node (ref "LED1") (pin "C") (pinfunction "C_C") (pintype "passive"))
    )
    (net (code "122") (name "Net-(IC1B-O)") (class "Default")
      (node (ref "IC1") (pin "4") (pinfunction "O_4") (pintype "output"))
      (node (ref "LED2") (pin "C") (pinfunction "C_C") (pintype "passive"))
    )
    (net (code "123") (name "Net-(IC1C-O)") (class "Default")
      (node (ref "IC1") (pin "6") (pinfunction "O_6") (pintype "output"))
      (node (ref "LED3") (pin "C") (pinfunction "C_C") (pintype "passive"))
    )
    (net (code "124") (name "Net-(IC1D-O)") (class "Default")
      (node (ref "IC1") (pin "8") (pinfunction "O_8") (pintype "output"))
      (node (ref "LED4") (pin "C") (pinfunction "C_C") (pintype "passive"))
    )
    (net (code "125") (name "Net-(IC1E-O)") (class "Default")
      (node (ref "IC1") (pin "10") (pinfunction "O_10") (pintype "output"))
      (node (ref "LED5") (pin "C") (pinfunction "C_C") (pintype "passive"))
    )
    (net (code "126") (name "Net-(IC1F-O)") (class "Default")
      (node (ref "IC1") (pin "12") (pinfunction "O_12") (pintype "output"))
      (node (ref "LED6") (pin "C") (pinfunction "C_C") (pintype "passive"))
    )
    (net (code "127") (name "Net-(IC2A-O)") (class "Default")
      (node (ref "IC2") (pin "2") (pinfunction "O_2") (pintype "output"))
      (node (ref "LED7") (pin "C") (pinfunction "C_C") (pintype "passive"))
    )
    (net (code "128") (name "Net-(IC2B-O)") (class "Default")
      (node (ref "IC2") (pin "4") (pinfunction "O_4") (pintype "output"))
      (node (ref "LED8") (pin "C") (pinfunction "C_C") (pintype "passive"))
    )
    (net (code "129") (name "Net-(IC2C-O)") (class "Default")
      (node (ref "IC2") (pin "6") (pinfunction "O_6") (pintype "output"))
      (node (ref "LED9") (pin "C") (pinfunction "C_C") (pintype "passive"))
    )
    (net (code "130") (name "Net-(IC2D-O)") (class "Default")
      (node (ref "IC2") (pin "8") (pinfunction "O_8") (pintype "output"))
      (node (ref "LED10") (pin "C") (pinfunction "C_C") (pintype "passive"))
    )
    (net (code "131") (name "Net-(IC2E-O)") (class "Default")
      (node (ref "IC2") (pin "10") (pinfunction "O_10") (pintype "output"))
      (node (ref "LED11") (pin "C") (pinfunction "C_C") (pintype "passive"))
    )
    (net (code "132") (name "Net-(IC2F-O)") (class "Default")
      (node (ref "IC2") (pin "12") (pinfunction "O_12") (pintype "output"))
      (node (ref "LED12") (pin "C") (pinfunction "C_C") (pintype "passive"))
    )
    (net (code "133") (name "Net-(IC3A-O)") (class "Default")
      (node (ref "IC3") (pin "2") (pinfunction "O_2") (pintype "output"))
      (node (ref "LED13") (pin "C") (pinfunction "C_C") (pintype "passive"))
    )
    (net (code "134") (name "Net-(IC3B-O)") (class "Default")
      (node (ref "IC3") (pin "4") (pinfunction "O_4") (pintype "output"))
      (node (ref "LED14") (pin "C") (pinfunction "C_C") (pintype "passive"))
    )
    (net (code "135") (name "Net-(IC3C-O)") (class "Default")
      (node (ref "IC3") (pin "6") (pinfunction "O_6") (pintype "output"))
      (node (ref "LED15") (pin "C") (pinfunction "C_C") (pintype "passive"))
    )
    (net (code "136") (name "Net-(IC3D-O)") (class "Default")
      (node (ref "IC3") (pin "8") (pinfunction "O_8") (pintype "output"))
      (node (ref "LED16") (pin "C") (pinfunction "C_C") (pintype "passive"))
    )
    (net (code "137") (name "Net-(IC3E-I)") (class "Default")
      (node (ref "IC3") (pin "11") (pinfunction "I_11") (pintype "input"))
      (node (ref "J194") (pin "P$1") (pinfunction "P$1_P$1") (pintype "bidirectional"))
      (node (ref "J194") (pin "P$2") (pinfunction "P$2_P$2") (pintype "bidirectional"))
    )
    (net (code "138") (name "Net-(IC3E-O)") (class "Default")
      (node (ref "IC3") (pin "10") (pinfunction "O_10") (pintype "output"))
      (node (ref "R40") (pin "1") (pinfunction "1_1") (pintype "passive"))
    )
    (net (code "139") (name "Net-(J6-PadP$1)") (class "Default")
      (node (ref "J6") (pin "P$1") (pinfunction "P$1_P$1") (pintype "bidirectional"))
      (node (ref "J6") (pin "P$2") (pinfunction "P$2_P$2") (pintype "bidirectional"))
      (node (ref "J6") (pin "P$3") (pinfunction "P$3_P$3") (pintype "bidirectional"))
      (node (ref "R1") (pin "1") (pinfunction "1_1") (pintype "passive"))
    )
    (net (code "140") (name "Net-(J12-PadP$1)") (class "Default")
      (node (ref "J12") (pin "P$1") (pinfunction "P$1_P$1") (pintype "bidirectional"))
      (node (ref "J12") (pin "P$2") (pinfunction "P$2_P$2") (pintype "bidirectional"))
    )
    (net (code "141") (name "Net-(J13-PadP$1)") (class "Default")
      (node (ref "J13") (pin "P$1") (pinfunction "P$1_P$1") (pintype "bidirectional"))
      (node (ref "J13") (pin "P$2") (pinfunction "P$2_P$2") (pintype "bidirectional"))
    )
    (net (code "142") (name "Net-(J22-PadP$1)") (class "Default")
      (node (ref "J22") (pin "P$1") (pinfunction "P$1_P$1") (pintype "bidirectional"))
      (node (ref "J22") (pin "P$2") (pinfunction "P$2_P$2") (pintype "bidirectional"))
    )
    (net (code "143") (name "Net-(J24-PadP$1)") (class "Default")
      (node (ref "J24") (pin "P$1") (pinfunction "P$1_P$1") (pintype "bidirectional"))
      (node (ref "J24") (pin "P$2") (pinfunction "P$2_P$2") (pintype "bidirectional"))
      (node (ref "J24") (pin "P$3") (pinfunction "P$3_P$3") (pintype "bidirectional"))
      (node (ref "R2") (pin "1") (pinfunction "1_1") (pintype "passive"))
    )
    (net (code "144") (name "Net-(J88-PadP$1)") (class "Default")
      (node (ref "J88") (pin "P$1") (pinfunction "P$1_P$1") (pintype "bidirectional"))
      (node (ref "J91") (pin "P$1") (pinfunction "P$1_P$1") (pintype "bidirectional"))
      (node (ref "J91") (pin "P$2") (pinfunction "P$2_P$2") (pintype "bidirectional"))
    )
    (net (code "145") (name "Net-(J88-PadP$3)") (class "Default")
      (node (ref "J88") (pin "P$3") (pinfunction "P$3_P$3") (pintype "bidirectional"))
      (node (ref "J92") (pin "P$1") (pinfunction "P$1_P$1") (pintype "bidirectional"))
      (node (ref "J92") (pin "P$2") (pinfunction "P$2_P$2") (pintype "bidirectional"))
    )
    (net (code "146") (name "Net-(J88-PadP$4)") (class "Default")
      (node (ref "J88") (pin "P$4") (pinfunction "P$4_P$4") (pintype "bidirectional"))
      (node (ref "J93") (pin "P$1") (pinfunction "P$1_P$1") (pintype "bidirectional"))
      (node (ref "J93") (pin "P$2") (pinfunction "P$2_P$2") (pintype "bidirectional"))
    )
    (net (code "147") (name "Net-(J88-R+)") (class "Default")
      (node (ref "J88") (pin "P$2") (pinfunction "R+_P$2") (pintype "bidirectional"))
      (node (ref "J89") (pin "P$1") (pinfunction "P$1_P$1") (pintype "bidirectional"))
      (node (ref "J89") (pin "P$2") (pinfunction "P$2_P$2") (pintype "bidirectional"))
    )
    (net (code "148") (name "Net-(J88-R-)") (class "Default")
      (node (ref "J88") (pin "P$5") (pinfunction "R-_P$5") (pintype "bidirectional"))
      (node (ref "J90") (pin "P$1") (pinfunction "P$1_P$1") (pintype "bidirectional"))
      (node (ref "J90") (pin "P$2") (pinfunction "P$2_P$2") (pintype "bidirectional"))
    )
    (net (code "149") (name "Net-(LED1-PadA)") (class "Default")
      (node (ref "LED1") (pin "A") (pinfunction "A_A") (pintype "passive"))
      (node (ref "R11") (pin "1") (pinfunction "1_1") (pintype "passive"))
    )
    (net (code "150") (name "Net-(LED2-PadA)") (class "Default")
      (node (ref "LED2") (pin "A") (pinfunction "A_A") (pintype "passive"))
      (node (ref "R12") (pin "1") (pinfunction "1_1") (pintype "passive"))
    )
    (net (code "151") (name "Net-(LED3-PadA)") (class "Default")
      (node (ref "LED3") (pin "A") (pinfunction "A_A") (pintype "passive"))
      (node (ref "R13") (pin "1") (pinfunction "1_1") (pintype "passive"))
    )
    (net (code "152") (name "Net-(LED4-PadA)") (class "Default")
      (node (ref "LED4") (pin "A") (pinfunction "A_A") (pintype "passive"))
      (node (ref "R14") (pin "1") (pinfunction "1_1") (pintype "passive"))
    )
    (net (code "153") (name "Net-(LED5-PadA)") (class "Default")
      (node (ref "LED5") (pin "A") (pinfunction "A_A") (pintype "passive"))
      (node (ref "R15") (pin "1") (pinfunction "1_1") (pintype "passive"))
    )
    (net (code "154") (name "Net-(LED6-PadA)") (class "Default")
      (node (ref "LED6") (pin "A") (pinfunction "A_A") (pintype "passive"))
      (node (ref "R16") (pin "1") (pinfunction "1_1") (pintype "passive"))
    )
    (net (code "155") (name "Net-(LED7-PadA)") (class "Default")
      (node (ref "LED7") (pin "A") (pinfunction "A_A") (pintype "passive"))
      (node (ref "R17") (pin "1") (pinfunction "1_1") (pintype "passive"))
    )
    (net (code "156") (name "Net-(LED8-PadA)") (class "Default")
      (node (ref "LED8") (pin "A") (pinfunction "A_A") (pintype "passive"))
      (node (ref "R19") (pin "1") (pinfunction "1_1") (pintype "passive"))
    )
    (net (code "157") (name "Net-(LED9-PadA)") (class "Default")
      (node (ref "LED9") (pin "A") (pinfunction "A_A") (pintype "passive"))
      (node (ref "R20") (pin "1") (pinfunction "1_1") (pintype "passive"))
    )
    (net (code "158") (name "Net-(LED10-PadA)") (class "Default")
      (node (ref "LED10") (pin "A") (pinfunction "A_A") (pintype "passive"))
      (node (ref "R21") (pin "1") (pinfunction "1_1") (pintype "passive"))
    )
    (net (code "159") (name "Net-(LED11-PadA)") (class "Default")
      (node (ref "LED11") (pin "A") (pinfunction "A_A") (pintype "passive"))
      (node (ref "R22") (pin "1") (pinfunction "1_1") (pintype "passive"))
    )
    (net (code "160") (name "Net-(LED12-PadA)") (class "Default")
      (node (ref "LED12") (pin "A") (pinfunction "A_A") (pintype "passive"))
      (node (ref "R23") (pin "1") (pinfunction "1_1") (pintype "passive"))
    )
    (net (code "161") (name "Net-(LED13-PadA)") (class "Default")
      (node (ref "LED13") (pin "A") (pinfunction "A_A") (pintype "passive"))
      (node (ref "R28") (pin "1") (pinfunction "1_1") (pintype "passive"))
    )
    (net (code "162") (name "Net-(LED14-PadA)") (class "Default")
      (node (ref "LED14") (pin "A") (pinfunction "A_A") (pintype "passive"))
      (node (ref "R29") (pin "1") (pinfunction "1_1") (pintype "passive"))
    )
    (net (code "163") (name "Net-(LED15-PadA)") (class "Default")
      (node (ref "LED15") (pin "A") (pinfunction "A_A") (pintype "passive"))
      (node (ref "R30") (pin "1") (pinfunction "1_1") (pintype "passive"))
    )
    (net (code "164") (name "Net-(LED16-PadA)") (class "Default")
      (node (ref "LED16") (pin "A") (pinfunction "A_A") (pintype "passive"))
      (node (ref "R31") (pin "1") (pinfunction "1_1") (pintype "passive"))
    )
    (net (code "165") (name "Net-(LED17-PadA)") (class "Default")
      (node (ref "LED17") (pin "A") (pinfunction "A_A") (pintype "passive"))
      (node (ref "R36") (pin "1") (pinfunction "1_1") (pintype "passive"))
    )
    (net (code "166") (name "Net-(S1-P3)") (class "Default")
      (node (ref "R24") (pin "1") (pinfunction "1_1") (pintype "passive"))
      (node (ref "S1") (pin "P$3") (pinfunction "P3_P$3") (pintype "bidirectional"))
    )
    (net (code "167") (name "Net-(S130-PadP$1)") (class "Default")
      (node (ref "S130") (pin "P$1") (pinfunction "P$1_P$1") (pintype "bidirectional"))
      (node (ref "S130") (pin "P$2") (pinfunction "P$2_P$2") (pintype "bidirectional"))
      (node (ref "S130") (pin "P$3") (pinfunction "P$3_P$3") (pintype "bidirectional"))
      (node (ref "S130") (pin "P$4") (pinfunction "P$4_P$4") (pintype "bidirectional"))
      (node (ref "S130") (pin "P$5") (pinfunction "P$5_P$5") (pintype "bidirectional"))
    )
    (net (code "168") (name "Net-(S138-PadP$1)") (class "Default")
      (node (ref "S138") (pin "P$1") (pinfunction "P$1_P$1") (pintype "bidirectional"))
      (node (ref "S138") (pin "P$2") (pinfunction "P$2_P$2") (pintype "bidirectional"))
      (node (ref "S138") (pin "P$3") (pinfunction "P$3_P$3") (pintype "bidirectional"))
      (node (ref "S138") (pin "P$4") (pinfunction "P$4_P$4") (pintype "bidirectional"))
      (node (ref "S138") (pin "P$5") (pinfunction "P$5_P$5") (pintype "bidirectional"))
    )
    (net (code "169") (name "Net-(S139-PadP$1)") (class "Default")
      (node (ref "S139") (pin "P$1") (pinfunction "P$1_P$1") (pintype "bidirectional"))
      (node (ref "S139") (pin "P$2") (pinfunction "P$2_P$2") (pintype "bidirectional"))
      (node (ref "S139") (pin "P$3") (pinfunction "P$3_P$3") (pintype "bidirectional"))
      (node (ref "S139") (pin "P$4") (pinfunction "P$4_P$4") (pintype "bidirectional"))
      (node (ref "S139") (pin "P$5") (pinfunction "P$5_P$5") (pintype "bidirectional"))
    )
    (net (code "170") (name "Net-(S147-PadP$1)") (class "Default")
      (node (ref "S147") (pin "P$1") (pinfunction "P$1_P$1") (pintype "bidirectional"))
      (node (ref "S147") (pin "P$2") (pinfunction "P$2_P$2") (pintype "bidirectional"))
      (node (ref "S147") (pin "P$3") (pinfunction "P$3_P$3") (pintype "bidirectional"))
      (node (ref "S147") (pin "P$4") (pinfunction "P$4_P$4") (pintype "bidirectional"))
      (node (ref "S147") (pin "P$5") (pinfunction "P$5_P$5") (pintype "bidirectional"))
    )
    (net (code "171") (name "Net-(S159-P3)") (class "Default")
      (node (ref "R18") (pin "1") (pinfunction "1_1") (pintype "passive"))
      (node (ref "S159") (pin "P$3") (pinfunction "P3_P$3") (pintype "bidirectional"))
    )
    (net (code "172") (name "Net-(S167-PadP$1)") (class "Default")
      (node (ref "S167") (pin "P$1") (pinfunction "P$1_P$1") (pintype "bidirectional"))
      (node (ref "S167") (pin "P$2") (pinfunction "P$2_P$2") (pintype "bidirectional"))
      (node (ref "S167") (pin "P$3") (pinfunction "P$3_P$3") (pintype "bidirectional"))
      (node (ref "S167") (pin "P$4") (pinfunction "P$4_P$4") (pintype "bidirectional"))
      (node (ref "S167") (pin "P$5") (pinfunction "P$5_P$5") (pintype "bidirectional"))
    )
    (net (code "173") (name "Net-(S168-PadP$1)") (class "Default")
      (node (ref "S168") (pin "P$1") (pinfunction "P$1_P$1") (pintype "bidirectional"))
      (node (ref "S168") (pin "P$2") (pinfunction "P$2_P$2") (pintype "bidirectional"))
      (node (ref "S168") (pin "P$3") (pinfunction "P$3_P$3") (pintype "bidirectional"))
      (node (ref "S168") (pin "P$4") (pinfunction "P$4_P$4") (pintype "bidirectional"))
      (node (ref "S168") (pin "P$5") (pinfunction "P$5_P$5") (pintype "bidirectional"))
    )
    (net (code "174") (name "Net-(S169-PadP$1)") (class "Default")
      (node (ref "S169") (pin "P$1") (pinfunction "P$1_P$1") (pintype "bidirectional"))
      (node (ref "S169") (pin "P$2") (pinfunction "P$2_P$2") (pintype "bidirectional"))
      (node (ref "S169") (pin "P$3") (pinfunction "P$3_P$3") (pintype "bidirectional"))
      (node (ref "S169") (pin "P$4") (pinfunction "P$4_P$4") (pintype "bidirectional"))
      (node (ref "S169") (pin "P$5") (pinfunction "P$5_P$5") (pintype "bidirectional"))
    )
    (net (code "175") (name "Net-(S170-PadP$1)") (class "Default")
      (node (ref "S170") (pin "P$1") (pinfunction "P$1_P$1") (pintype "bidirectional"))
      (node (ref "S170") (pin "P$2") (pinfunction "P$2_P$2") (pintype "bidirectional"))
      (node (ref "S170") (pin "P$3") (pinfunction "P$3_P$3") (pintype "bidirectional"))
      (node (ref "S170") (pin "P$4") (pinfunction "P$4_P$4") (pintype "bidirectional"))
      (node (ref "S170") (pin "P$5") (pinfunction "P$5_P$5") (pintype "bidirectional"))
    )
    (net (code "176") (name "Net-(S171-PadP$1)") (class "Default")
      (node (ref "S171") (pin "P$1") (pinfunction "P$1_P$1") (pintype "bidirectional"))
      (node (ref "S171") (pin "P$2") (pinfunction "P$2_P$2") (pintype "bidirectional"))
      (node (ref "S171") (pin "P$3") (pinfunction "P$3_P$3") (pintype "bidirectional"))
      (node (ref "S171") (pin "P$4") (pinfunction "P$4_P$4") (pintype "bidirectional"))
      (node (ref "S171") (pin "P$5") (pinfunction "P$5_P$5") (pintype "bidirectional"))
    )
    (net (code "177") (name "Net-(S172-PadP$1)") (class "Default")
      (node (ref "S172") (pin "P$1") (pinfunction "P$1_P$1") (pintype "bidirectional"))
      (node (ref "S172") (pin "P$2") (pinfunction "P$2_P$2") (pintype "bidirectional"))
      (node (ref "S172") (pin "P$3") (pinfunction "P$3_P$3") (pintype "bidirectional"))
      (node (ref "S172") (pin "P$4") (pinfunction "P$4_P$4") (pintype "bidirectional"))
      (node (ref "S172") (pin "P$5") (pinfunction "P$5_P$5") (pintype "bidirectional"))
    )
    (net (code "178") (name "Net-(S173-PadP$1)") (class "Default")
      (node (ref "S173") (pin "P$1") (pinfunction "P$1_P$1") (pintype "bidirectional"))
      (node (ref "S173") (pin "P$2") (pinfunction "P$2_P$2") (pintype "bidirectional"))
      (node (ref "S173") (pin "P$3") (pinfunction "P$3_P$3") (pintype "bidirectional"))
      (node (ref "S173") (pin "P$4") (pinfunction "P$4_P$4") (pintype "bidirectional"))
      (node (ref "S173") (pin "P$5") (pinfunction "P$5_P$5") (pintype "bidirectional"))
    )
    (net (code "179") (name "Net-(S174-PadP$1)") (class "Default")
      (node (ref "S174") (pin "P$1") (pinfunction "P$1_P$1") (pintype "bidirectional"))
      (node (ref "S174") (pin "P$2") (pinfunction "P$2_P$2") (pintype "bidirectional"))
      (node (ref "S174") (pin "P$3") (pinfunction "P$3_P$3") (pintype "bidirectional"))
      (node (ref "S174") (pin "P$4") (pinfunction "P$4_P$4") (pintype "bidirectional"))
      (node (ref "S174") (pin "P$5") (pinfunction "P$5_P$5") (pintype "bidirectional"))
    )
    (net (code "180") (name "Net-(S175-PadP$1)") (class "Default")
      (node (ref "S175") (pin "P$1") (pinfunction "P$1_P$1") (pintype "bidirectional"))
      (node (ref "S175") (pin "P$2") (pinfunction "P$2_P$2") (pintype "bidirectional"))
      (node (ref "S175") (pin "P$3") (pinfunction "P$3_P$3") (pintype "bidirectional"))
      (node (ref "S175") (pin "P$4") (pinfunction "P$4_P$4") (pintype "bidirectional"))
      (node (ref "S175") (pin "P$5") (pinfunction "P$5_P$5") (pintype "bidirectional"))
    )
    (net (code "181") (name "Net-(S176-PadP$1)") (class "Default")
      (node (ref "S176") (pin "P$1") (pinfunction "P$1_P$1") (pintype "bidirectional"))
      (node (ref "S176") (pin "P$2") (pinfunction "P$2_P$2") (pintype "bidirectional"))
      (node (ref "S176") (pin "P$3") (pinfunction "P$3_P$3") (pintype "bidirectional"))
      (node (ref "S176") (pin "P$4") (pinfunction "P$4_P$4") (pintype "bidirectional"))
      (node (ref "S176") (pin "P$5") (pinfunction "P$5_P$5") (pintype "bidirectional"))
    )
    (net (code "182") (name "Net-(S177-PadP$1)") (class "Default")
      (node (ref "S177") (pin "P$1") (pinfunction "P$1_P$1") (pintype "bidirectional"))
      (node (ref "S177") (pin "P$2") (pinfunction "P$2_P$2") (pintype "bidirectional"))
      (node (ref "S177") (pin "P$3") (pinfunction "P$3_P$3") (pintype "bidirectional"))
      (node (ref "S177") (pin "P$4") (pinfunction "P$4_P$4") (pintype "bidirectional"))
      (node (ref "S177") (pin "P$5") (pinfunction "P$5_P$5") (pintype "bidirectional"))
    )
    (net (code "183") (name "Net-(S178-PadP$1)") (class "Default")
      (node (ref "S178") (pin "P$1") (pinfunction "P$1_P$1") (pintype "bidirectional"))
      (node (ref "S178") (pin "P$2") (pinfunction "P$2_P$2") (pintype "bidirectional"))
      (node (ref "S178") (pin "P$3") (pinfunction "P$3_P$3") (pintype "bidirectional"))
      (node (ref "S178") (pin "P$4") (pinfunction "P$4_P$4") (pintype "bidirectional"))
      (node (ref "S178") (pin "P$5") (pinfunction "P$5_P$5") (pintype "bidirectional"))
    )
    (net (code "184") (name "Net-(S179-PadP$1)") (class "Default")
      (node (ref "S179") (pin "P$1") (pinfunction "P$1_P$1") (pintype "bidirectional"))
      (node (ref "S179") (pin "P$2") (pinfunction "P$2_P$2") (pintype "bidirectional"))
      (node (ref "S179") (pin "P$3") (pinfunction "P$3_P$3") (pintype "bidirectional"))
      (node (ref "S179") (pin "P$4") (pinfunction "P$4_P$4") (pintype "bidirectional"))
      (node (ref "S179") (pin "P$5") (pinfunction "P$5_P$5") (pintype "bidirectional"))
    )
    (net (code "185") (name "Net-(S180-PadP$1)") (class "Default")
      (node (ref "S180") (pin "P$1") (pinfunction "P$1_P$1") (pintype "bidirectional"))
      (node (ref "S180") (pin "P$2") (pinfunction "P$2_P$2") (pintype "bidirectional"))
      (node (ref "S180") (pin "P$3") (pinfunction "P$3_P$3") (pintype "bidirectional"))
      (node (ref "S180") (pin "P$4") (pinfunction "P$4_P$4") (pintype "bidirectional"))
      (node (ref "S180") (pin "P$5") (pinfunction "P$5_P$5") (pintype "bidirectional"))
    )
    (net (code "186") (name "Net-(S181-PadP$1)") (class "Default")
      (node (ref "S181") (pin "P$1") (pinfunction "P$1_P$1") (pintype "bidirectional"))
      (node (ref "S181") (pin "P$2") (pinfunction "P$2_P$2") (pintype "bidirectional"))
      (node (ref "S181") (pin "P$3") (pinfunction "P$3_P$3") (pintype "bidirectional"))
      (node (ref "S181") (pin "P$4") (pinfunction "P$4_P$4") (pintype "bidirectional"))
      (node (ref "S181") (pin "P$5") (pinfunction "P$5_P$5") (pintype "bidirectional"))
    )
    (net (code "187") (name "Net-(S182-PadP$1)") (class "Default")
      (node (ref "S182") (pin "P$1") (pinfunction "P$1_P$1") (pintype "bidirectional"))
      (node (ref "S182") (pin "P$2") (pinfunction "P$2_P$2") (pintype "bidirectional"))
      (node (ref "S182") (pin "P$3") (pinfunction "P$3_P$3") (pintype "bidirectional"))
      (node (ref "S182") (pin "P$4") (pinfunction "P$4_P$4") (pintype "bidirectional"))
      (node (ref "S182") (pin "P$5") (pinfunction "P$5_P$5") (pintype "bidirectional"))
    )
    (net (code "188") (name "Net-(S183-PadP$1)") (class "Default")
      (node (ref "S183") (pin "P$1") (pinfunction "P$1_P$1") (pintype "bidirectional"))
      (node (ref "S183") (pin "P$2") (pinfunction "P$2_P$2") (pintype "bidirectional"))
      (node (ref "S183") (pin "P$3") (pinfunction "P$3_P$3") (pintype "bidirectional"))
      (node (ref "S183") (pin "P$4") (pinfunction "P$4_P$4") (pintype "bidirectional"))
      (node (ref "S183") (pin "P$5") (pinfunction "P$5_P$5") (pintype "bidirectional"))
    )
    (net (code "189") (name "Net-(S184-PadP$1)") (class "Default")
      (node (ref "S184") (pin "P$1") (pinfunction "P$1_P$1") (pintype "bidirectional"))
      (node (ref "S184") (pin "P$2") (pinfunction "P$2_P$2") (pintype "bidirectional"))
      (node (ref "S184") (pin "P$3") (pinfunction "P$3_P$3") (pintype "bidirectional"))
      (node (ref "S184") (pin "P$4") (pinfunction "P$4_P$4") (pintype "bidirectional"))
      (node (ref "S184") (pin "P$5") (pinfunction "P$5_P$5") (pintype "bidirectional"))
    )
    (net (code "190") (name "Net-(S185-PadP$1)") (class "Default")
      (node (ref "S185") (pin "P$1") (pinfunction "P$1_P$1") (pintype "bidirectional"))
      (node (ref "S185") (pin "P$2") (pinfunction "P$2_P$2") (pintype "bidirectional"))
      (node (ref "S185") (pin "P$3") (pinfunction "P$3_P$3") (pintype "bidirectional"))
      (node (ref "S185") (pin "P$4") (pinfunction "P$4_P$4") (pintype "bidirectional"))
      (node (ref "S185") (pin "P$5") (pinfunction "P$5_P$5") (pintype "bidirectional"))
    )
    (net (code "191") (name "Net-(S186-PadP$1)") (class "Default")
      (node (ref "S186") (pin "P$1") (pinfunction "P$1_P$1") (pintype "bidirectional"))
      (node (ref "S186") (pin "P$2") (pinfunction "P$2_P$2") (pintype "bidirectional"))
      (node (ref "S186") (pin "P$3") (pinfunction "P$3_P$3") (pintype "bidirectional"))
      (node (ref "S186") (pin "P$4") (pinfunction "P$4_P$4") (pintype "bidirectional"))
      (node (ref "S186") (pin "P$5") (pinfunction "P$5_P$5") (pintype "bidirectional"))
    )
    (net (code "192") (name "Net-(S187-PadP$1)") (class "Default")
      (node (ref "S187") (pin "P$1") (pinfunction "P$1_P$1") (pintype "bidirectional"))
      (node (ref "S187") (pin "P$2") (pinfunction "P$2_P$2") (pintype "bidirectional"))
      (node (ref "S187") (pin "P$3") (pinfunction "P$3_P$3") (pintype "bidirectional"))
      (node (ref "S187") (pin "P$4") (pinfunction "P$4_P$4") (pintype "bidirectional"))
      (node (ref "S187") (pin "P$5") (pinfunction "P$5_P$5") (pintype "bidirectional"))
    )
    (net (code "193") (name "Net-(S188-PadP$1)") (class "Default")
      (node (ref "S188") (pin "P$1") (pinfunction "P$1_P$1") (pintype "bidirectional"))
      (node (ref "S188") (pin "P$2") (pinfunction "P$2_P$2") (pintype "bidirectional"))
      (node (ref "S188") (pin "P$3") (pinfunction "P$3_P$3") (pintype "bidirectional"))
      (node (ref "S188") (pin "P$4") (pinfunction "P$4_P$4") (pintype "bidirectional"))
      (node (ref "S188") (pin "P$5") (pinfunction "P$5_P$5") (pintype "bidirectional"))
    )
    (net (code "194") (name "Net-(S189-PadP$1)") (class "Default")
      (node (ref "S189") (pin "P$1") (pinfunction "P$1_P$1") (pintype "bidirectional"))
      (node (ref "S189") (pin "P$2") (pinfunction "P$2_P$2") (pintype "bidirectional"))
      (node (ref "S189") (pin "P$3") (pinfunction "P$3_P$3") (pintype "bidirectional"))
      (node (ref "S189") (pin "P$4") (pinfunction "P$4_P$4") (pintype "bidirectional"))
      (node (ref "S189") (pin "P$5") (pinfunction "P$5_P$5") (pintype "bidirectional"))
    )
    (net (code "195") (name "Net-(S210-PadP$1)") (class "Default")
      (node (ref "S210") (pin "P$1") (pinfunction "P$1_P$1") (pintype "bidirectional"))
      (node (ref "S210") (pin "P$2") (pinfunction "P$2_P$2") (pintype "bidirectional"))
      (node (ref "S210") (pin "P$3") (pinfunction "P$3_P$3") (pintype "bidirectional"))
      (node (ref "S210") (pin "P$4") (pinfunction "P$4_P$4") (pintype "bidirectional"))
      (node (ref "S210") (pin "P$5") (pinfunction "P$5_P$5") (pintype "bidirectional"))
    )
    (net (code "196") (name "Net-(S211-PadP$1)") (class "Default")
      (node (ref "S211") (pin "P$1") (pinfunction "P$1_P$1") (pintype "bidirectional"))
      (node (ref "S211") (pin "P$2") (pinfunction "P$2_P$2") (pintype "bidirectional"))
      (node (ref "S211") (pin "P$3") (pinfunction "P$3_P$3") (pintype "bidirectional"))
      (node (ref "S211") (pin "P$4") (pinfunction "P$4_P$4") (pintype "bidirectional"))
      (node (ref "S211") (pin "P$5") (pinfunction "P$5_P$5") (pintype "bidirectional"))
    )
    (net (code "197") (name "Net-(S212-PadP$1)") (class "Default")
      (node (ref "S212") (pin "P$1") (pinfunction "P$1_P$1") (pintype "bidirectional"))
      (node (ref "S212") (pin "P$2") (pinfunction "P$2_P$2") (pintype "bidirectional"))
      (node (ref "S212") (pin "P$3") (pinfunction "P$3_P$3") (pintype "bidirectional"))
      (node (ref "S212") (pin "P$4") (pinfunction "P$4_P$4") (pintype "bidirectional"))
      (node (ref "S212") (pin "P$5") (pinfunction "P$5_P$5") (pintype "bidirectional"))
    )
    (net (code "198") (name "Net-(S213-PadP$1)") (class "Default")
      (node (ref "S213") (pin "P$1") (pinfunction "P$1_P$1") (pintype "bidirectional"))
      (node (ref "S213") (pin "P$2") (pinfunction "P$2_P$2") (pintype "bidirectional"))
      (node (ref "S213") (pin "P$3") (pinfunction "P$3_P$3") (pintype "bidirectional"))
      (node (ref "S213") (pin "P$4") (pinfunction "P$4_P$4") (pintype "bidirectional"))
      (node (ref "S213") (pin "P$5") (pinfunction "P$5_P$5") (pintype "bidirectional"))
    )
    (net (code "199") (name "Net-(S214-PadP$1)") (class "Default")
      (node (ref "S214") (pin "P$1") (pinfunction "P$1_P$1") (pintype "bidirectional"))
      (node (ref "S214") (pin "P$2") (pinfunction "P$2_P$2") (pintype "bidirectional"))
      (node (ref "S214") (pin "P$3") (pinfunction "P$3_P$3") (pintype "bidirectional"))
      (node (ref "S214") (pin "P$4") (pinfunction "P$4_P$4") (pintype "bidirectional"))
      (node (ref "S214") (pin "P$5") (pinfunction "P$5_P$5") (pintype "bidirectional"))
    )
    (net (code "200") (name "Net-(S215-PadP$1)") (class "Default")
      (node (ref "S215") (pin "P$1") (pinfunction "P$1_P$1") (pintype "bidirectional"))
      (node (ref "S215") (pin "P$2") (pinfunction "P$2_P$2") (pintype "bidirectional"))
      (node (ref "S215") (pin "P$3") (pinfunction "P$3_P$3") (pintype "bidirectional"))
      (node (ref "S215") (pin "P$4") (pinfunction "P$4_P$4") (pintype "bidirectional"))
      (node (ref "S215") (pin "P$5") (pinfunction "P$5_P$5") (pintype "bidirectional"))
    )
    (net (code "201") (name "Net-(S216-PadP$1)") (class "Default")
      (node (ref "S216") (pin "P$1") (pinfunction "P$1_P$1") (pintype "bidirectional"))
      (node (ref "S216") (pin "P$2") (pinfunction "P$2_P$2") (pintype "bidirectional"))
      (node (ref "S216") (pin "P$3") (pinfunction "P$3_P$3") (pintype "bidirectional"))
      (node (ref "S216") (pin "P$4") (pinfunction "P$4_P$4") (pintype "bidirectional"))
      (node (ref "S216") (pin "P$5") (pinfunction "P$5_P$5") (pintype "bidirectional"))
    )
    (net (code "202") (name "Net-(S217-PadP$1)") (class "Default")
      (node (ref "S217") (pin "P$1") (pinfunction "P$1_P$1") (pintype "bidirectional"))
      (node (ref "S217") (pin "P$2") (pinfunction "P$2_P$2") (pintype "bidirectional"))
      (node (ref "S217") (pin "P$3") (pinfunction "P$3_P$3") (pintype "bidirectional"))
      (node (ref "S217") (pin "P$4") (pinfunction "P$4_P$4") (pintype "bidirectional"))
      (node (ref "S217") (pin "P$5") (pinfunction "P$5_P$5") (pintype "bidirectional"))
    )
    (net (code "203") (name "Net-(S218-PadP$1)") (class "Default")
      (node (ref "S218") (pin "P$1") (pinfunction "P$1_P$1") (pintype "bidirectional"))
      (node (ref "S218") (pin "P$2") (pinfunction "P$2_P$2") (pintype "bidirectional"))
      (node (ref "S218") (pin "P$3") (pinfunction "P$3_P$3") (pintype "bidirectional"))
      (node (ref "S218") (pin "P$4") (pinfunction "P$4_P$4") (pintype "bidirectional"))
      (node (ref "S218") (pin "P$5") (pinfunction "P$5_P$5") (pintype "bidirectional"))
    )
    (net (code "204") (name "Net-(S219-PadP$1)") (class "Default")
      (node (ref "S219") (pin "P$1") (pinfunction "P$1_P$1") (pintype "bidirectional"))
      (node (ref "S219") (pin "P$2") (pinfunction "P$2_P$2") (pintype "bidirectional"))
      (node (ref "S219") (pin "P$3") (pinfunction "P$3_P$3") (pintype "bidirectional"))
      (node (ref "S219") (pin "P$4") (pinfunction "P$4_P$4") (pintype "bidirectional"))
      (node (ref "S219") (pin "P$5") (pinfunction "P$5_P$5") (pintype "bidirectional"))
    )
    (net (code "205") (name "Net-(S220-PadP$1)") (class "Default")
      (node (ref "S220") (pin "P$1") (pinfunction "P$1_P$1") (pintype "bidirectional"))
      (node (ref "S220") (pin "P$2") (pinfunction "P$2_P$2") (pintype "bidirectional"))
      (node (ref "S220") (pin "P$3") (pinfunction "P$3_P$3") (pintype "bidirectional"))
      (node (ref "S220") (pin "P$4") (pinfunction "P$4_P$4") (pintype "bidirectional"))
      (node (ref "S220") (pin "P$5") (pinfunction "P$5_P$5") (pintype "bidirectional"))
    )
    (net (code "206") (name "Net-(S221-PadP$1)") (class "Default")
      (node (ref "S221") (pin "P$1") (pinfunction "P$1_P$1") (pintype "bidirectional"))
      (node (ref "S221") (pin "P$2") (pinfunction "P$2_P$2") (pintype "bidirectional"))
      (node (ref "S221") (pin "P$3") (pinfunction "P$3_P$3") (pintype "bidirectional"))
      (node (ref "S221") (pin "P$4") (pinfunction "P$4_P$4") (pintype "bidirectional"))
      (node (ref "S221") (pin "P$5") (pinfunction "P$5_P$5") (pintype "bidirectional"))
    )
    (net (code "207") (name "Net-(S222-PadP$1)") (class "Default")
      (node (ref "S222") (pin "P$1") (pinfunction "P$1_P$1") (pintype "bidirectional"))
      (node (ref "S222") (pin "P$2") (pinfunction "P$2_P$2") (pintype "bidirectional"))
      (node (ref "S222") (pin "P$3") (pinfunction "P$3_P$3") (pintype "bidirectional"))
      (node (ref "S222") (pin "P$4") (pinfunction "P$4_P$4") (pintype "bidirectional"))
      (node (ref "S222") (pin "P$5") (pinfunction "P$5_P$5") (pintype "bidirectional"))
    )
    (net (code "208") (name "Net-(S223-PadP$1)") (class "Default")
      (node (ref "S223") (pin "P$1") (pinfunction "P$1_P$1") (pintype "bidirectional"))
      (node (ref "S223") (pin "P$2") (pinfunction "P$2_P$2") (pintype "bidirectional"))
      (node (ref "S223") (pin "P$3") (pinfunction "P$3_P$3") (pintype "bidirectional"))
      (node (ref "S223") (pin "P$4") (pinfunction "P$4_P$4") (pintype "bidirectional"))
      (node (ref "S223") (pin "P$5") (pinfunction "P$5_P$5") (pintype "bidirectional"))
    )
    (net (code "209") (name "Net-(S224-PadP$1)") (class "Default")
      (node (ref "S224") (pin "P$1") (pinfunction "P$1_P$1") (pintype "bidirectional"))
      (node (ref "S224") (pin "P$2") (pinfunction "P$2_P$2") (pintype "bidirectional"))
      (node (ref "S224") (pin "P$3") (pinfunction "P$3_P$3") (pintype "bidirectional"))
      (node (ref "S224") (pin "P$4") (pinfunction "P$4_P$4") (pintype "bidirectional"))
      (node (ref "S224") (pin "P$5") (pinfunction "P$5_P$5") (pintype "bidirectional"))
    )
    (net (code "210") (name "Net-(S225-PadP$1)") (class "Default")
      (node (ref "S225") (pin "P$1") (pinfunction "P$1_P$1") (pintype "bidirectional"))
      (node (ref "S225") (pin "P$2") (pinfunction "P$2_P$2") (pintype "bidirectional"))
      (node (ref "S225") (pin "P$3") (pinfunction "P$3_P$3") (pintype "bidirectional"))
      (node (ref "S225") (pin "P$4") (pinfunction "P$4_P$4") (pintype "bidirectional"))
      (node (ref "S225") (pin "P$5") (pinfunction "P$5_P$5") (pintype "bidirectional"))
    )
    (net (code "211") (name "Net-(S226-PadP$1)") (class "Default")
      (node (ref "S226") (pin "P$1") (pinfunction "P$1_P$1") (pintype "bidirectional"))
      (node (ref "S226") (pin "P$2") (pinfunction "P$2_P$2") (pintype "bidirectional"))
      (node (ref "S226") (pin "P$3") (pinfunction "P$3_P$3") (pintype "bidirectional"))
      (node (ref "S226") (pin "P$4") (pinfunction "P$4_P$4") (pintype "bidirectional"))
      (node (ref "S226") (pin "P$5") (pinfunction "P$5_P$5") (pintype "bidirectional"))
    )
    (net (code "212") (name "Net-(SV2-Pad7)") (class "Default")
      (node (ref "SV2") (pin "7") (pinfunction "7_7") (pintype "passive"))
      (node (ref "SV2") (pin "8") (pinfunction "8_8") (pintype "passive"))
    )
    (net (code "213") (name "Net-(SV2-Pad10)") (class "Default")
      (node (ref "SV2") (pin "10") (pinfunction "10_10") (pintype "passive"))
      (node (ref "SV2") (pin "9") (pinfunction "9_9") (pintype "passive"))
    )
    (net (code "214") (name "Net-(SV2-Pad11)") (class "Default")
      (node (ref "SV2") (pin "11") (pinfunction "11_11") (pintype "passive"))
      (node (ref "SV2") (pin "12") (pinfunction "12_12") (pintype "passive"))
    )
    (net (code "215") (name "Net-(SV2-Pad15)") (class "Default")
      (node (ref "SV2") (pin "15") (pinfunction "15_15") (pintype "passive"))
      (node (ref "SV2") (pin "16") (pinfunction "16_16") (pintype "passive"))
    )
    (net (code "216") (name "Net-(SV2-Pad17)") (class "Default")
      (node (ref "SV2") (pin "17") (pinfunction "17_17") (pintype "passive"))
      (node (ref "SV2") (pin "18") (pinfunction "18_18") (pintype "passive"))
    )
    (net (code "217") (name "Net-(SV2-Pad21)") (class "Default")
      (node (ref "SV2") (pin "21") (pinfunction "21_21") (pintype "passive"))
      (node (ref "SV2") (pin "22") (pinfunction "22_22") (pintype "passive"))
    )
    (net (code "218") (name "Net-(SV2-Pad23)") (class "Default")
      (node (ref "SV2") (pin "23") (pinfunction "23_23") (pintype "passive"))
      (node (ref "SV2") (pin "24") (pinfunction "24_24") (pintype "passive"))
    )
    (net (code "219") (name "Net-(SV2-Pad25)") (class "Default")
      (node (ref "SV2") (pin "25") (pinfunction "25_25") (pintype "passive"))
      (node (ref "SV2") (pin "26") (pinfunction "26_26") (pintype "passive"))
    )
    (net (code "220") (name "Net-(SV2-Pad27)") (class "Default")
      (node (ref "SV2") (pin "27") (pinfunction "27_27") (pintype "passive"))
      (node (ref "SV2") (pin "28") (pinfunction "28_28") (pintype "passive"))
    )
    (net (code "221") (name "Net-(SV2-Pad31)") (class "Default")
      (node (ref "SV2") (pin "31") (pinfunction "31_31") (pintype "passive"))
      (node (ref "SV2") (pin "32") (pinfunction "32_32") (pintype "passive"))
    )
    (net (code "222") (name "Net-(SV2-Pad35)") (class "Default")
      (node (ref "SV2") (pin "35") (pinfunction "35_35") (pintype "passive"))
      (node (ref "SV2") (pin "36") (pinfunction "36_36") (pintype "passive"))
    )
    (net (code "223") (name "Net-(SV2-Pad37)") (class "Default")
      (node (ref "SV2") (pin "37") (pinfunction "37_37") (pintype "passive"))
      (node (ref "SV2") (pin "38") (pinfunction "38_38") (pintype "passive"))
    )
    (net (code "224") (name "Net-(SV2-Pad39)") (class "Default")
      (node (ref "SV2") (pin "39") (pinfunction "39_39") (pintype "passive"))
      (node (ref "SV2") (pin "40") (pinfunction "40_40") (pintype "passive"))
    )
    (net (code "225") (name "Net-(SV4-Pad1)") (class "Default")
      (node (ref "SV4") (pin "1") (pinfunction "1_1") (pintype "passive"))
      (node (ref "SV4") (pin "2") (pinfunction "2_2") (pintype "passive"))
    )
    (net (code "226") (name "Net-(SV4-Pad3)") (class "Default")
      (node (ref "SV4") (pin "3") (pinfunction "3_3") (pintype "passive"))
      (node (ref "SV4") (pin "4") (pinfunction "4_4") (pintype "passive"))
    )
    (net (code "227") (name "Net-(SV4-Pad5)") (class "Default")
      (node (ref "SV4") (pin "5") (pinfunction "5_5") (pintype "passive"))
      (node (ref "SV4") (pin "6") (pinfunction "6_6") (pintype "passive"))
    )
    (net (code "228") (name "Net-(SV4-Pad7)") (class "Default")
      (node (ref "SV4") (pin "7") (pinfunction "7_7") (pintype "passive"))
      (node (ref "SV4") (pin "8") (pinfunction "8_8") (pintype "passive"))
    )
    (net (code "229") (name "Net-(SV4-Pad11)") (class "Default")
      (node (ref "SV4") (pin "11") (pinfunction "11_11") (pintype "passive"))
      (node (ref "SV4") (pin "12") (pinfunction "12_12") (pintype "passive"))
    )
    (net (code "230") (name "Net-(SV4-Pad13)") (class "Default")
      (node (ref "SV4") (pin "13") (pinfunction "13_13") (pintype "passive"))
      (node (ref "SV4") (pin "14") (pinfunction "14_14") (pintype "passive"))
    )
    (net (code "231") (name "Net-(SV4-Pad15)") (class "Default")
      (node (ref "SV4") (pin "15") (pinfunction "15_15") (pintype "passive"))
      (node (ref "SV4") (pin "16") (pinfunction "16_16") (pintype "passive"))
    )
    (net (code "232") (name "Net-(SV4-Pad17)") (class "Default")
      (node (ref "SV4") (pin "17") (pinfunction "17_17") (pintype "passive"))
      (node (ref "SV4") (pin "18") (pinfunction "18_18") (pintype "passive"))
    )
    (net (code "233") (name "Net-(SV4-Pad19)") (class "Default")
      (node (ref "SV4") (pin "19") (pinfunction "19_19") (pintype "passive"))
      (node (ref "SV4") (pin "20") (pinfunction "20_20") (pintype "passive"))
    )
    (net (code "234") (name "Net-(SV4-Pad21)") (class "Default")
      (node (ref "SV4") (pin "21") (pinfunction "21_21") (pintype "passive"))
      (node (ref "SV4") (pin "22") (pinfunction "22_22") (pintype "passive"))
    )
    (net (code "235") (name "Net-(SV4-Pad23)") (class "Default")
      (node (ref "SV4") (pin "23") (pinfunction "23_23") (pintype "passive"))
      (node (ref "SV4") (pin "24") (pinfunction "24_24") (pintype "passive"))
    )
    (net (code "236") (name "Net-(SV4-Pad27)") (class "Default")
      (node (ref "SV4") (pin "27") (pinfunction "27_27") (pintype "passive"))
      (node (ref "SV4") (pin "28") (pinfunction "28_28") (pintype "passive"))
    )
    (net (code "237") (name "Net-(SV4-Pad29)") (class "Default")
      (node (ref "SV4") (pin "29") (pinfunction "29_29") (pintype "passive"))
      (node (ref "SV4") (pin "30") (pinfunction "30_30") (pintype "passive"))
    )
    (net (code "238") (name "Net-(SV4-Pad31)") (class "Default")
      (node (ref "SV4") (pin "31") (pinfunction "31_31") (pintype "passive"))
      (node (ref "SV4") (pin "32") (pinfunction "32_32") (pintype "passive"))
    )
    (net (code "239") (name "Net-(SV4-Pad33)") (class "Default")
      (node (ref "SV4") (pin "33") (pinfunction "33_33") (pintype "passive"))
      (node (ref "SV4") (pin "34") (pinfunction "34_34") (pintype "passive"))
    )
    (net (code "240") (name "Net-(SV4-Pad35)") (class "Default")
      (node (ref "SV4") (pin "35") (pinfunction "35_35") (pintype "passive"))
      (node (ref "SV4") (pin "36") (pinfunction "36_36") (pintype "passive"))
    )
    (net (code "241") (name "Net-(SV4-Pad37)") (class "Default")
      (node (ref "SV4") (pin "37") (pinfunction "37_37") (pintype "passive"))
      (node (ref "SV4") (pin "38") (pinfunction "38_38") (pintype "passive"))
    )
    (net (code "242") (name "Net-(SV5-Pad1)") (class "Default")
      (node (ref "SV5") (pin "1") (pinfunction "1_1") (pintype "passive"))
      (node (ref "SV5") (pin "2") (pinfunction "2_2") (pintype "passive"))
    )
    (net (code "243") (name "Net-(SV5-Pad3)") (class "Default")
      (node (ref "SV5") (pin "3") (pinfunction "3_3") (pintype "passive"))
      (node (ref "SV5") (pin "4") (pinfunction "4_4") (pintype "passive"))
    )
    (net (code "244") (name "Net-(SV5-Pad5)") (class "Default")
      (node (ref "SV5") (pin "5") (pinfunction "5_5") (pintype "passive"))
      (node (ref "SV5") (pin "6") (pinfunction "6_6") (pintype "passive"))
    )
    (net (code "245") (name "Net-(SV6-Pad5)") (class "Default")
      (node (ref "SV6") (pin "5") (pinfunction "5_5") (pintype "passive"))
      (node (ref "SV6") (pin "6") (pinfunction "6_6") (pintype "passive"))
    )
    (net (code "246") (name "Net-(T1-B)") (class "Default")
      (node (ref "R1") (pin "2") (pinfunction "2_2") (pintype "passive"))
      (node (ref "T1") (pin "1") (pinfunction "B_1") (pintype "passive"))
    )
    (net (code "247") (name "Net-(T1-C)") (class "Default")
      (node (ref "J4") (pin "P$1") (pinfunction "P$1_P$1") (pintype "bidirectional"))
      (node (ref "J4") (pin "P$2") (pinfunction "P$2_P$2") (pintype "bidirectional"))
      (node (ref "J4") (pin "P$3") (pinfunction "P$3_P$3") (pintype "bidirectional"))
      (node (ref "T1") (pin "2") (pinfunction "C_2") (pintype "passive"))
    )
    (net (code "248") (name "Net-(T2-B)") (class "Default")
      (node (ref "R2") (pin "2") (pinfunction "2_2") (pintype "passive"))
      (node (ref "T2") (pin "1") (pinfunction "B_1") (pintype "passive"))
    )
    (net (code "249") (name "Net-(T2-C)") (class "Default")
      (node (ref "J23") (pin "P$1") (pinfunction "P$1_P$1") (pintype "bidirectional"))
      (node (ref "J23") (pin "P$2") (pinfunction "P$2_P$2") (pintype "bidirectional"))
      (node (ref "J23") (pin "P$3") (pinfunction "P$3_P$3") (pintype "bidirectional"))
      (node (ref "T2") (pin "2") (pinfunction "C_2") (pintype "passive"))
    )
    (net (code "250") (name "Net-(U$1-P3_SCLK)") (class "Default")
      (node (ref "J125") (pin "P$1") (pinfunction "P$1_P$1") (pintype "bidirectional"))
      (node (ref "J125") (pin "P$2") (pinfunction "P$2_P$2") (pintype "bidirectional"))
      (node (ref "J125") (pin "P$3") (pinfunction "P$3_P$3") (pintype "bidirectional"))
      (node (ref "U$1") (pin "3") (pinfunction "P3_SCLK_3") (pintype "bidirectional"))
    )
    (net (code "251") (name "Net-(U$1-P4_SDA{slash}SPIMOSI)") (class "Default")
      (node (ref "J126") (pin "P$1") (pinfunction "P$1_P$1") (pintype "bidirectional"))
      (node (ref "J126") (pin "P$2") (pinfunction "P$2_P$2") (pintype "bidirectional"))
      (node (ref "J126") (pin "P$3") (pinfunction "P$3_P$3") (pintype "bidirectional"))
      (node (ref "U$1") (pin "4") (pinfunction "P4_SDA/SPIMOSI_4") (pintype "bidirectional"))
    )
    (net (code "252") (name "Net-(U$1-P5_EDA{slash}AUX-DA)") (class "Default")
      (node (ref "J127") (pin "P$1") (pinfunction "P$1_P$1") (pintype "bidirectional"))
      (node (ref "J127") (pin "P$2") (pinfunction "P$2_P$2") (pintype "bidirectional"))
      (node (ref "J127") (pin "P$3") (pinfunction "P$3_P$3") (pintype "bidirectional"))
      (node (ref "U$1") (pin "5") (pinfunction "P5_EDA/AUX-DA_5") (pintype "bidirectional"))
    )
    (net (code "253") (name "Net-(U$1-P6_ECL{slash}AUX-CL)") (class "Default")
      (node (ref "J128") (pin "P$1") (pinfunction "P$1_P$1") (pintype "bidirectional"))
      (node (ref "J128") (pin "P$2") (pinfunction "P$2_P$2") (pintype "bidirectional"))
      (node (ref "J128") (pin "P$3") (pinfunction "P$3_P$3") (pintype "bidirectional"))
      (node (ref "U$1") (pin "6") (pinfunction "P6_ECL/AUX-CL_6") (pintype "bidirectional"))
    )
    (net (code "254") (name "Net-(U$1-P7_ADO{slash}SPIMISO)") (class "Default")
      (node (ref "J129") (pin "P$1") (pinfunction "P$1_P$1") (pintype "bidirectional"))
      (node (ref "J129") (pin "P$2") (pinfunction "P$2_P$2") (pintype "bidirectional"))
      (node (ref "J129") (pin "P$3") (pinfunction "P$3_P$3") (pintype "bidirectional"))
      (node (ref "U$1") (pin "7") (pinfunction "P7_ADO/SPIMISO_7") (pintype "bidirectional"))
    )
    (net (code "255") (name "Net-(U$1-P8_INT)") (class "Default")
      (node (ref "J130") (pin "P$1") (pinfunction "P$1_P$1") (pintype "bidirectional"))
      (node (ref "J130") (pin "P$2") (pinfunction "P$2_P$2") (pintype "bidirectional"))
      (node (ref "J130") (pin "P$3") (pinfunction "P$3_P$3") (pintype "bidirectional"))
      (node (ref "U$1") (pin "8") (pinfunction "P8_INT_8") (pintype "bidirectional"))
    )
    (net (code "256") (name "Net-(U$1-P9_NCS)") (class "Default")
      (node (ref "J131") (pin "P$1") (pinfunction "P$1_P$1") (pintype "bidirectional"))
      (node (ref "J131") (pin "P$2") (pinfunction "P$2_P$2") (pintype "bidirectional"))
      (node (ref "J131") (pin "P$3") (pinfunction "P$3_P$3") (pintype "bidirectional"))
      (node (ref "U$1") (pin "9") (pinfunction "P9_NCS_9") (pintype "bidirectional"))
    )
    (net (code "257") (name "Net-(U$1-P10_FSYNC)") (class "Default")
      (node (ref "J132") (pin "P$1") (pinfunction "P$1_P$1") (pintype "bidirectional"))
      (node (ref "J132") (pin "P$2") (pinfunction "P$2_P$2") (pintype "bidirectional"))
      (node (ref "J132") (pin "P$3") (pinfunction "P$3_P$3") (pintype "bidirectional"))
      (node (ref "U$1") (pin "10") (pinfunction "P10_FSYNC_10") (pintype "bidirectional"))
    )
    (net (code "258") (name "Net-(U1-MODE)") (class "Default")
      (node (ref "JP2") (pin "1") (pinfunction "1_1") (pintype "passive"))
      (node (ref "R4") (pin "1") (pinfunction "1_1") (pintype "passive"))
      (node (ref "U1") (pin "14") (pinfunction "MODE_14") (pintype "bidirectional"))
    )
    (net (code "259") (name "Net-(U1-PHASE)") (class "Default")
      (node (ref "J196") (pin "P$1") (pinfunction "P$1_P$1") (pintype "bidirectional"))
      (node (ref "J196") (pin "P$2") (pinfunction "P$2_P$2") (pintype "bidirectional"))
      (node (ref "J25") (pin "P$1") (pinfunction "P$1_P$1") (pintype "bidirectional"))
      (node (ref "J25") (pin "P$2") (pinfunction "P$2_P$2") (pintype "bidirectional"))
      (node (ref "U1") (pin "7") (pinfunction "PHASE_7") (pintype "bidirectional"))
    )
    (net (code "260") (name "Net-(U1-RC)") (class "Default")
      (node (ref "C14") (pin "1") (pinfunction "1_1") (pintype "passive"))
      (node (ref "R3") (pin "2") (pinfunction "2_2") (pintype "passive"))
      (node (ref "U1") (pin "3") (pinfunction "RC_3") (pintype "bidirectional"))
    )
    (net (code "261") (name "Net-(U1-~{BRAKE})") (class "Default")
      (node (ref "R8") (pin "1") (pinfunction "1_1") (pintype "passive"))
      (node (ref "U1") (pin "1") (pinfunction "~{BRAKE}_1") (pintype "bidirectional"))
    )
    (net (code "262") (name "Net-(U2-CPH)") (class "Default")
      (node (ref "C19") (pin "2") (pinfunction "2_2") (pintype "passive"))
      (node (ref "U2") (pin "P$13") (pinfunction "CPH_P$13") (pintype "bidirectional"))
    )
    (net (code "263") (name "Net-(U2-CPL)") (class "Default")
      (node (ref "C19") (pin "1") (pinfunction "1_1") (pintype "passive"))
      (node (ref "U2") (pin "P$14") (pinfunction "CPL_P$14") (pintype "bidirectional"))
    )
    (net (code "264") (name "Net-(U2-IPROPI)") (class "Default")
      (node (ref "R41") (pin "1") (pinfunction "1_1") (pintype "passive"))
      (node (ref "U2") (pin "P$6") (pinfunction "IPROPI_P$6") (pintype "bidirectional"))
    )
    (net (code "265") (name "Net-(U2-NFAULT)") (class "Default")
      (node (ref "J78") (pin "P$1") (pinfunction "P$1_P$1") (pintype "bidirectional"))
      (node (ref "J78") (pin "P$2") (pinfunction "P$2_P$2") (pintype "bidirectional"))
      (node (ref "R42") (pin "2") (pinfunction "2_2") (pintype "passive"))
      (node (ref "U2") (pin "P$4") (pinfunction "NFAULT_P$4") (pintype "bidirectional"))
    )
    (net (code "266") (name "Net-(U2-VCP)") (class "Default")
      (node (ref "C17") (pin "1") (pinfunction "1_1") (pintype "passive"))
      (node (ref "U2") (pin "P$12") (pinfunction "VCP_P$12") (pintype "bidirectional"))
    )
    (net (code "267") (name "Net-(U2-VREF)") (class "Default")
      (node (ref "TRIMPOT1") (pin "3") (pinfunction "3_3") (pintype "passive"))
      (node (ref "TRIMPOT1") (pin "4") (pinfunction "4_4") (pintype "passive"))
      (node (ref "U2") (pin "P$5") (pinfunction "VREF_P$5") (pintype "bidirectional"))
    )
    (net (code "268") (name "Net-(U3-P1_OSCI)") (class "Default")
      (node (ref "Q1") (pin "2") (pinfunction "2_2") (pintype "passive"))
      (node (ref "U3") (pin "1") (pinfunction "P1_OSCI_1") (pintype "bidirectional"))
    )
    (net (code "269") (name "Net-(U3-P2_OSC0)") (class "Default")
      (node (ref "Q1") (pin "1") (pinfunction "1_1") (pintype "passive"))
      (node (ref "U3") (pin "2") (pinfunction "P2_OSC0_2") (pintype "bidirectional"))
    )
    (net (code "270") (name "Net-(U3-P3_VBACK)") (class "Default")
      (node (ref "G1") (pin "+") (pinfunction "+_+") (pintype "passive"))
      (node (ref "U3") (pin "3") (pinfunction "P3_VBACK_3") (pintype "bidirectional"))
    )
    (net (code "271") (name "Net-(U3-P7_IRQ)") (class "Default")
      (node (ref "J1") (pin "P$1") (pinfunction "P$1_P$1") (pintype "bidirectional"))
      (node (ref "J1") (pin "P$2") (pinfunction "P$2_P$2") (pintype "bidirectional"))
      (node (ref "J1") (pin "P$3") (pinfunction "P$3_P$3") (pintype "bidirectional"))
      (node (ref "U3") (pin "7") (pinfunction "P7_IRQ_7") (pintype "bidirectional"))
    )
    (net (code "272") (name "Net-(U4-CPH)") (class "Default")
      (node (ref "C24") (pin "2") (pinfunction "2_2") (pintype "passive"))
      (node (ref "U4") (pin "P$13") (pinfunction "CPH_P$13") (pintype "bidirectional"))
    )
    (net (code "273") (name "Net-(U4-CPL)") (class "Default")
      (node (ref "C24") (pin "1") (pinfunction "1_1") (pintype "passive"))
      (node (ref "U4") (pin "P$14") (pinfunction "CPL_P$14") (pintype "bidirectional"))
    )
    (net (code "274") (name "Net-(U4-IPROPI)") (class "Default")
      (node (ref "R43") (pin "1") (pinfunction "1_1") (pintype "passive"))
      (node (ref "U4") (pin "P$6") (pinfunction "IPROPI_P$6") (pintype "bidirectional"))
    )
    (net (code "275") (name "Net-(U4-NFAULT)") (class "Default")
      (node (ref "J81") (pin "P$1") (pinfunction "P$1_P$1") (pintype "bidirectional"))
      (node (ref "J81") (pin "P$2") (pinfunction "P$2_P$2") (pintype "bidirectional"))
      (node (ref "R44") (pin "2") (pinfunction "2_2") (pintype "passive"))
      (node (ref "U4") (pin "P$4") (pinfunction "NFAULT_P$4") (pintype "bidirectional"))
    )
    (net (code "276") (name "Net-(U4-VCP)") (class "Default")
      (node (ref "C23") (pin "1") (pinfunction "1_1") (pintype "passive"))
      (node (ref "U4") (pin "P$12") (pinfunction "VCP_P$12") (pintype "bidirectional"))
    )
    (net (code "277") (name "Net-(U4-VREF)") (class "Default")
      (node (ref "TRIMPOT2") (pin "3") (pinfunction "3_3") (pintype "passive"))
      (node (ref "TRIMPOT2") (pin "4") (pinfunction "4_4") (pintype "passive"))
      (node (ref "U4") (pin "P$5") (pinfunction "VREF_P$5") (pintype "bidirectional"))
    )
    (net (code "278") (name "Net-(U5-MODE)") (class "Default")
      (node (ref "JP3") (pin "1") (pinfunction "1_1") (pintype "passive"))
      (node (ref "R5") (pin "1") (pinfunction "1_1") (pintype "passive"))
      (node (ref "U5") (pin "14") (pinfunction "MODE_14") (pintype "bidirectional"))
    )
    (net (code "279") (name "Net-(U5-PHASE)") (class "Default")
      (node (ref "J197") (pin "P$1") (pinfunction "P$1_P$1") (pintype "bidirectional"))
      (node (ref "J197") (pin "P$2") (pinfunction "P$2_P$2") (pintype "bidirectional"))
      (node (ref "J34") (pin "P$1") (pinfunction "P$1_P$1") (pintype "bidirectional"))
      (node (ref "J34") (pin "P$2") (pinfunction "P$2_P$2") (pintype "bidirectional"))
      (node (ref "U5") (pin "7") (pinfunction "PHASE_7") (pintype "bidirectional"))
    )
    (net (code "280") (name "Net-(U5-RC)") (class "Default")
      (node (ref "C2") (pin "1") (pinfunction "1_1") (pintype "passive"))
      (node (ref "R7") (pin "2") (pinfunction "2_2") (pintype "passive"))
      (node (ref "U5") (pin "3") (pinfunction "RC_3") (pintype "bidirectional"))
    )
    (net (code "281") (name "Net-(U5-~{BRAKE})") (class "Default")
      (node (ref "R6") (pin "1") (pinfunction "1_1") (pintype "passive"))
      (node (ref "U5") (pin "1") (pinfunction "~{BRAKE}_1") (pintype "bidirectional"))
    )
    (net (code "282") (name "Net-(U6-IN2)") (class "Default")
      (node (ref "SV10") (pin "2") (pinfunction "2_2") (pintype "passive"))
      (node (ref "U6") (pin "P$2") (pinfunction "IN2_P$2") (pintype "bidirectional"))
    )
    (net (code "283") (name "Net-(U6-IN3)") (class "Default")
      (node (ref "SV10") (pin "3") (pinfunction "3_3") (pintype "passive"))
      (node (ref "U6") (pin "P$3") (pinfunction "IN3_P$3") (pintype "bidirectional"))
    )
    (net (code "284") (name "Net-(U6-OUT1)") (class "Default")
      (node (ref "SV9") (pin "1") (pinfunction "1_1") (pintype "passive"))
      (node (ref "U6") (pin "P$7") (pinfunction "OUT1_P$7") (pintype "bidirectional"))
    )
    (net (code "285") (name "Net-(U6-OUT3)") (class "Default")
      (node (ref "SV9") (pin "3") (pinfunction "3_3") (pintype "passive"))
      (node (ref "U6") (pin "P$5") (pinfunction "OUT3_P$5") (pintype "bidirectional"))
    )
    (net (code "286") (name "Net-(U7-~{HOLD})") (class "Default")
      (node (ref "R25") (pin "1") (pinfunction "1_1") (pintype "passive"))
      (node (ref "U7") (pin "7") (pinfunction "~{HOLD}_7") (pintype "bidirectional"))
    )
    (net (code "287") (name "Net-(U8-VDD)") (class "Default")
      (node (ref "C11") (pin "1") (pinfunction "1_1") (pintype "passive"))
      (node (ref "U8") (pin "1") (pinfunction "VDD_1") (pintype "bidirectional"))
    )
    (net (code "288") (name "Net-(U8-VDD2)") (class "Default")
      (node (ref "C8") (pin "1") (pinfunction "1_1") (pintype "passive"))
      (node (ref "U8") (pin "11") (pinfunction "VDD2_11") (pintype "bidirectional"))
    )
    (net (code "289") (name "Net-(U8-{slash}XRS)") (class "Default")
      (node (ref "P1") (pin "1") (pinfunction "1_1") (pintype "bidirectional"))
      (node (ref "R38") (pin "1") (pinfunction "1_1") (pintype "passive"))
      (node (ref "U8") (pin "17") (pinfunction "/XRS_17") (pintype "bidirectional"))
    )
    (net (code "290") (name "POWER") (class "Default")
      (node (ref "B2") (pin "P$1") (pinfunction "BAT+_P$1") (pintype "bidirectional"))
      (node (ref "C1") (pin "+") (pinfunction "+_+") (pintype "passive"))
      (node (ref "C12") (pin "+") (pinfunction "+_+") (pintype "passive"))
      (node (ref "C13") (pin "+") (pinfunction "+_+") (pintype "passive"))
      (node (ref "C15") (pin "+") (pinfunction "+_+") (pintype "passive"))
      (node (ref "C16") (pin "1") (pinfunction "1_1") (pintype "passive"))
      (node (ref "C17") (pin "2") (pinfunction "2_2") (pintype "passive"))
      (node (ref "C20") (pin "+") (pinfunction "+_+") (pintype "passive"))
      (node (ref "C22") (pin "1") (pinfunction "1_1") (pintype "passive"))
      (node (ref "C23") (pin "2") (pinfunction "2_2") (pintype "passive"))
      (node (ref "C25") (pin "+") (pinfunction "+_+") (pintype "passive"))
      (node (ref "C27") (pin "+") (pinfunction "+_+") (pintype "passive"))
      (node (ref "C28") (pin "+") (pinfunction "+_+") (pintype "passive"))
      (node (ref "DCDC3.3V") (pin "1") (pinfunction "1_1") (pintype "passive"))
      (node (ref "DCDC5V") (pin "1") (pinfunction "1_1") (pintype "passive"))
      (node (ref "J5") (pin "1") (pinfunction "1_1") (pintype "passive"))
      (node (ref "POWER") (pin "2") (pinfunction "2_2") (pintype "passive"))
      (node (ref "S141") (pin "P$1") (pinfunction "P$1_P$1") (pintype "bidirectional"))
      (node (ref "S141") (pin "P$2") (pinfunction "P$2_P$2") (pintype "bidirectional"))
      (node (ref "S141") (pin "P$3") (pinfunction "P$3_P$3") (pintype "bidirectional"))
      (node (ref "S141") (pin "P$4") (pinfunction "P$4_P$4") (pintype "bidirectional"))
      (node (ref "S141") (pin "P$5") (pinfunction "P$5_P$5") (pintype "bidirectional"))
      (node (ref "U1") (pin "16") (pinfunction "VBB_16") (pintype "bidirectional"))
      (node (ref "U1") (pin "9") (pinfunction "VBB_9") (pintype "bidirectional"))
      (node (ref "U2") (pin "P$11") (pinfunction "VM_P$11") (pintype "bidirectional"))
      (node (ref "U4") (pin "P$11") (pinfunction "VM_P$11") (pintype "bidirectional"))
      (node (ref "U5") (pin "16") (pinfunction "VBB_16") (pintype "bidirectional"))
      (node (ref "U5") (pin "9") (pinfunction "VBB_9") (pintype "bidirectional"))
    )
    (net (code "291") (name "RESET") (class "Default")
      (node (ref "J98") (pin "P$1") (pinfunction "P$1_P$1") (pintype "bidirectional"))
      (node (ref "J98") (pin "P$2") (pinfunction "P$2_P$2") (pintype "bidirectional"))
      (node (ref "J98") (pin "P$3") (pinfunction "P$3_P$3") (pintype "bidirectional"))
      (node (ref "L1") (pin "P$16") (pinfunction "RST_P$16") (pintype "bidirectional"))
    )
    (net (code "292") (name "RESET_2") (class "Default")
      (node (ref "J157") (pin "P$1") (pinfunction "P$1_P$1") (pintype "bidirectional"))
      (node (ref "J157") (pin "P$2") (pinfunction "P$2_P$2") (pintype "bidirectional"))
      (node (ref "J157") (pin "P$3") (pinfunction "P$3_P$3") (pintype "bidirectional"))
      (node (ref "L1") (pin "P$56") (pinfunction "RST_2_P$56") (pintype "bidirectional"))
    )
    (net (code "293") (name "SCL") (class "Default")
      (node (ref "J2") (pin "P$1") (pinfunction "P$1_P$1") (pintype "bidirectional"))
      (node (ref "J2") (pin "P$2") (pinfunction "P$2_P$2") (pintype "bidirectional"))
      (node (ref "J2") (pin "P$3") (pinfunction "P$3_P$3") (pintype "bidirectional"))
      (node (ref "U3") (pin "6") (pinfunction "P6_SCL_6") (pintype "bidirectional"))
    )
    (net (code "294") (name "SDA") (class "Default")
      (node (ref "J3") (pin "P$1") (pinfunction "P$1_P$1") (pintype "bidirectional"))
      (node (ref "J3") (pin "P$2") (pinfunction "P$2_P$2") (pintype "bidirectional"))
      (node (ref "J3") (pin "P$3") (pinfunction "P$3_P$3") (pintype "bidirectional"))
      (node (ref "U3") (pin "5") (pinfunction "P5_SDA_5") (pintype "bidirectional"))
    )
    (net (code "295") (name "TCK") (class "Default")
      (node (ref "SV14") (pin "11") (pinfunction "11_11") (pintype "passive"))
      (node (ref "SV14") (pin "9") (pinfunction "9_9") (pintype "passive"))
      (node (ref "U8") (pin "31") (pinfunction "GPIO38/XCLKIN(TCK)_31") (pintype "bidirectional"))
    )
    (net (code "296") (name "TDI") (class "Default")
      (node (ref "SV14") (pin "3") (pinfunction "3_3") (pintype "passive"))
      (node (ref "U8") (pin "28") (pinfunction "GPIO35(TDI)_28") (pintype "bidirectional"))
    )
    (net (code "297") (name "TDO") (class "Default")
      (node (ref "R33") (pin "2") (pinfunction "2_2") (pintype "passive"))
      (node (ref "SV14") (pin "7") (pinfunction "7_7") (pintype "passive"))
      (node (ref "U8") (pin "30") (pinfunction "GPIO37(TDO)_30") (pintype "bidirectional"))
    )
    (net (code "298") (name "TMS") (class "Default")
      (node (ref "SV14") (pin "1") (pinfunction "1_1") (pintype "passive"))
      (node (ref "U8") (pin "29") (pinfunction "GPIO36(TMS)_29") (pintype "bidirectional"))
    )
    (net (code "299") (name "TRSTN") (class "Default")
      (node (ref "R32") (pin "1") (pinfunction "1_1") (pintype "passive"))
      (node (ref "SV14") (pin "2") (pinfunction "2_2") (pintype "passive"))
      (node (ref "U8") (pin "16") (pinfunction "/TRST_16") (pintype "bidirectional"))
    )
    (net (code "300") (name "VCC") (class "Default")
      (node (ref "C10") (pin "1") (pinfunction "1_1") (pintype "passive"))
      (node (ref "C18") (pin "1") (pinfunction "1_1") (pintype "passive"))
      (node (ref "C3") (pin "1") (pinfunction "1_1") (pintype "passive"))
      (node (ref "C4") (pin "1") (pinfunction "1_1") (pintype "passive"))
      (node (ref "C5") (pin "1") (pinfunction "1_1") (pintype "passive"))
      (node (ref "C6") (pin "1") (pinfunction "1_1") (pintype "passive"))
      (node (ref "C7") (pin "1") (pinfunction "1_1") (pintype "passive"))
      (node (ref "C9") (pin "1") (pinfunction "1_1") (pintype "passive"))
      (node (ref "DCDC3.3V") (pin "3") (pinfunction "3_3") (pintype "passive"))
      (node (ref "ETH1") (pin "P$10") (pinfunction "3V3_1_P$10") (pintype "bidirectional"))
      (node (ref "ETH1") (pin "P$11") (pinfunction "3V3_2_P$11") (pintype "bidirectional"))
      (node (ref "IC1") (pin "14") (pinfunction "VCC_14") (pintype "power_in"))
      (node (ref "IC2") (pin "14") (pinfunction "VCC_14") (pintype "power_in"))
      (node (ref "IC3") (pin "14") (pinfunction "VCC_14") (pintype "power_in"))
      (node (ref "J10") (pin "P$1") (pinfunction "P$1_P$1") (pintype "bidirectional"))
      (node (ref "J10") (pin "P$2") (pinfunction "P$2_P$2") (pintype "bidirectional"))
      (node (ref "J10") (pin "P$3") (pinfunction "P$3_P$3") (pintype "bidirectional"))
      (node (ref "J123") (pin "P$1") (pinfunction "P$1_P$1") (pintype "bidirectional"))
      (node (ref "J123") (pin "P$2") (pinfunction "P$2_P$2") (pintype "bidirectional"))
      (node (ref "J123") (pin "P$3") (pinfunction "P$3_P$3") (pintype "bidirectional"))
      (node (ref "J177") (pin "P$1") (pinfunction "P$1_P$1") (pintype "bidirectional"))
      (node (ref "J177") (pin "P$2") (pinfunction "P$2_P$2") (pintype "bidirectional"))
      (node (ref "J177") (pin "P$3") (pinfunction "P$3_P$3") (pintype "bidirectional"))
      (node (ref "L1") (pin "P$1") (pinfunction "3.3V_1_P$1") (pintype "bidirectional"))
      (node (ref "L1") (pin "P$41") (pinfunction "3.3V_2_P$41") (pintype "bidirectional"))
      (node (ref "R10") (pin "1") (pinfunction "1_1") (pintype "passive"))
      (node (ref "R11") (pin "2") (pinfunction "2_2") (pintype "passive"))
      (node (ref "R12") (pin "2") (pinfunction "2_2") (pintype "passive"))
      (node (ref "R13") (pin "2") (pinfunction "2_2") (pintype "passive"))
      (node (ref "R14") (pin "2") (pinfunction "2_2") (pintype "passive"))
      (node (ref "R15") (pin "2") (pinfunction "2_2") (pintype "passive"))
      (node (ref "R16") (pin "2") (pinfunction "2_2") (pintype "passive"))
      (node (ref "R17") (pin "2") (pinfunction "2_2") (pintype "passive"))
      (node (ref "R18") (pin "2") (pinfunction "2_2") (pintype "passive"))
      (node (ref "R19") (pin "2") (pinfunction "2_2") (pintype "passive"))
      (node (ref "R20") (pin "2") (pinfunction "2_2") (pintype "passive"))
      (node (ref "R21") (pin "2") (pinfunction "2_2") (pintype "passive"))
      (node (ref "R22") (pin "2") (pinfunction "2_2") (pintype "passive"))
      (node (ref "R23") (pin "2") (pinfunction "2_2") (pintype "passive"))
      (node (ref "R24") (pin "2") (pinfunction "2_2") (pintype "passive"))
      (node (ref "R25") (pin "2") (pinfunction "2_2") (pintype "passive"))
      (node (ref "R27") (pin "2") (pinfunction "2_2") (pintype "passive"))
      (node (ref "R28") (pin "2") (pinfunction "2_2") (pintype "passive"))
      (node (ref "R29") (pin "2") (pinfunction "2_2") (pintype "passive"))
      (node (ref "R30") (pin "2") (pinfunction "2_2") (pintype "passive"))
      (node (ref "R31") (pin "2") (pinfunction "2_2") (pintype "passive"))
      (node (ref "R33") (pin "1") (pinfunction "1_1") (pintype "passive"))
      (node (ref "R34") (pin "1") (pinfunction "1_1") (pintype "passive"))
      (node (ref "R35") (pin "1") (pinfunction "1_1") (pintype "passive"))
      (node (ref "R36") (pin "2") (pinfunction "2_2") (pintype "passive"))
      (node (ref "R37") (pin "2") (pinfunction "2_2") (pintype "passive"))
      (node (ref "R38") (pin "2") (pinfunction "2_2") (pintype "passive"))
      (node (ref "R4") (pin "2") (pinfunction "2_2") (pintype "passive"))
      (node (ref "R42") (pin "1") (pinfunction "1_1") (pintype "passive"))
      (node (ref "R44") (pin "1") (pinfunction "1_1") (pintype "passive"))
      (node (ref "R5") (pin "2") (pinfunction "2_2") (pintype "passive"))
      (node (ref "R6") (pin "2") (pinfunction "2_2") (pintype "passive"))
      (node (ref "R8") (pin "2") (pinfunction "2_2") (pintype "passive"))
      (node (ref "R9") (pin "1") (pinfunction "1_1") (pintype "passive"))
      (node (ref "S53") (pin "P$1") (pinfunction "P$1_P$1") (pintype "bidirectional"))
      (node (ref "S53") (pin "P$10") (pinfunction "P$10_P$10") (pintype "bidirectional"))
      (node (ref "S53") (pin "P$2") (pinfunction "P$2_P$2") (pintype "bidirectional"))
      (node (ref "S53") (pin "P$3") (pinfunction "P$3_P$3") (pintype "bidirectional"))
      (node (ref "S53") (pin "P$4") (pinfunction "P$4_P$4") (pintype "bidirectional"))
      (node (ref "S53") (pin "P$5") (pinfunction "P$5_P$5") (pintype "bidirectional"))
      (node (ref "S53") (pin "P$6") (pinfunction "P$6_P$6") (pintype "bidirectional"))
      (node (ref "S53") (pin "P$7") (pinfunction "P$7_P$7") (pintype "bidirectional"))
      (node (ref "S53") (pin "P$8") (pinfunction "P$8_P$8") (pintype "bidirectional"))
      (node (ref "S53") (pin "P$9") (pinfunction "P$9_P$9") (pintype "bidirectional"))
      (node (ref "S58") (pin "P$1") (pinfunction "P$1_P$1") (pintype "bidirectional"))
      (node (ref "S58") (pin "P$10") (pinfunction "P$10_P$10") (pintype "bidirectional"))
      (node (ref "S58") (pin "P$2") (pinfunction "P$2_P$2") (pintype "bidirectional"))
      (node (ref "S58") (pin "P$3") (pinfunction "P$3_P$3") (pintype "bidirectional"))
      (node (ref "S58") (pin "P$4") (pinfunction "P$4_P$4") (pintype "bidirectional"))
      (node (ref "S58") (pin "P$5") (pinfunction "P$5_P$5") (pintype "bidirectional"))
      (node (ref "S58") (pin "P$6") (pinfunction "P$6_P$6") (pintype "bidirectional"))
      (node (ref "S58") (pin "P$7") (pinfunction "P$7_P$7") (pintype "bidirectional"))
      (node (ref "S58") (pin "P$8") (pinfunction "P$8_P$8") (pintype "bidirectional"))
      (node (ref "S58") (pin "P$9") (pinfunction "P$9_P$9") (pintype "bidirectional"))
      (node (ref "SV11") (pin "2") (pinfunction "2_2") (pintype "passive"))
      (node (ref "SV12") (pin "2") (pinfunction "2_2") (pintype "passive"))
      (node (ref "SV13") (pin "3") (pinfunction "3_3") (pintype "passive"))
      (node (ref "SV13") (pin "7") (pinfunction "7_7") (pintype "passive"))
      (node (ref "SV14") (pin "5") (pinfunction "5_5") (pintype "passive"))
      (node (ref "SV6") (pin "1") (pinfunction "1_1") (pintype "passive"))
      (node (ref "SV6") (pin "2") (pinfunction "2_2") (pintype "passive"))
      (node (ref "TRIMPOT1") (pin "1") (pinfunction "1_1") (pintype "passive"))
      (node (ref "TRIMPOT1") (pin "2") (pinfunction "2_2") (pintype "passive"))
      (node (ref "TRIMPOT2") (pin "1") (pinfunction "1_1") (pintype "passive"))
      (node (ref "TRIMPOT2") (pin "2") (pinfunction "2_2") (pintype "passive"))
      (node (ref "U$1") (pin "1") (pinfunction "P1_VCC_1") (pintype "bidirectional"))
      (node (ref "U1") (pin "2") (pinfunction "REF_2") (pintype "bidirectional"))
      (node (ref "U1") (pin "6") (pinfunction "VCC_6") (pintype "bidirectional"))
      (node (ref "U3") (pin "8") (pinfunction "P8_VCC_8") (pintype "bidirectional"))
      (node (ref "U5") (pin "2") (pinfunction "REF_2") (pintype "bidirectional"))
      (node (ref "U5") (pin "6") (pinfunction "VCC_6") (pintype "bidirectional"))
      (node (ref "U6") (pin "P$8") (pinfunction "V+_P$8") (pintype "bidirectional"))
      (node (ref "U7") (pin "8") (pinfunction "VCC_8") (pintype "bidirectional"))
      (node (ref "U8") (pin "22") (pinfunction "VDDA_22") (pintype "bidirectional"))
      (node (ref "U8") (pin "4") (pinfunction "VDDIO_4") (pintype "bidirectional"))
    )
    (net (code "301") (name "unconnected-(ETH1-NC-PadP$9)") (class "Default")
      (node (ref "ETH1") (pin "P$9") (pinfunction "NC_P$9") (pintype "bidirectional"))
    )
    (net (code "302") (name "unconnected-(G1-+-Pad+@1)") (class "Default")
      (node (ref "G1") (pin "+@1") (pinfunction "+_+@1") (pintype "passive"))
    )
    (net (code "303") (name "unconnected-(J8-PadP$1)") (class "Default")
      (node (ref "J8") (pin "P$1") (pinfunction "P$1_P$1") (pintype "bidirectional"))
    )
    (net (code "304") (name "unconnected-(J8-PadP$2)") (class "Default")
      (node (ref "J8") (pin "P$2") (pinfunction "P$2_P$2") (pintype "bidirectional"))
    )
    (net (code "305") (name "unconnected-(SV12-Pad3)") (class "Default")
      (node (ref "SV12") (pin "3") (pinfunction "3_3") (pintype "passive"))
    )
    (net (code "306") (name "unconnected-(SV12-Pad5)") (class "Default")
      (node (ref "SV12") (pin "5") (pinfunction "5_5") (pintype "passive"))
    )
    (net (code "307") (name "unconnected-(SV13-Pad4)") (class "Default")
      (node (ref "SV13") (pin "4") (pinfunction "4_4") (pintype "passive"))
    )
    (net (code "308") (name "unconnected-(SV13-Pad6)") (class "Default")
      (node (ref "SV13") (pin "6") (pinfunction "6_6") (pintype "passive"))
    )
    (net (code "309") (name "unconnected-(SV14-Pad6)") (class "Default")
      (node (ref "SV14") (pin "6") (pinfunction "6_6") (pintype "passive"))
    )
    (net (code "310") (name "unconnected-(SV14-Pad13)") (class "Default")
      (node (ref "SV14") (pin "13") (pinfunction "13_13") (pintype "passive"))
    )
    (net (code "311") (name "unconnected-(SV14-Pad14)") (class "Default")
      (node (ref "SV14") (pin "14") (pinfunction "14_14") (pintype "passive"))
    )
    (net (code "312") (name "unconnected-(U7-DNU-Pad3)") (class "Default")
      (node (ref "U7") (pin "3") (pinfunction "DNU_3") (pintype "bidirectional"))
    )
    (net (code "313") (name "unconnected-(U8-TEST-Pad38)") (class "Default")
      (node (ref "U8") (pin "38") (pinfunction "TEST_38") (pintype "bidirectional"))
    )
  )
)
